# AK4493-Combi.net
KiCad netlist of a schematic drawn in EAGLE
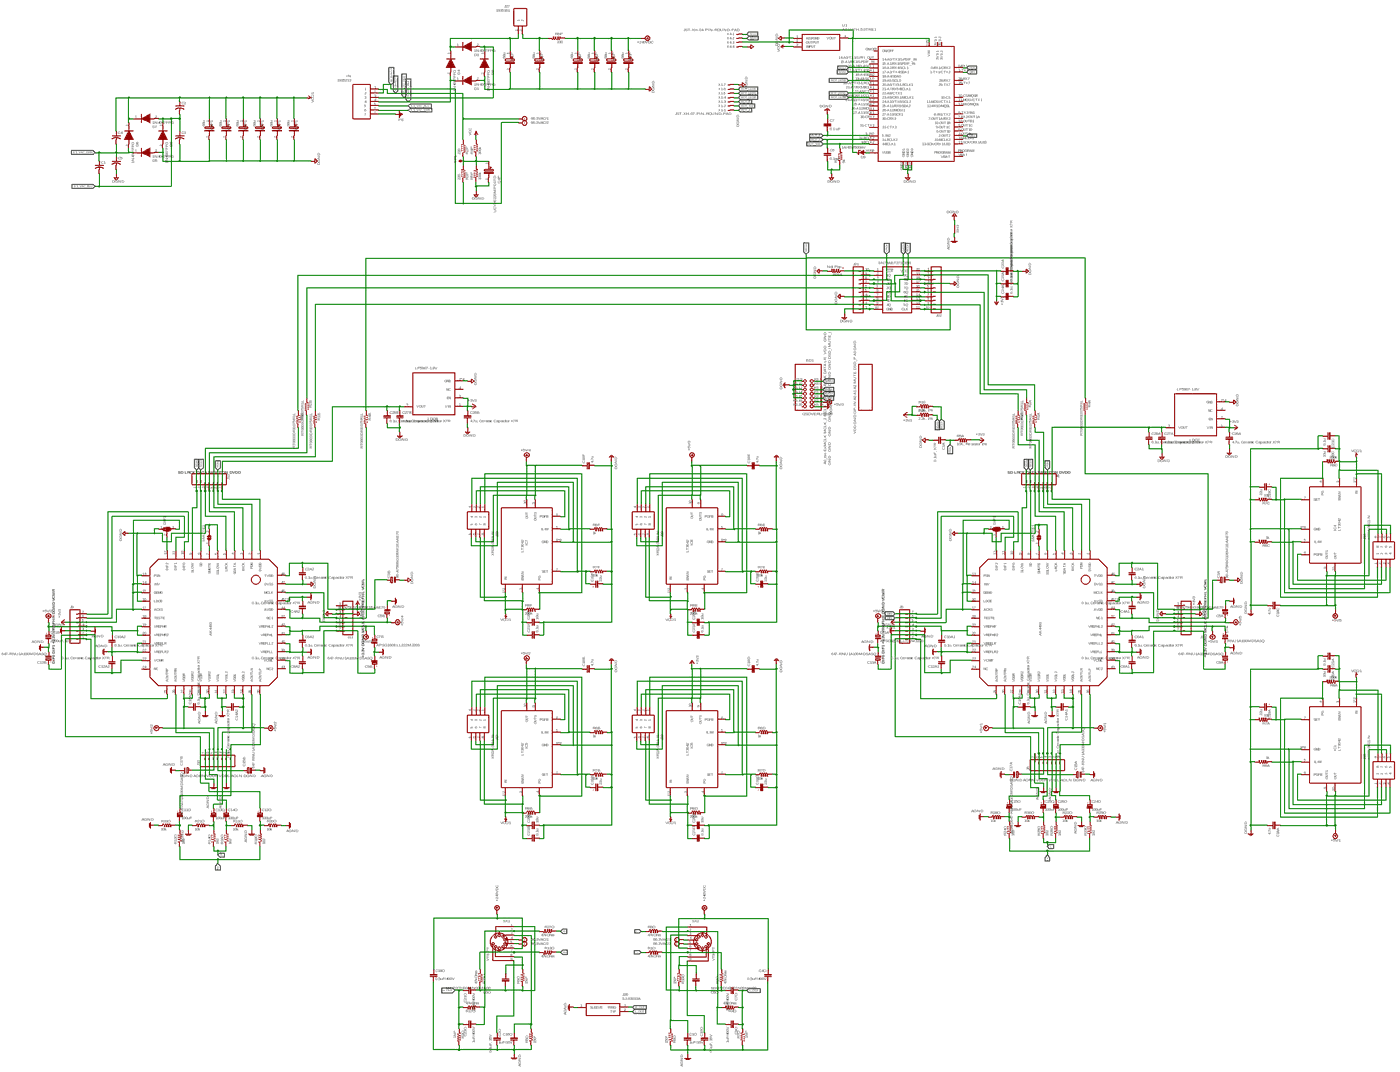
[diagram p0: schematic, sheet 1, overview]
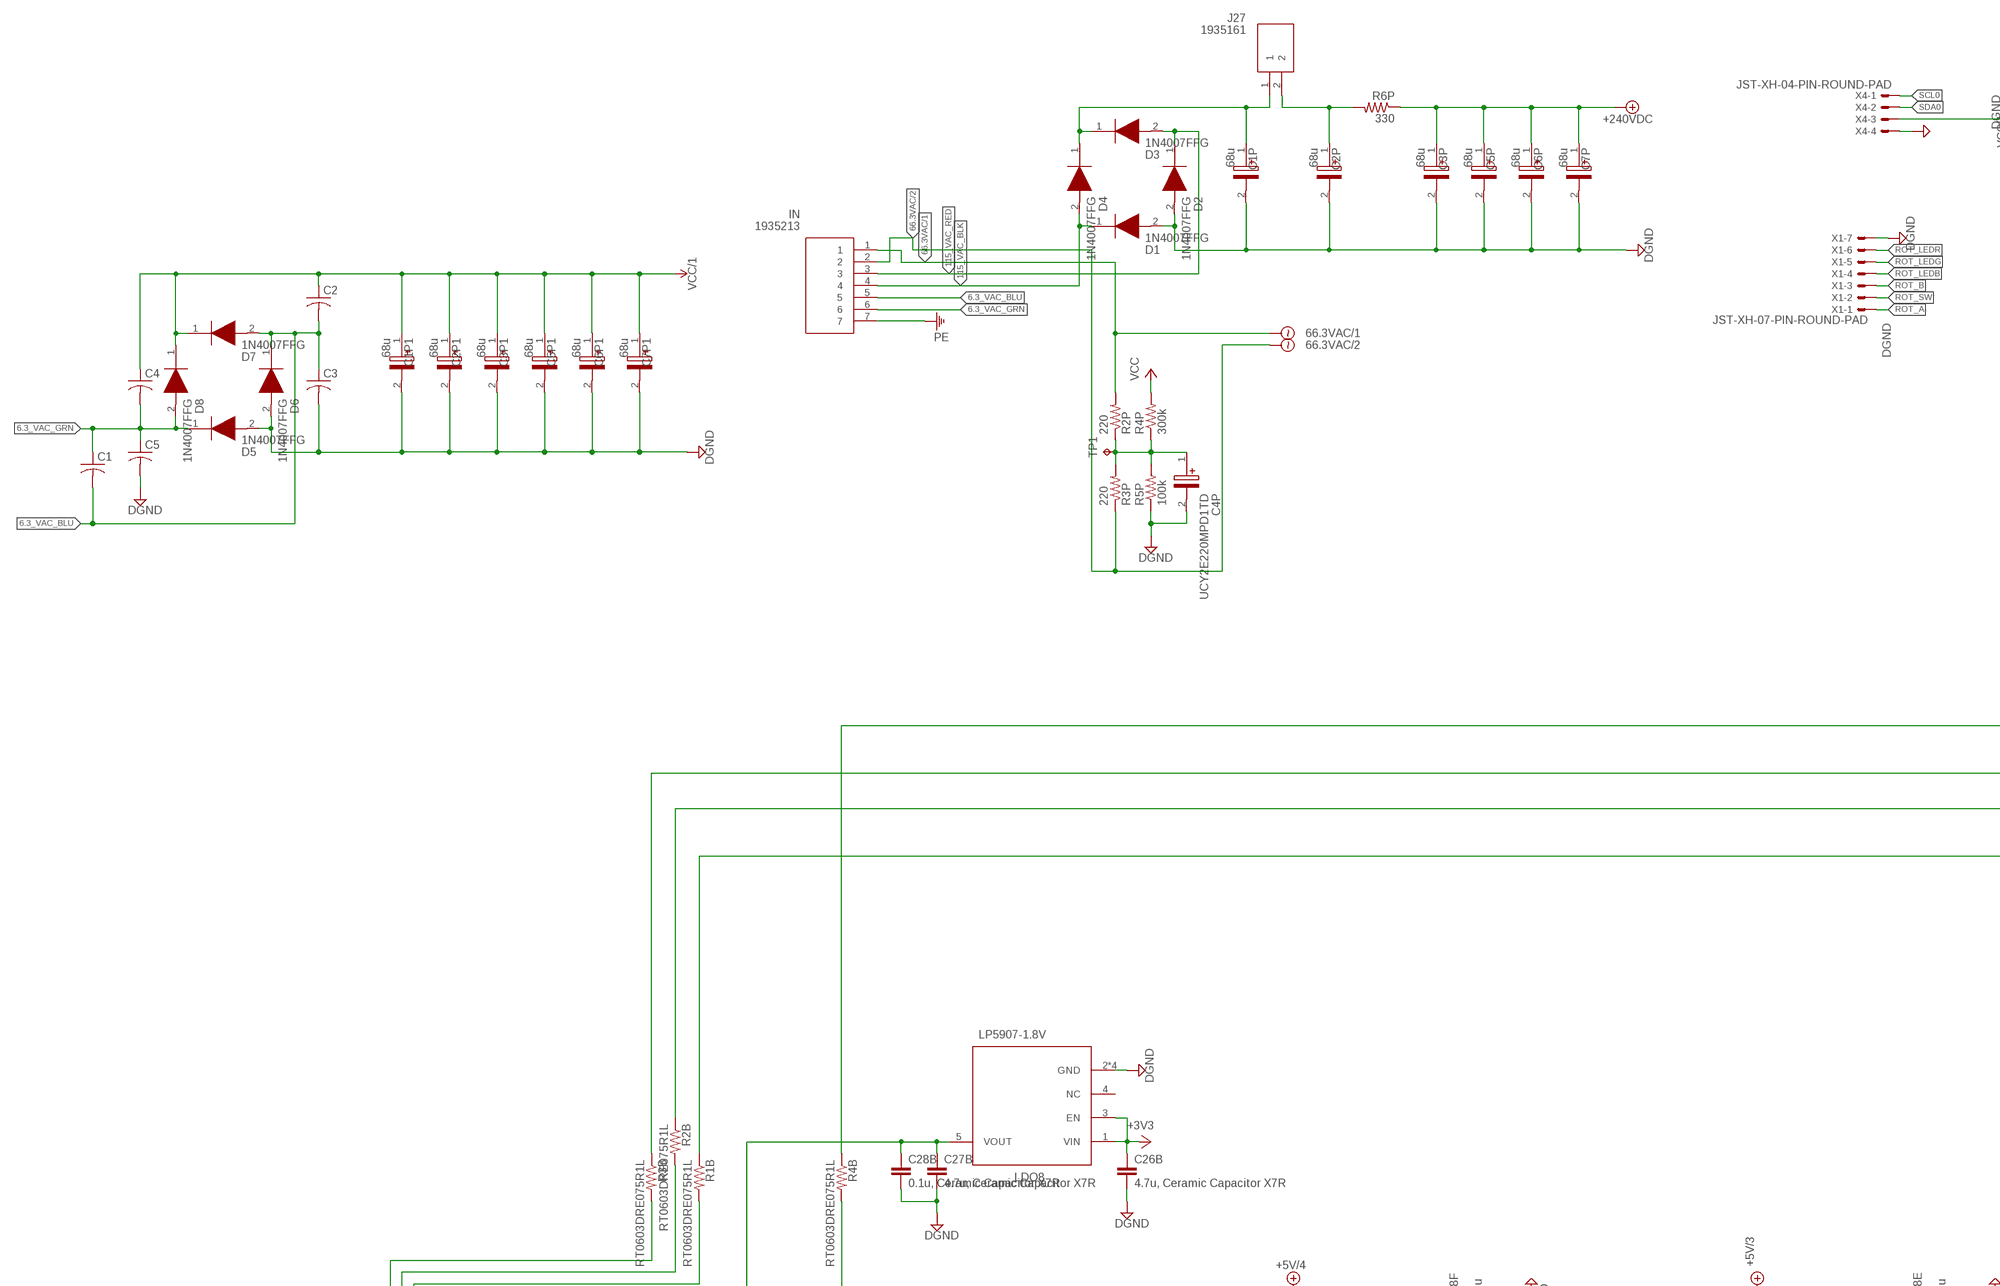
[diagram p1: schematic, sheet 1, part 1 of 4]
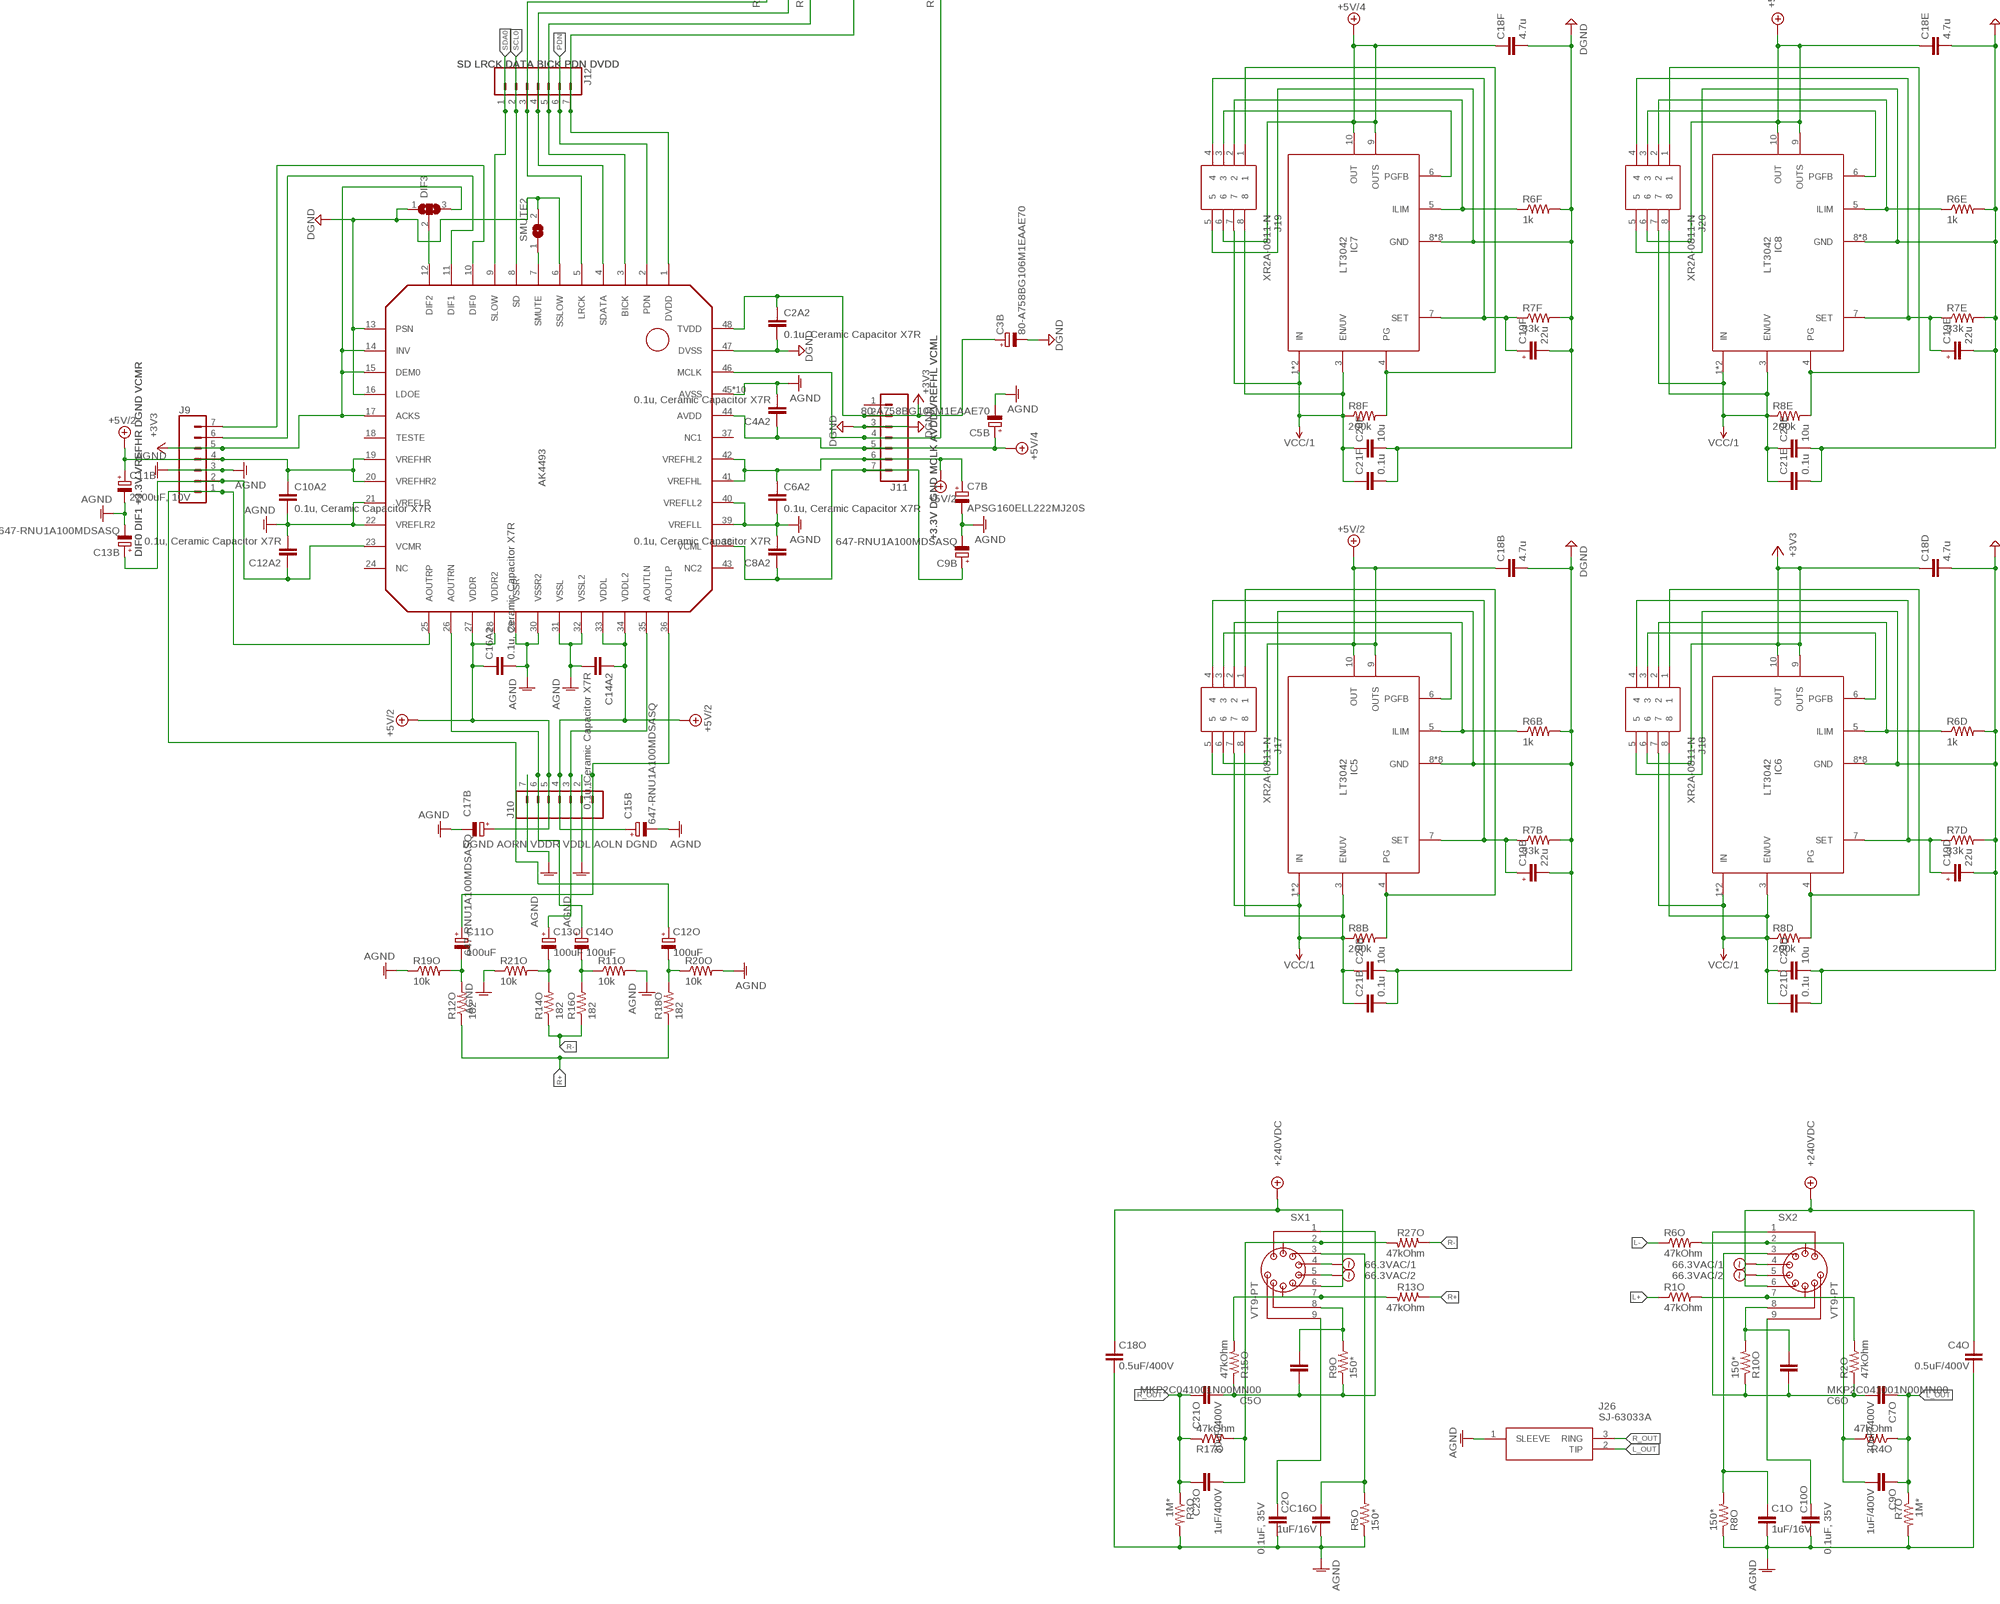
[diagram p2: schematic, sheet 1, part 2 of 4]
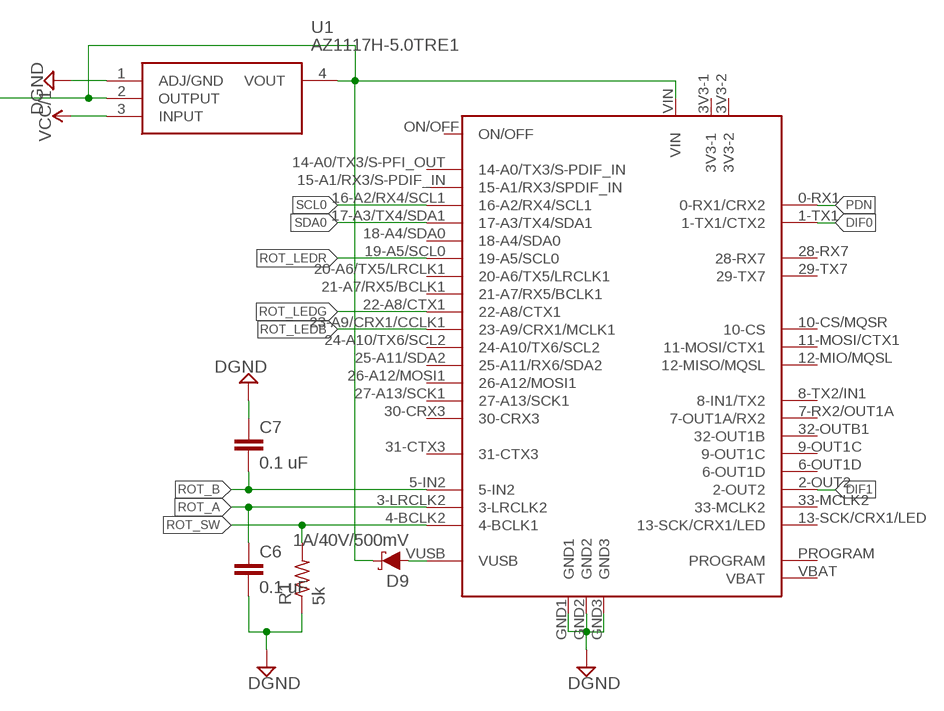
[diagram p3: schematic, sheet 1, part 3 of 4]
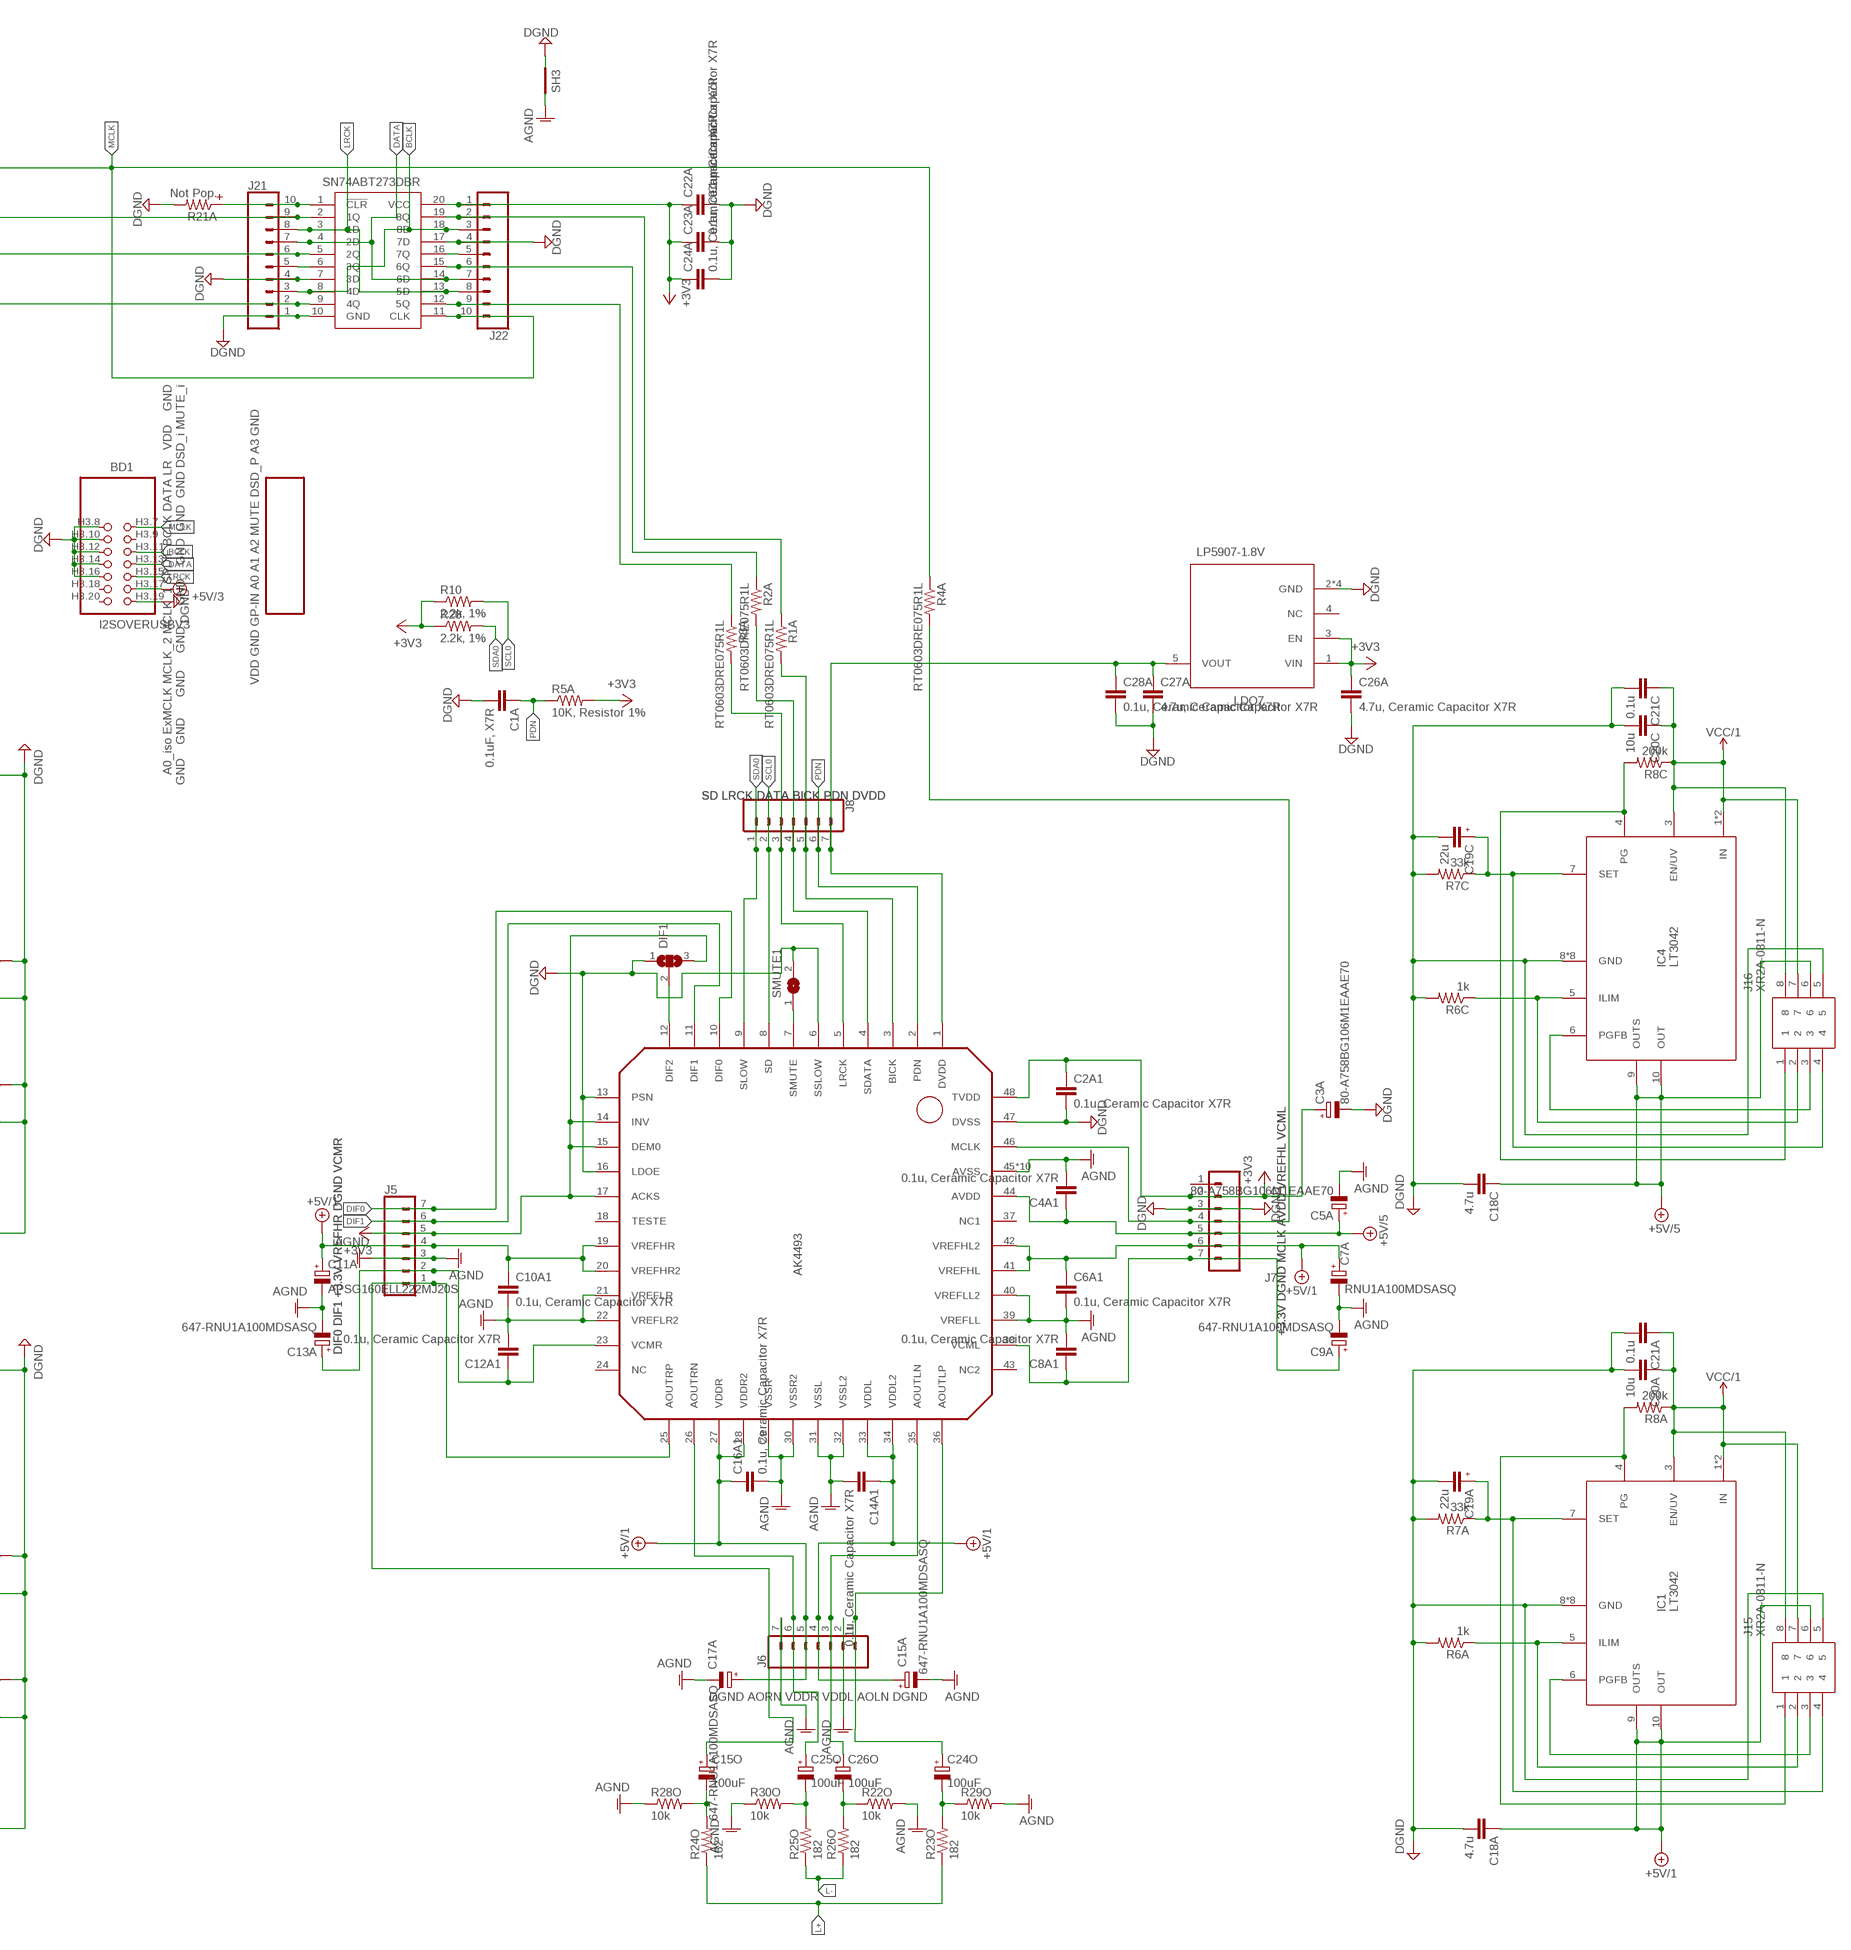
[diagram p4: schematic, sheet 1, part 4 of 4]

(export (version "E")
  (design (tool "Eeschema 10.0.6"))
  (components
    (comp (ref "BD1")
      (value "I2SOVERUSBV3")
      (footprint "eagle-import:I2SOVERUSBV3")
      (libsource (lib "eagle-import") (part "I2SOVERUSBV3"))
    )
    (comp (ref "C1")
      (value "C-US075-032X103")
      (footprint "eagle-import:C075-032X103")
      (libsource (lib "eagle-import") (part "C-US075-032X103"))
    )
    (comp (ref "C1A")
      (value "0.1uF, X7R")
      (footprint "eagle-import:CAPC2012X135N")
      (fields
        (field (name "MANUFACTURER_PART_NUMBER") "EMF212B7104KGHT")
        (field (name "MOUSER_PART_NUMBER") "963-EMF212B7104KGHT")
      )
      (libsource (lib "eagle-import") (part "EMF212B7104KGHT"))
    )
    (comp (ref "C1O")
      (value "1uF/16V")
      (footprint "eagle-import:MKP2C041001N00MN00")
      (fields
        (field (name "MANUFACTURER_PART_NUMBER") "MKP2C041001N00MN00")
        (field (name "MOUSER_PART_NUMBER") "505-MKP2C0411NMN")
      )
      (libsource (lib "eagle-import") (part "MKP2C041001N00MN00"))
    )
    (comp (ref "C1P")
      (value "68u")
      (footprint "eagle-import:CAPPRD750W80D1475H4700")
      (fields (field (name "MANUFACTURER_PART_NUMBER") "500HXW68MEFR14.5X45"))
      (libsource (lib "eagle-import") (part "500HXW68MEFR14.5X45"))
    )
    (comp (ref "C1P1")
      (value "68u")
      (footprint "eagle-import:CAPPRD750W80D1475H4700")
      (fields (field (name "MANUFACTURER_PART_NUMBER") "500HXW68MEFR14.5X45"))
      (libsource (lib "eagle-import") (part "500HXW68MEFR14.5X45"))
    )
    (comp (ref "C2")
      (value "C-US075-032X103")
      (footprint "eagle-import:C075-032X103")
      (libsource (lib "eagle-import") (part "C-US075-032X103"))
    )
    (comp (ref "C2A1")
      (value "0.1u, Ceramic Capacitor X7R")
      (footprint "eagle-import:CAPC1608X95N")
      (fields
        (field (name "MANUFACTURER_PART_NUMBER") "EMK107B7104KA-T")
        (field (name "MOUSER_PART_NUMBER") "963-EMK107B7104KA-T")
      )
      (libsource (lib "eagle-import") (part "EMK107B7104KA-T"))
    )
    (comp (ref "C2A2")
      (value "0.1u, Ceramic Capacitor X7R")
      (footprint "eagle-import:CAPC1608X95N")
      (fields
        (field (name "MANUFACTURER_PART_NUMBER") "EMK107B7104KA-T")
        (field (name "MOUSER_PART_NUMBER") "963-EMK107B7104KA-T")
      )
      (libsource (lib "eagle-import") (part "EMK107B7104KA-T"))
    )
    (comp (ref "C2O")
      (value "0.1uF, 35V")
      (footprint "eagle-import:MKS4B031002A00JC00")
      (fields
        (field (name "MANUFACTURER_PART_NUMBER") "MKS4B031002A00JC00")
        (field (name "MOUSER_PART_NUMBER") "505-MKS4B0312AJC")
      )
      (libsource (lib "eagle-import") (part "MKS4B031002A00JC00"))
    )
    (comp (ref "C2P")
      (value "68u")
      (footprint "eagle-import:CAPPRD750W80D1475H4700")
      (fields (field (name "MANUFACTURER_PART_NUMBER") "500HXW68MEFR14.5X45"))
      (libsource (lib "eagle-import") (part "500HXW68MEFR14.5X45"))
    )
    (comp (ref "C2P1")
      (value "68u")
      (footprint "eagle-import:CAPPRD750W80D1475H4700")
      (fields (field (name "MANUFACTURER_PART_NUMBER") "500HXW68MEFR14.5X45"))
      (libsource (lib "eagle-import") (part "500HXW68MEFR14.5X45"))
    )
    (comp (ref "C3")
      (value "C-US075-032X103")
      (footprint "eagle-import:C075-032X103")
      (libsource (lib "eagle-import") (part "C-US075-032X103"))
    )
    (comp (ref "C3A")
      (value "80-A758BG106M1EAAE70")
      (footprint "eagle-import:CAPPRD150W45D450H600")
      (fields
        (field (name "MANUFACTURER_PART_NUMBER") "RNU1A100MDSASQ")
        (field (name "MOUSER_PART_NUMBER") "647-RNU1A100MDSASQ")
      )
      (libsource (lib "eagle-import") (part "RNU1A100MDSASQ"))
    )
    (comp (ref "C3B")
      (value "80-A758BG106M1EAAE70")
      (footprint "eagle-import:CAPPRD200W55D500H800")
      (fields (field (name "MANUFACTURER_PART_NUMBER") "A758BG106M1EAAE070"))
      (libsource (lib "eagle-import") (part "A758BG106M1EAAE070"))
    )
    (comp (ref "C3P")
      (value "68u")
      (footprint "eagle-import:CAPPRD750W80D1475H4700")
      (fields (field (name "MANUFACTURER_PART_NUMBER") "500HXW68MEFR14.5X45"))
      (libsource (lib "eagle-import") (part "500HXW68MEFR14.5X45"))
    )
    (comp (ref "C3P1")
      (value "68u")
      (footprint "eagle-import:CAPPRD750W80D1475H4700")
      (fields (field (name "MANUFACTURER_PART_NUMBER") "500HXW68MEFR14.5X45"))
      (libsource (lib "eagle-import") (part "500HXW68MEFR14.5X45"))
    )
    (comp (ref "C4")
      (value "C-US075-032X103")
      (footprint "eagle-import:C075-032X103")
      (libsource (lib "eagle-import") (part "C-US075-032X103"))
    )
    (comp (ref "C4A1")
      (value "0.1u, Ceramic Capacitor X7R")
      (footprint "eagle-import:CAPC1608X95N")
      (fields
        (field (name "MANUFACTURER_PART_NUMBER") "EMK107B7104KA-T")
        (field (name "MOUSER_PART_NUMBER") "963-EMK107B7104KA-T")
      )
      (libsource (lib "eagle-import") (part "EMK107B7104KA-T"))
    )
    (comp (ref "C4A2")
      (value "0.1u, Ceramic Capacitor X7R")
      (footprint "eagle-import:CAPC1608X95N")
      (fields
        (field (name "MANUFACTURER_PART_NUMBER") "EMK107B7104KA-T")
        (field (name "MOUSER_PART_NUMBER") "963-EMK107B7104KA-T")
      )
      (libsource (lib "eagle-import") (part "EMK107B7104KA-T"))
    )
    (comp (ref "C4O")
      (value "0.5uF/400V")
      (footprint "eagle-import:MKP4G034705D00KSSD")
      (fields
        (field (name "MANUFACTURER_PART_NUMBER") "MKP4G034705D00KSSD")
        (field (name "MOUSER_PART_NUMBER") "505-MKP4G034705DKSSD")
      )
      (libsource (lib "eagle-import") (part "MKP4G034705D00KSSD"))
    )
    (comp (ref "C4P")
      (value "UCY2E220MPD1TD")
      (footprint "eagle-import:CAPPRD500W60D1025H1750")
      (fields (field (name "MOUSER_PART_NUMBER") "647-UCY2E220MPD1TD"))
      (libsource (lib "eagle-import") (part "UCY2E220MPD1TD"))
    )
    (comp (ref "C5")
      (value "C-US075-032X103")
      (footprint "eagle-import:C075-032X103")
      (libsource (lib "eagle-import") (part "C-US075-032X103"))
    )
    (comp (ref "C5A")
      (value "80-A758BG106M1EAAE70")
      (footprint "eagle-import:CAPPRD200W55D500H800")
      (fields (field (name "MANUFACTURER_PART_NUMBER") "A758BG106M1EAAE070"))
      (libsource (lib "eagle-import") (part "A758BG106M1EAAE070"))
    )
    (comp (ref "C5B")
      (value "80-A758BG106M1EAAE70")
      (footprint "eagle-import:CAPPRD200W55D500H800")
      (fields (field (name "MANUFACTURER_PART_NUMBER") "A758BG106M1EAAE070"))
      (libsource (lib "eagle-import") (part "A758BG106M1EAAE070"))
    )
    (comp (ref "C5O")
      (value "MKP2C041001N00MN00")
      (footprint "eagle-import:MKP2C041001N00MN00")
      (fields (field (name "MOUSER_PART_NUMBER") "505-MKP2C0411NMN"))
      (libsource (lib "eagle-import") (part "MKP2C041001N00MN00"))
    )
    (comp (ref "C5P")
      (value "68u")
      (footprint "eagle-import:CAPPRD750W80D1475H4700")
      (fields (field (name "MANUFACTURER_PART_NUMBER") "500HXW68MEFR14.5X45"))
      (libsource (lib "eagle-import") (part "500HXW68MEFR14.5X45"))
    )
    (comp (ref "C5P1")
      (value "68u")
      (footprint "eagle-import:CAPPRD750W80D1475H4700")
      (fields (field (name "MANUFACTURER_PART_NUMBER") "500HXW68MEFR14.5X45"))
      (libsource (lib "eagle-import") (part "500HXW68MEFR14.5X45"))
    )
    (comp (ref "C6")
      (value "0.1 uF")
      (footprint "eagle-import:C0603")
      (libsource (lib "eagle-import") (part "C0603"))
    )
    (comp (ref "C6A1")
      (value "0.1u, Ceramic Capacitor X7R")
      (footprint "eagle-import:CAPC1608X95N")
      (fields
        (field (name "MANUFACTURER_PART_NUMBER") "EMK107B7104KA-T")
        (field (name "MOUSER_PART_NUMBER") "963-EMK107B7104KA-T")
      )
      (libsource (lib "eagle-import") (part "EMK107B7104KA-T"))
    )
    (comp (ref "C6A2")
      (value "0.1u, Ceramic Capacitor X7R")
      (footprint "eagle-import:CAPC1608X95N")
      (fields
        (field (name "MANUFACTURER_PART_NUMBER") "EMK107B7104KA-T")
        (field (name "MOUSER_PART_NUMBER") "963-EMK107B7104KA-T")
      )
      (libsource (lib "eagle-import") (part "EMK107B7104KA-T"))
    )
    (comp (ref "C6O")
      (value "MKP2C041001N00MN00")
      (footprint "eagle-import:MKP2C041001N00MN00")
      (fields (field (name "MOUSER_PART_NUMBER") "505-MKP2C0411NMN"))
      (libsource (lib "eagle-import") (part "MKP2C041001N00MN00"))
    )
    (comp (ref "C6P")
      (value "68u")
      (footprint "eagle-import:CAPPRD750W80D1475H4700")
      (fields (field (name "MANUFACTURER_PART_NUMBER") "500HXW68MEFR14.5X45"))
      (libsource (lib "eagle-import") (part "500HXW68MEFR14.5X45"))
    )
    (comp (ref "C6P1")
      (value "68u")
      (footprint "eagle-import:CAPPRD750W80D1475H4700")
      (fields (field (name "MANUFACTURER_PART_NUMBER") "500HXW68MEFR14.5X45"))
      (libsource (lib "eagle-import") (part "500HXW68MEFR14.5X45"))
    )
    (comp (ref "C7")
      (value "0.1 uF")
      (footprint "eagle-import:C0603")
      (libsource (lib "eagle-import") (part "C0603"))
    )
    (comp (ref "C7A")
      (value "RNU1A100MDSASQ")
      (footprint "eagle-import:CAPPRD150W45D450H600")
      (fields (field (name "MOUSER_PART_NUMBER") "647-RNU1A100MDSASQ"))
      (libsource (lib "eagle-import") (part "RNU1A100MDSASQ"))
    )
    (comp (ref "C7B")
      (value "APSG160ELL222MJ20S")
      (footprint "eagle-import:CAPPRD500W60D1025H2150")
      (fields (field (name "MOUSER_PART_NUMBER") "661-APSG160E222MJ20S"))
      (libsource (lib "eagle-import") (part "APSG160ELL222MJ20S"))
    )
    (comp (ref "C7O")
      (value "30uF/400V")
      (footprint "eagle-import:DCP4G053006ID2KSSD")
      (fields
        (field (name "MANUFACTURER_PART_NUMBER") "DCP4G053006ID2KSSD")
        (field (name "MOUSER_PART_NUMBER") "505-DCP4G0536ID2KSSD")
      )
      (libsource (lib "eagle-import") (part "DCP4G053006ID2KSSD"))
    )
    (comp (ref "C7P")
      (value "68u")
      (footprint "eagle-import:CAPPRD750W80D1475H4700")
      (fields (field (name "MANUFACTURER_PART_NUMBER") "500HXW68MEFR14.5X45"))
      (libsource (lib "eagle-import") (part "500HXW68MEFR14.5X45"))
    )
    (comp (ref "C7P1")
      (value "68u")
      (footprint "eagle-import:CAPPRD750W80D1475H4700")
      (fields (field (name "MANUFACTURER_PART_NUMBER") "500HXW68MEFR14.5X45"))
      (libsource (lib "eagle-import") (part "500HXW68MEFR14.5X45"))
    )
    (comp (ref "C8A1")
      (value "0.1u, Ceramic Capacitor X7R")
      (footprint "eagle-import:CAPC1608X95N")
      (fields
        (field (name "MANUFACTURER_PART_NUMBER") "EMK107B7104KA-T")
        (field (name "MOUSER_PART_NUMBER") "963-EMK107B7104KA-T")
      )
      (libsource (lib "eagle-import") (part "EMK107B7104KA-T"))
    )
    (comp (ref "C8A2")
      (value "0.1u, Ceramic Capacitor X7R")
      (footprint "eagle-import:CAPC1608X95N")
      (fields
        (field (name "MANUFACTURER_PART_NUMBER") "EMK107B7104KA-T")
        (field (name "MOUSER_PART_NUMBER") "963-EMK107B7104KA-T")
      )
      (libsource (lib "eagle-import") (part "EMK107B7104KA-T"))
    )
    (comp (ref "C9A")
      (value "647-RNU1A100MDSASQ")
      (footprint "eagle-import:CAPPRD150W45D450H600")
      (fields (field (name "MANUFACTURER_PART_NUMBER") "RNU1A100MDSASQ"))
      (libsource (lib "eagle-import") (part "RNU1A100MDSASQ"))
    )
    (comp (ref "C9B")
      (value "647-RNU1A100MDSASQ")
      (footprint "eagle-import:CAPPRD150W45D450H600")
      (fields (field (name "MANUFACTURER_PART_NUMBER") "RNU1A100MDSASQ"))
      (libsource (lib "eagle-import") (part "RNU1A100MDSASQ"))
    )
    (comp (ref "C9O")
      (value "1uF/400V")
      (footprint "eagle-import:MKP4G041005I00JSSD")
      (fields
        (field (name "MANUFACTURER_PART_NUMBER") "MKP4G041005I00JSSD")
        (field (name "MOUSER_PART_NUMBER") "505-MKP4G041005I00JS")
      )
      (libsource (lib "eagle-import") (part "MKP4G041005I00JSSD"))
    )
    (comp (ref "C10A1")
      (value "0.1u, Ceramic Capacitor X7R")
      (footprint "eagle-import:CAPC1608X95N")
      (fields
        (field (name "MANUFACTURER_PART_NUMBER") "EMK107B7104KA-T")
        (field (name "MOUSER_PART_NUMBER") "963-EMK107B7104KA-T")
      )
      (libsource (lib "eagle-import") (part "EMK107B7104KA-T"))
    )
    (comp (ref "C10A2")
      (value "0.1u, Ceramic Capacitor X7R")
      (footprint "eagle-import:CAPC1608X95N")
      (fields
        (field (name "MANUFACTURER_PART_NUMBER") "EMK107B7104KA-T")
        (field (name "MOUSER_PART_NUMBER") "963-EMK107B7104KA-T")
      )
      (libsource (lib "eagle-import") (part "EMK107B7104KA-T"))
    )
    (comp (ref "C10O")
      (value "0.1uF, 35V")
      (footprint "eagle-import:MKS4B031002A00JC00")
      (fields
        (field (name "MANUFACTURER_PART_NUMBER") "MKS4B031002A00JC00")
        (field (name "MOUSER_PART_NUMBER") "505-MKS4B0312AJC")
      )
      (libsource (lib "eagle-import") (part "MKS4B031002A00JC00"))
    )
    (comp (ref "C11A")
      (value "APSG160ELL222MJ20S")
      (footprint "eagle-import:CAPPRD500W60D1025H2150")
      (fields (field (name "MOUSER_PART_NUMBER") "661-APSG160E222MJ20S"))
      (libsource (lib "eagle-import") (part "APSG160ELL222MJ20S"))
    )
    (comp (ref "C11B")
      (value "2200uF, 10V")
      (footprint "eagle-import:CAPPRD500W60D1025H2150")
      (fields
        (field (name "MANUFACTURER_PART_NUMBER") "APSG160ELL222MJ20S")
        (field (name "MOUSER_PART_NUMBER") "661-APSG160E222MJ20S")
      )
      (libsource (lib "eagle-import") (part "APSG160ELL222MJ20S"))
    )
    (comp (ref "C11O")
      (value "100uF")
      (footprint "eagle-import:CAPPRD350W60D825H1300")
      (fields
        (field (name "ARROW_PART_NUMBER") "UFW1H101MPD1TD")
        (field (name "MOUSER_PART_NUMBER") "647-UFW1H101MPD1TD")
      )
      (libsource (lib "eagle-import") (part "UFW1H101MPD1TD"))
    )
    (comp (ref "C12A1")
      (value "0.1u, Ceramic Capacitor X7R")
      (footprint "eagle-import:CAPC1608X95N")
      (fields
        (field (name "MANUFACTURER_PART_NUMBER") "EMK107B7104KA-T")
        (field (name "MOUSER_PART_NUMBER") "963-EMK107B7104KA-T")
      )
      (libsource (lib "eagle-import") (part "EMK107B7104KA-T"))
    )
    (comp (ref "C12A2")
      (value "0.1u, Ceramic Capacitor X7R")
      (footprint "eagle-import:CAPC1608X95N")
      (fields
        (field (name "MANUFACTURER_PART_NUMBER") "EMK107B7104KA-T")
        (field (name "MOUSER_PART_NUMBER") "963-EMK107B7104KA-T")
      )
      (libsource (lib "eagle-import") (part "EMK107B7104KA-T"))
    )
    (comp (ref "C12O")
      (value "100uF")
      (footprint "eagle-import:CAPPRD350W60D825H1300")
      (fields
        (field (name "ARROW_PART_NUMBER") "UFW1H101MPD1TD")
        (field (name "MOUSER_PART_NUMBER") "647-UFW1H101MPD1TD")
      )
      (libsource (lib "eagle-import") (part "UFW1H101MPD1TD"))
    )
    (comp (ref "C13A")
      (value "647-RNU1A100MDSASQ")
      (footprint "eagle-import:CAPPRD150W45D450H600")
      (fields (field (name "MANUFACTURER_PART_NUMBER") "RNU1A100MDSASQ"))
      (libsource (lib "eagle-import") (part "RNU1A100MDSASQ"))
    )
    (comp (ref "C13B")
      (value "647-RNU1A100MDSASQ")
      (footprint "eagle-import:CAPPRD150W45D450H600")
      (fields (field (name "MANUFACTURER_PART_NUMBER") "RNU1A100MDSASQ"))
      (libsource (lib "eagle-import") (part "RNU1A100MDSASQ"))
    )
    (comp (ref "C13O")
      (value "100uF")
      (footprint "eagle-import:CAPPRD350W60D825H1300")
      (fields
        (field (name "ARROW_PART_NUMBER") "UFW1H101MPD1TD")
        (field (name "MOUSER_PART_NUMBER") "647-UFW1H101MPD1TD")
      )
      (libsource (lib "eagle-import") (part "UFW1H101MPD1TD"))
    )
    (comp (ref "C14A1")
      (value "0.1u, Ceramic Capacitor X7R")
      (footprint "eagle-import:CAPC1608X95N")
      (fields
        (field (name "MANUFACTURER_PART_NUMBER") "EMK107B7104KA-T")
        (field (name "MOUSER_PART_NUMBER") "963-EMK107B7104KA-T")
      )
      (libsource (lib "eagle-import") (part "EMK107B7104KA-T"))
    )
    (comp (ref "C14A2")
      (value "0.1u, Ceramic Capacitor X7R")
      (footprint "eagle-import:CAPC1608X95N")
      (fields
        (field (name "MANUFACTURER_PART_NUMBER") "EMK107B7104KA-T")
        (field (name "MOUSER_PART_NUMBER") "963-EMK107B7104KA-T")
      )
      (libsource (lib "eagle-import") (part "EMK107B7104KA-T"))
    )
    (comp (ref "C14O")
      (value "100uF")
      (footprint "eagle-import:CAPPRD350W60D825H1300")
      (fields
        (field (name "ARROW_PART_NUMBER") "UFW1H101MPD1TD")
        (field (name "MOUSER_PART_NUMBER") "647-UFW1H101MPD1TD")
      )
      (libsource (lib "eagle-import") (part "UFW1H101MPD1TD"))
    )
    (comp (ref "C15A")
      (value "647-RNU1A100MDSASQ")
      (footprint "eagle-import:CAPPRD150W45D450H600")
      (fields (field (name "MANUFACTURER_PART_NUMBER") "RNU1A100MDSASQ"))
      (libsource (lib "eagle-import") (part "RNU1A100MDSASQ"))
    )
    (comp (ref "C15B")
      (value "647-RNU1A100MDSASQ")
      (footprint "eagle-import:CAPPRD150W45D450H600")
      (fields (field (name "MANUFACTURER_PART_NUMBER") "RNU1A100MDSASQ"))
      (libsource (lib "eagle-import") (part "RNU1A100MDSASQ"))
    )
    (comp (ref "C15O")
      (value "100uF")
      (footprint "eagle-import:CAPPRD350W60D825H1300")
      (fields
        (field (name "ARROW_PART_NUMBER") "UFW1H101MPD1TD")
        (field (name "MOUSER_PART_NUMBER") "647-UFW1H101MPD1TD")
      )
      (libsource (lib "eagle-import") (part "UFW1H101MPD1TD"))
    )
    (comp (ref "C16A1")
      (value "0.1u, Ceramic Capacitor X7R")
      (footprint "eagle-import:CAPC1608X95N")
      (fields
        (field (name "MANUFACTURER_PART_NUMBER") "EMK107B7104KA-T")
        (field (name "MOUSER_PART_NUMBER") "963-EMK107B7104KA-T")
      )
      (libsource (lib "eagle-import") (part "EMK107B7104KA-T"))
    )
    (comp (ref "C16A2")
      (value "0.1u, Ceramic Capacitor X7R")
      (footprint "eagle-import:CAPC1608X95N")
      (fields
        (field (name "MANUFACTURER_PART_NUMBER") "EMK107B7104KA-T")
        (field (name "MOUSER_PART_NUMBER") "963-EMK107B7104KA-T")
      )
      (libsource (lib "eagle-import") (part "EMK107B7104KA-T"))
    )
    (comp (ref "C16O")
      (value "1uF/16V")
      (footprint "eagle-import:MKP2C041001N00MN00")
      (fields
        (field (name "MANUFACTURER_PART_NUMBER") "MKP2C041001N00MN00")
        (field (name "MOUSER_PART_NUMBER") "505-MKP2C0411NMN")
      )
      (libsource (lib "eagle-import") (part "MKP2C041001N00MN00"))
    )
    (comp (ref "C17A")
      (value "647-RNU1A100MDSASQ")
      (footprint "eagle-import:CAPPRD150W45D450H600")
      (fields (field (name "MANUFACTURER_PART_NUMBER") "RNU1A100MDSASQ"))
      (libsource (lib "eagle-import") (part "RNU1A100MDSASQ"))
    )
    (comp (ref "C17B")
      (value "647-RNU1A100MDSASQ")
      (footprint "eagle-import:CAPPRD150W45D450H600")
      (fields (field (name "MANUFACTURER_PART_NUMBER") "RNU1A100MDSASQ"))
      (libsource (lib "eagle-import") (part "RNU1A100MDSASQ"))
    )
    (comp (ref "C18A")
      (value "4.7u")
      (footprint "eagle-import:CAPC2013X140N")
      (fields
        (field (name "MANUFACTURER_PART_NUMBER") "EMK212ABJ475KG-T")
        (field (name "MOUSER_PART_NUMBER") "963-EMK212ABJ475KG-T")
      )
      (libsource (lib "eagle-import") (part "EMK212ABJ475KG-T"))
    )
    (comp (ref "C18B")
      (value "4.7u")
      (footprint "eagle-import:CAPC2013X140N")
      (fields
        (field (name "MANUFACTURER_PART_NUMBER") "EMK212ABJ475KG-T")
        (field (name "MOUSER_PART_NUMBER") "963-EMK212ABJ475KG-T")
      )
      (libsource (lib "eagle-import") (part "EMK212ABJ475KG-T"))
    )
    (comp (ref "C18C")
      (value "4.7u")
      (footprint "eagle-import:CAPC2013X140N")
      (fields
        (field (name "MANUFACTURER_PART_NUMBER") "EMK212ABJ475KG-T")
        (field (name "MOUSER_PART_NUMBER") "963-EMK212ABJ475KG-T")
      )
      (libsource (lib "eagle-import") (part "EMK212ABJ475KG-T"))
    )
    (comp (ref "C18D")
      (value "4.7u")
      (footprint "eagle-import:CAPC2013X140N")
      (fields
        (field (name "MANUFACTURER_PART_NUMBER") "EMK212ABJ475KG-T")
        (field (name "MOUSER_PART_NUMBER") "963-EMK212ABJ475KG-T")
      )
      (libsource (lib "eagle-import") (part "EMK212ABJ475KG-T"))
    )
    (comp (ref "C18E")
      (value "4.7u")
      (footprint "eagle-import:CAPC2013X140N")
      (fields
        (field (name "MANUFACTURER_PART_NUMBER") "EMK212ABJ475KG-T")
        (field (name "MOUSER_PART_NUMBER") "963-EMK212ABJ475KG-T")
      )
      (libsource (lib "eagle-import") (part "EMK212ABJ475KG-T"))
    )
    (comp (ref "C18F")
      (value "4.7u")
      (footprint "eagle-import:CAPC2013X140N")
      (fields
        (field (name "MANUFACTURER_PART_NUMBER") "EMK212ABJ475KG-T")
        (field (name "MOUSER_PART_NUMBER") "963-EMK212ABJ475KG-T")
      )
      (libsource (lib "eagle-import") (part "EMK212ABJ475KG-T"))
    )
    (comp (ref "C18O")
      (value "0.5uF/400V")
      (footprint "eagle-import:MKP4G034705D00KSSD")
      (fields
        (field (name "MANUFACTURER_PART_NUMBER") "MKP4G034705D00KSSD")
        (field (name "MOUSER_PART_NUMBER") "505-MKP4G034705DKSSD")
      )
      (libsource (lib "eagle-import") (part "MKP4G034705D00KSSD"))
    )
    (comp (ref "C19A")
      (value "22u")
      (footprint "eagle-import:C1206")
      (fields
        (field (name "MANUFACTURER_PART_NUMBER") "EMK316BB7226ML-T")
        (field (name "MOUSER_PART_NUMBER") "963-EMK316BB7226ML-T")
      )
      (libsource (lib "eagle-import") (part "EMK316BB7226ML-T"))
    )
    (comp (ref "C19B")
      (value "22u")
      (footprint "eagle-import:C1206")
      (fields
        (field (name "MANUFACTURER_PART_NUMBER") "EMK316BB7226ML-T")
        (field (name "MOUSER_PART_NUMBER") "963-EMK316BB7226ML-T")
      )
      (libsource (lib "eagle-import") (part "EMK316BB7226ML-T"))
    )
    (comp (ref "C19C")
      (value "22u")
      (footprint "eagle-import:C1206")
      (fields
        (field (name "MANUFACTURER_PART_NUMBER") "EMK316BB7226ML-T")
        (field (name "MOUSER_PART_NUMBER") "963-EMK316BB7226ML-T")
      )
      (libsource (lib "eagle-import") (part "EMK316BB7226ML-T"))
    )
    (comp (ref "C19D")
      (value "22u")
      (footprint "eagle-import:C1206")
      (fields
        (field (name "MANUFACTURER_PART_NUMBER") "EMK316BB7226ML-T")
        (field (name "MOUSER_PART_NUMBER") "963-EMK316BB7226ML-T")
      )
      (libsource (lib "eagle-import") (part "EMK316BB7226ML-T"))
    )
    (comp (ref "C19E")
      (value "22u")
      (footprint "eagle-import:C1206")
      (fields
        (field (name "MANUFACTURER_PART_NUMBER") "EMK316BB7226ML-T")
        (field (name "MOUSER_PART_NUMBER") "963-EMK316BB7226ML-T")
      )
      (libsource (lib "eagle-import") (part "EMK316BB7226ML-T"))
    )
    (comp (ref "C19F")
      (value "22u")
      (footprint "eagle-import:C1206")
      (fields
        (field (name "MANUFACTURER_PART_NUMBER") "EMK316BB7226ML-T")
        (field (name "MOUSER_PART_NUMBER") "963-EMK316BB7226ML-T")
      )
      (libsource (lib "eagle-import") (part "EMK316BB7226ML-T"))
    )
    (comp (ref "C20A")
      (value "10u")
      (footprint "eagle-import:CAPC2012X135N")
      (fields
        (field (name "MANUFACTURER_PART_NUMBER") "EMK212BB7106KG-T")
        (field (name "MOUSER_PART_NUMBER") "963-EMK212BB7106KG-T")
      )
      (libsource (lib "eagle-import") (part "EMK212BB7106KG-T"))
    )
    (comp (ref "C20B")
      (value "10u")
      (footprint "eagle-import:CAPC2012X135N")
      (fields
        (field (name "MANUFACTURER_PART_NUMBER") "EMK212BB7106KG-T")
        (field (name "MOUSER_PART_NUMBER") "963-EMK212BB7106KG-T")
      )
      (libsource (lib "eagle-import") (part "EMK212BB7106KG-T"))
    )
    (comp (ref "C20C")
      (value "10u")
      (footprint "eagle-import:CAPC2012X135N")
      (fields
        (field (name "MANUFACTURER_PART_NUMBER") "EMK212BB7106KG-T")
        (field (name "MOUSER_PART_NUMBER") "963-EMK212BB7106KG-T")
      )
      (libsource (lib "eagle-import") (part "EMK212BB7106KG-T"))
    )
    (comp (ref "C20D")
      (value "10u")
      (footprint "eagle-import:CAPC2012X135N")
      (fields
        (field (name "MANUFACTURER_PART_NUMBER") "EMK212BB7106KG-T")
        (field (name "MOUSER_PART_NUMBER") "963-EMK212BB7106KG-T")
      )
      (libsource (lib "eagle-import") (part "EMK212BB7106KG-T"))
    )
    (comp (ref "C20E")
      (value "10u")
      (footprint "eagle-import:CAPC2012X135N")
      (fields
        (field (name "MANUFACTURER_PART_NUMBER") "EMK212BB7106KG-T")
        (field (name "MOUSER_PART_NUMBER") "963-EMK212BB7106KG-T")
      )
      (libsource (lib "eagle-import") (part "EMK212BB7106KG-T"))
    )
    (comp (ref "C20F")
      (value "10u")
      (footprint "eagle-import:CAPC2012X135N")
      (fields
        (field (name "MANUFACTURER_PART_NUMBER") "EMK212BB7106KG-T")
        (field (name "MOUSER_PART_NUMBER") "963-EMK212BB7106KG-T")
      )
      (libsource (lib "eagle-import") (part "EMK212BB7106KG-T"))
    )
    (comp (ref "C21A")
      (value "0.1u")
      (footprint "eagle-import:CAPC2012X135N")
      (fields
        (field (name "MANUFACTURER_PART_NUMBER") "EMF212B7104KGHT")
        (field (name "MOUSER_PART_NUMBER") "963-EMF212B7104KGHT")
      )
      (libsource (lib "eagle-import") (part "EMF212B7104KGHT"))
    )
    (comp (ref "C21B")
      (value "0.1u")
      (footprint "eagle-import:CAPC2012X135N")
      (fields
        (field (name "MANUFACTURER_PART_NUMBER") "EMF212B7104KGHT")
        (field (name "MOUSER_PART_NUMBER") "963-EMF212B7104KGHT")
      )
      (libsource (lib "eagle-import") (part "EMF212B7104KGHT"))
    )
    (comp (ref "C21C")
      (value "0.1u")
      (footprint "eagle-import:CAPC2012X135N")
      (fields
        (field (name "MANUFACTURER_PART_NUMBER") "EMF212B7104KGHT")
        (field (name "MOUSER_PART_NUMBER") "963-EMF212B7104KGHT")
      )
      (libsource (lib "eagle-import") (part "EMF212B7104KGHT"))
    )
    (comp (ref "C21D")
      (value "0.1u")
      (footprint "eagle-import:CAPC2012X135N")
      (fields
        (field (name "MANUFACTURER_PART_NUMBER") "EMF212B7104KGHT")
        (field (name "MOUSER_PART_NUMBER") "963-EMF212B7104KGHT")
      )
      (libsource (lib "eagle-import") (part "EMF212B7104KGHT"))
    )
    (comp (ref "C21E")
      (value "0.1u")
      (footprint "eagle-import:CAPC2012X135N")
      (fields
        (field (name "MANUFACTURER_PART_NUMBER") "EMF212B7104KGHT")
        (field (name "MOUSER_PART_NUMBER") "963-EMF212B7104KGHT")
      )
      (libsource (lib "eagle-import") (part "EMF212B7104KGHT"))
    )
    (comp (ref "C21F")
      (value "0.1u")
      (footprint "eagle-import:CAPC2012X135N")
      (fields
        (field (name "MANUFACTURER_PART_NUMBER") "EMF212B7104KGHT")
        (field (name "MOUSER_PART_NUMBER") "963-EMF212B7104KGHT")
      )
      (libsource (lib "eagle-import") (part "EMF212B7104KGHT"))
    )
    (comp (ref "C21O")
      (value "30uF/400V")
      (footprint "eagle-import:DCP4G053006ID2KSSD")
      (fields
        (field (name "MANUFACTURER_PART_NUMBER") "DCP4G053006ID2KSSD")
        (field (name "MOUSER_PART_NUMBER") "505-DCP4G0536ID2KSSD")
      )
      (libsource (lib "eagle-import") (part "DCP4G053006ID2KSSD"))
    )
    (comp (ref "C22A")
      (value "0.1u, Ceramic Capacitor X7R")
      (footprint "eagle-import:CAPC2012X135N")
      (fields
        (field (name "MANUFACTURER_PART_NUMBER") "EMF212B7104KGHT")
        (field (name "MOUSER_PART_NUMBER") "963-EMF212B7104KGHT")
      )
      (libsource (lib "eagle-import") (part "EMF212B7104KGHT"))
    )
    (comp (ref "C23A")
      (value "0.1u, Ceramic Capacitor X7R")
      (footprint "eagle-import:CAPC2012X135N")
      (fields
        (field (name "MANUFACTURER_PART_NUMBER") "EMF212B7104KGHT")
        (field (name "MOUSER_PART_NUMBER") "963-EMF212B7104KGHT")
      )
      (libsource (lib "eagle-import") (part "EMF212B7104KGHT"))
    )
    (comp (ref "C23O")
      (value "1uF/400V")
      (footprint "eagle-import:MKP4G041005I00JSSD")
      (fields
        (field (name "MANUFACTURER_PART_NUMBER") "MKP4G041005I00JSSD")
        (field (name "MOUSER_PART_NUMBER") "505-MKP4G041005I00JS")
      )
      (libsource (lib "eagle-import") (part "MKP4G041005I00JSSD"))
    )
    (comp (ref "C24A")
      (value "0.1u, Ceramic Capacitor X7R")
      (footprint "eagle-import:CAPC2012X135N")
      (fields
        (field (name "MANUFACTURER_PART_NUMBER") "EMF212B7104KGHT")
        (field (name "MOUSER_PART_NUMBER") "963-EMF212B7104KGHT")
      )
      (libsource (lib "eagle-import") (part "EMF212B7104KGHT"))
    )
    (comp (ref "C24O")
      (value "100uF")
      (footprint "eagle-import:CAPPRD350W60D825H1300")
      (fields
        (field (name "ARROW_PART_NUMBER") "UFW1H101MPD1TD")
        (field (name "MOUSER_PART_NUMBER") "647-UFW1H101MPD1TD")
      )
      (libsource (lib "eagle-import") (part "UFW1H101MPD1TD"))
    )
    (comp (ref "C25O")
      (value "100uF")
      (footprint "eagle-import:CAPPRD350W60D825H1300")
      (fields
        (field (name "ARROW_PART_NUMBER") "UFW1H101MPD1TD")
        (field (name "MOUSER_PART_NUMBER") "647-UFW1H101MPD1TD")
      )
      (libsource (lib "eagle-import") (part "UFW1H101MPD1TD"))
    )
    (comp (ref "C26A")
      (value "4.7u, Ceramic Capacitor X7R")
      (footprint "eagle-import:CAPC2013X140N")
      (fields
        (field (name "MANUFACTURER_PART_NUMBER") "EMK212ABJ475KG-T")
        (field (name "MOUSER_PART_NUMBER") "963-EMK212ABJ475KG-T")
      )
      (libsource (lib "eagle-import") (part "EMK212ABJ475KG-T"))
    )
    (comp (ref "C26B")
      (value "4.7u, Ceramic Capacitor X7R")
      (footprint "eagle-import:CAPC2013X140N")
      (fields
        (field (name "MANUFACTURER_PART_NUMBER") "EMK212ABJ475KG-T")
        (field (name "MOUSER_PART_NUMBER") "963-EMK212ABJ475KG-T")
      )
      (libsource (lib "eagle-import") (part "EMK212ABJ475KG-T"))
    )
    (comp (ref "C26O")
      (value "100uF")
      (footprint "eagle-import:CAPPRD350W60D825H1300")
      (fields
        (field (name "ARROW_PART_NUMBER") "UFW1H101MPD1TD")
        (field (name "MOUSER_PART_NUMBER") "647-UFW1H101MPD1TD")
      )
      (libsource (lib "eagle-import") (part "UFW1H101MPD1TD"))
    )
    (comp (ref "C27A")
      (value "4.7u, Ceramic Capacitor X7R")
      (footprint "eagle-import:CAPC2013X140N")
      (fields
        (field (name "MANUFACTURER_PART_NUMBER") "EMK212ABJ475KG-T")
        (field (name "MOUSER_PART_NUMBER") "963-EMK212ABJ475KG-T")
      )
      (libsource (lib "eagle-import") (part "EMK212ABJ475KG-T"))
    )
    (comp (ref "C27B")
      (value "4.7u, Ceramic Capacitor X7R")
      (footprint "eagle-import:CAPC2013X140N")
      (fields
        (field (name "MANUFACTURER_PART_NUMBER") "EMK212ABJ475KG-T")
        (field (name "MOUSER_PART_NUMBER") "963-EMK212ABJ475KG-T")
      )
      (libsource (lib "eagle-import") (part "EMK212ABJ475KG-T"))
    )
    (comp (ref "C28A")
      (value "0.1u, Ceramic Capacitor X7R")
      (footprint "eagle-import:CAPC2012X135N")
      (fields
        (field (name "MANUFACTURER_PART_NUMBER") "EMF212B7104KGHT")
        (field (name "MOUSER_PART_NUMBER") "963-EMF212B7104KGHT")
      )
      (libsource (lib "eagle-import") (part "EMF212B7104KGHT"))
    )
    (comp (ref "C28B")
      (value "0.1u, Ceramic Capacitor X7R")
      (footprint "eagle-import:CAPC2012X135N")
      (fields
        (field (name "MANUFACTURER_PART_NUMBER") "EMF212B7104KGHT")
        (field (name "MOUSER_PART_NUMBER") "963-EMF212B7104KGHT")
      )
      (libsource (lib "eagle-import") (part "EMF212B7104KGHT"))
    )
    (comp (ref "D1")
      (value "1N4007FFG")
      (footprint "eagle-import:DIOAD1405W86L465D235")
      (fields (field (name "MOUSER_PART_NUMBER") "863-1N4007FFG"))
      (libsource (lib "eagle-import") (part "1N4007FFG"))
    )
    (comp (ref "D2")
      (value "1N4007FFG")
      (footprint "eagle-import:DIOAD1405W86L465D235")
      (fields (field (name "MOUSER_PART_NUMBER") "863-1N4007FFG"))
      (libsource (lib "eagle-import") (part "1N4007FFG"))
    )
    (comp (ref "D3")
      (value "1N4007FFG")
      (footprint "eagle-import:DIOAD1405W86L465D235")
      (fields (field (name "MOUSER_PART_NUMBER") "863-1N4007FFG"))
      (libsource (lib "eagle-import") (part "1N4007FFG"))
    )
    (comp (ref "D4")
      (value "1N4007FFG")
      (footprint "eagle-import:DIOAD1405W86L465D235")
      (fields (field (name "MOUSER_PART_NUMBER") "863-1N4007FFG"))
      (libsource (lib "eagle-import") (part "1N4007FFG"))
    )
    (comp (ref "D5")
      (value "1N4007FFG")
      (footprint "eagle-import:DIOAD1405W86L465D235")
      (fields (field (name "MOUSER_PART_NUMBER") "863-1N4007FFG"))
      (libsource (lib "eagle-import") (part "1N4007FFG"))
    )
    (comp (ref "D6")
      (value "1N4007FFG")
      (footprint "eagle-import:DIOAD1405W86L465D235")
      (fields (field (name "MOUSER_PART_NUMBER") "863-1N4007FFG"))
      (libsource (lib "eagle-import") (part "1N4007FFG"))
    )
    (comp (ref "D7")
      (value "1N4007FFG")
      (footprint "eagle-import:DIOAD1405W86L465D235")
      (fields (field (name "MOUSER_PART_NUMBER") "863-1N4007FFG"))
      (libsource (lib "eagle-import") (part "1N4007FFG"))
    )
    (comp (ref "D8")
      (value "1N4007FFG")
      (footprint "eagle-import:DIOAD1405W86L465D235")
      (fields (field (name "MOUSER_PART_NUMBER") "863-1N4007FFG"))
      (libsource (lib "eagle-import") (part "1N4007FFG"))
    )
    (comp (ref "D9")
      (value "1A/40V/500mV")
      (footprint "eagle-import:SMA-DIODE")
      (libsource (lib "eagle-import") (part "DIODE-SCHOTTKY-SS14"))
    )
    (comp (ref "DIF1")
      (value "SJ2W")
      (footprint "eagle-import:SJ_2")
      (libsource (lib "eagle-import") (part "SJ2W"))
    )
    (comp (ref "DIF3")
      (value "SJ2W")
      (footprint "eagle-import:SJ_2")
      (libsource (lib "eagle-import") (part "SJ2W"))
    )
    (comp (ref "IC1")
      (value "LT3042")
      (footprint "eagle-import:SOP50P490X110-11N")
      (fields
        (field (name "MANUFACTURER_PART_NUMBER") "LT3042EMSE#PBF")
        (field (name "MOUSER_PART_NUMBER") "584-LT3042EMSE#PBF")
      )
      (libsource (lib "eagle-import") (part "LT3042"))
    )
    (comp (ref "IC2")
      (value "AK4493")
      (footprint "eagle-import:LQFP48_")
      (libsource (lib "eagle-import") (part "AK4493"))
    )
    (comp (ref "IC3")
      (value "AK4493")
      (footprint "eagle-import:LQFP48_")
      (libsource (lib "eagle-import") (part "AK4493"))
    )
    (comp (ref "IC4")
      (value "LT3042")
      (footprint "eagle-import:SOP50P490X110-11N")
      (fields
        (field (name "MANUFACTURER_PART_NUMBER") "LT3042EMSE#PBF")
        (field (name "MOUSER_PART_NUMBER") "584-LT3042EMSE#PBF")
      )
      (libsource (lib "eagle-import") (part "LT3042"))
    )
    (comp (ref "IC4A")
      (value "SN74ABT273DBR")
      (footprint "eagle-import:SOP65P780X200-20N")
      (fields (field (name "MOUSER_PART_NUMBER") "595-SN74ABT273DBR"))
      (libsource (lib "eagle-import") (part "SN74ABT273DBR"))
    )
    (comp (ref "IC5")
      (value "LT3042")
      (footprint "eagle-import:SOP50P490X110-11N")
      (fields
        (field (name "MANUFACTURER_PART_NUMBER") "LT3042EMSE#PBF")
        (field (name "MOUSER_PART_NUMBER") "584-LT3042EMSE#PBF")
      )
      (libsource (lib "eagle-import") (part "LT3042"))
    )
    (comp (ref "IC6")
      (value "LT3042")
      (footprint "eagle-import:SOP50P490X110-11N")
      (fields
        (field (name "MANUFACTURER_PART_NUMBER") "LT3042EMSE#PBF")
        (field (name "MOUSER_PART_NUMBER") "584-LT3042EMSE#PBF")
      )
      (libsource (lib "eagle-import") (part "LT3042"))
    )
    (comp (ref "IC7")
      (value "LT3042")
      (footprint "eagle-import:SOP50P490X110-11N")
      (fields
        (field (name "MANUFACTURER_PART_NUMBER") "LT3042EMSE#PBF")
        (field (name "MOUSER_PART_NUMBER") "584-LT3042EMSE#PBF")
      )
      (libsource (lib "eagle-import") (part "LT3042"))
    )
    (comp (ref "IC8")
      (value "LT3042")
      (footprint "eagle-import:SOP50P490X110-11N")
      (fields
        (field (name "MANUFACTURER_PART_NUMBER") "LT3042EMSE#PBF")
        (field (name "MOUSER_PART_NUMBER") "584-LT3042EMSE#PBF")
      )
      (libsource (lib "eagle-import") (part "LT3042"))
    )
    (comp (ref "IN")
      (value "1935213")
      (footprint "eagle-import:1935213")
      (fields (field (name "MOUSER_PART_NUMBER") "651-1935213"))
      (libsource (lib "eagle-import") (part "1935213"))
    )
    (comp (ref "J5")
      (value "CONN_07")
      (footprint "eagle-import:1X07")
      (libsource (lib "eagle-import") (part "CONN_07"))
    )
    (comp (ref "J6")
      (value "CONN_07")
      (footprint "eagle-import:1X07")
      (libsource (lib "eagle-import") (part "CONN_07"))
    )
    (comp (ref "J7")
      (value "CONN_07")
      (footprint "eagle-import:1X07")
      (libsource (lib "eagle-import") (part "CONN_07"))
    )
    (comp (ref "J8")
      (value "CONN_07")
      (footprint "eagle-import:1X07")
      (libsource (lib "eagle-import") (part "CONN_07"))
    )
    (comp (ref "J9")
      (value "CONN_07")
      (footprint "eagle-import:1X07")
      (libsource (lib "eagle-import") (part "CONN_07"))
    )
    (comp (ref "J10")
      (value "CONN_07")
      (footprint "eagle-import:1X07")
      (libsource (lib "eagle-import") (part "CONN_07"))
    )
    (comp (ref "J11")
      (value "CONN_07")
      (footprint "eagle-import:1X07")
      (libsource (lib "eagle-import") (part "CONN_07"))
    )
    (comp (ref "J12")
      (value "CONN_07")
      (footprint "eagle-import:1X07")
      (libsource (lib "eagle-import") (part "CONN_07"))
    )
    (comp (ref "J15")
      (value "XR2A-0811-N")
      (footprint "eagle-import:DIPS762W51P254L1016H390Q8N")
      (fields (field (name "MOUSER_PART_NUMBER") "653-XR2A-0811-N"))
      (libsource (lib "eagle-import") (part "XR2A-0811-N"))
    )
    (comp (ref "J16")
      (value "XR2A-0811-N")
      (footprint "eagle-import:DIPS762W51P254L1016H390Q8N")
      (fields (field (name "MOUSER_PART_NUMBER") "653-XR2A-0811-N"))
      (libsource (lib "eagle-import") (part "XR2A-0811-N"))
    )
    (comp (ref "J17")
      (value "XR2A-0811-N")
      (footprint "eagle-import:DIPS762W51P254L1016H390Q8N")
      (fields (field (name "MOUSER_PART_NUMBER") "653-XR2A-0811-N"))
      (libsource (lib "eagle-import") (part "XR2A-0811-N"))
    )
    (comp (ref "J18")
      (value "XR2A-0811-N")
      (footprint "eagle-import:DIPS762W51P254L1016H390Q8N")
      (fields (field (name "MOUSER_PART_NUMBER") "653-XR2A-0811-N"))
      (libsource (lib "eagle-import") (part "XR2A-0811-N"))
    )
    (comp (ref "J19")
      (value "XR2A-0811-N")
      (footprint "eagle-import:DIPS762W51P254L1016H390Q8N")
      (fields (field (name "MOUSER_PART_NUMBER") "653-XR2A-0811-N"))
      (libsource (lib "eagle-import") (part "XR2A-0811-N"))
    )
    (comp (ref "J20")
      (value "XR2A-0811-N")
      (footprint "eagle-import:DIPS762W51P254L1016H390Q8N")
      (fields (field (name "MOUSER_PART_NUMBER") "653-XR2A-0811-N"))
      (libsource (lib "eagle-import") (part "XR2A-0811-N"))
    )
    (comp (ref "J21")
      (value "CONN_10\"")
      (footprint "eagle-import:1X10")
      (libsource (lib "eagle-import") (part "CONN_10{dblquote}"))
    )
    (comp (ref "J22")
      (value "CONN_10\"")
      (footprint "eagle-import:1X10")
      (libsource (lib "eagle-import") (part "CONN_10{dblquote}"))
    )
    (comp (ref "J26")
      (value "SJ-63033A")
      (footprint "eagle-import:SJ63033A")
      (libsource (lib "eagle-import") (part "SJ-63033A"))
    )
    (comp (ref "J27")
      (value "1935161")
      (footprint "eagle-import:1935161")
      (fields (field (name "MOUSER_PART_NUMBER") "651-1935161"))
      (libsource (lib "eagle-import") (part "1935161"))
    )
    (comp (ref "LDO7")
      (value "LP5907-1.8V")
      (footprint "eagle-import:SOT95P280X145-5N")
      (fields
        (field (name "ARROW_PART_NUMBER") "LP5907MFX-1.8/NOPB")
        (field (name "MOUSER_PART_NUMBER") "595-LP5907MFX-1.8NPB")
      )
      (libsource (lib "eagle-import") (part "LP5907-1.8V"))
    )
    (comp (ref "LDO8")
      (value "LP5907-1.8V")
      (footprint "eagle-import:SOT95P280X145-5N")
      (fields
        (field (name "ARROW_PART_NUMBER") "LP5907MFX-1.8/NOPB")
        (field (name "MOUSER_PART_NUMBER") "595-LP5907MFX-1.8NPB")
      )
      (libsource (lib "eagle-import") (part "LP5907-1.8V"))
    )
    (comp (ref "R1")
      (value "5k")
      (footprint "eagle-import:R0603")
      (libsource (lib "eagle-import") (part "R-US_R0603"))
    )
    (comp (ref "R1A")
      (value "RT0603DRE075R1L")
      (footprint "eagle-import:RESC1608X55N")
      (libsource (lib "eagle-import") (part "RT0603DRE075R1L"))
    )
    (comp (ref "R1B")
      (value "RT0603DRE075R1L")
      (footprint "eagle-import:RESC1608X55N")
      (libsource (lib "eagle-import") (part "RT0603DRE075R1L"))
    )
    (comp (ref "R1O")
      (value "47kOhm")
      (footprint "eagle-import:RESAD1540W55L620D230")
      (fields
        (field (name "MANUFACTURER_PART_NUMBER") "LR1F47K")
        (field (name "MOUSER_PART_NUMBER") "279-LR1F47K")
      )
      (libsource (lib "eagle-import") (part "LR1F47K"))
    )
    (comp (ref "R2A")
      (value "RT0603DRE075R1L")
      (footprint "eagle-import:RESC1608X55N")
      (libsource (lib "eagle-import") (part "RT0603DRE075R1L"))
    )
    (comp (ref "R2B")
      (value "RT0603DRE075R1L")
      (footprint "eagle-import:RESC1608X55N")
      (libsource (lib "eagle-import") (part "RT0603DRE075R1L"))
    )
    (comp (ref "R2O")
      (value "47kOhm")
      (footprint "eagle-import:RESAD1540W55L620D230")
      (fields
        (field (name "MANUFACTURER_PART_NUMBER") "LR1F47K")
        (field (name "MOUSER_PART_NUMBER") "279-LR1F47K")
      )
      (libsource (lib "eagle-import") (part "LR1F47K"))
    )
    (comp (ref "R2P")
      (value "220")
      (footprint "eagle-import:0411_15")
      (libsource (lib "eagle-import") (part "R-US_0411/15"))
    )
    (comp (ref "R3A")
      (value "RT0603DRE075R1L")
      (footprint "eagle-import:RESC1608X55N")
      (libsource (lib "eagle-import") (part "RT0603DRE075R1L"))
    )
    (comp (ref "R3B")
      (value "RT0603DRE075R1L")
      (footprint "eagle-import:RESC1608X55N")
      (libsource (lib "eagle-import") (part "RT0603DRE075R1L"))
    )
    (comp (ref "R3O")
      (value "1M*")
      (footprint "eagle-import:RESAD1540W60L620D230")
      (fields
        (field (name "MANUFACTURER_PART_NUMBER") "LR1F1M0")
        (field (name "MOUSER_PART_NUMBER") "279-LR1F1M0")
      )
      (libsource (lib "eagle-import") (part "LR1F1M0"))
    )
    (comp (ref "R3P")
      (value "220")
      (footprint "eagle-import:0411_15")
      (libsource (lib "eagle-import") (part "R-US_0411/15"))
    )
    (comp (ref "R4A")
      (value "RT0603DRE075R1L")
      (footprint "eagle-import:RESC1608X55N")
      (libsource (lib "eagle-import") (part "RT0603DRE075R1L"))
    )
    (comp (ref "R4B")
      (value "RT0603DRE075R1L")
      (footprint "eagle-import:RESC1608X55N")
      (libsource (lib "eagle-import") (part "RT0603DRE075R1L"))
    )
    (comp (ref "R4O")
      (value "47kOhm")
      (footprint "eagle-import:RESAD1540W55L620D230")
      (fields
        (field (name "MANUFACTURER_PART_NUMBER") "LR1F47K")
        (field (name "MOUSER_PART_NUMBER") "279-LR1F47K")
      )
      (libsource (lib "eagle-import") (part "LR1F47K"))
    )
    (comp (ref "R4P")
      (value "300k")
      (footprint "eagle-import:0411_15")
      (libsource (lib "eagle-import") (part "R-US_0411/15"))
    )
    (comp (ref "R5A")
      (value "10K, Resistor 1%")
      (footprint "eagle-import:RESC2012X50N")
      (fields
        (field (name "MANUFACTURER_PART_NUMBER") "RCS080510K0FKEA")
        (field (name "MOUSER_PART_NUMBER") "71-RCS080510K0FKEA")
      )
      (libsource (lib "eagle-import") (part "RCS080510K0FKEA"))
    )
    (comp (ref "R5O")
      (value "150*")
      (footprint "eagle-import:RESAD1540W55L620D230")
      (fields (field (name "MANUFACTURER_PART_NUMBER") "LR1F150R"))
      (libsource (lib "eagle-import") (part "LR1F150R"))
    )
    (comp (ref "R5P")
      (value "100k")
      (footprint "eagle-import:0411_15")
      (libsource (lib "eagle-import") (part "R-US_0411/15"))
    )
    (comp (ref "R6A")
      (value "1k")
      (footprint "eagle-import:RESC2012X60N")
      (fields
        (field (name "MANUFACTURER_PART_NUMBER") "CHP0805-FX-1001ELF")
        (field (name "MOUSER_PART_NUMBER") "652-CHP0805FX1001ELF")
      )
      (libsource (lib "eagle-import") (part "CHP0805-FX-1001ELF"))
    )
    (comp (ref "R6B")
      (value "1k")
      (footprint "eagle-import:RESC2012X60N")
      (fields
        (field (name "MANUFACTURER_PART_NUMBER") "CHP0805-FX-1001ELF")
        (field (name "MOUSER_PART_NUMBER") "652-CHP0805FX1001ELF")
      )
      (libsource (lib "eagle-import") (part "CHP0805-FX-1001ELF"))
    )
    (comp (ref "R6C")
      (value "1k")
      (footprint "eagle-import:RESC2012X60N")
      (fields
        (field (name "MANUFACTURER_PART_NUMBER") "CHP0805-FX-1001ELF")
        (field (name "MOUSER_PART_NUMBER") "652-CHP0805FX1001ELF")
      )
      (libsource (lib "eagle-import") (part "CHP0805-FX-1001ELF"))
    )
    (comp (ref "R6D")
      (value "1k")
      (footprint "eagle-import:RESC2012X60N")
      (fields
        (field (name "MANUFACTURER_PART_NUMBER") "CHP0805-FX-1001ELF")
        (field (name "MOUSER_PART_NUMBER") "652-CHP0805FX1001ELF")
      )
      (libsource (lib "eagle-import") (part "CHP0805-FX-1001ELF"))
    )
    (comp (ref "R6E")
      (value "1k")
      (footprint "eagle-import:RESC2012X60N")
      (fields
        (field (name "MANUFACTURER_PART_NUMBER") "CHP0805-FX-1001ELF")
        (field (name "MOUSER_PART_NUMBER") "652-CHP0805FX1001ELF")
      )
      (libsource (lib "eagle-import") (part "CHP0805-FX-1001ELF"))
    )
    (comp (ref "R6F")
      (value "1k")
      (footprint "eagle-import:RESC2012X60N")
      (fields
        (field (name "MANUFACTURER_PART_NUMBER") "CHP0805-FX-1001ELF")
        (field (name "MOUSER_PART_NUMBER") "652-CHP0805FX1001ELF")
      )
      (libsource (lib "eagle-import") (part "CHP0805-FX-1001ELF"))
    )
    (comp (ref "R6O")
      (value "47kOhm")
      (footprint "eagle-import:RESAD1540W55L620D230")
      (fields
        (field (name "MANUFACTURER_PART_NUMBER") "LR1F47K")
        (field (name "MOUSER_PART_NUMBER") "279-LR1F47K")
      )
      (libsource (lib "eagle-import") (part "LR1F47K"))
    )
    (comp (ref "R6P")
      (value "330")
      (footprint "eagle-import:0411_15")
      (libsource (lib "eagle-import") (part "R-US_0411/15"))
    )
    (comp (ref "R7A")
      (value "33k")
      (footprint "eagle-import:R0805")
      (fields
        (field (name "MANUFACTURER_PART_NUMBER") "CPF0805B51KE1")
        (field (name "MOUSER_PART_NUMBER") "279-CPF0805B51KE1")
      )
      (libsource (lib "eagle-import") (part "CPF0805B51KE1"))
    )
    (comp (ref "R7B")
      (value "33k")
      (footprint "eagle-import:R0805")
      (fields
        (field (name "MANUFACTURER_PART_NUMBER") "CPF0805B51KE1")
        (field (name "MOUSER_PART_NUMBER") "279-CPF0805B51KE1")
      )
      (libsource (lib "eagle-import") (part "CPF0805B51KE1"))
    )
    (comp (ref "R7C")
      (value "33k")
      (footprint "eagle-import:R0805")
      (fields
        (field (name "MANUFACTURER_PART_NUMBER") "CPF0805B51KE1")
        (field (name "MOUSER_PART_NUMBER") "279-CPF0805B51KE1")
      )
      (libsource (lib "eagle-import") (part "CPF0805B51KE1"))
    )
    (comp (ref "R7D")
      (value "33k")
      (footprint "eagle-import:R0805")
      (fields
        (field (name "MANUFACTURER_PART_NUMBER") "CPF0805B51KE1")
        (field (name "MOUSER_PART_NUMBER") "279-CPF0805B51KE1")
      )
      (libsource (lib "eagle-import") (part "CPF0805B51KE1"))
    )
    (comp (ref "R7E")
      (value "33k")
      (footprint "eagle-import:R0805")
      (fields
        (field (name "MANUFACTURER_PART_NUMBER") "CPF0805B51KE1")
        (field (name "MOUSER_PART_NUMBER") "279-CPF0805B51KE1")
      )
      (libsource (lib "eagle-import") (part "CPF0805B51KE1"))
    )
    (comp (ref "R7F")
      (value "33k")
      (footprint "eagle-import:R0805")
      (fields
        (field (name "MANUFACTURER_PART_NUMBER") "CPF0805B51KE1")
        (field (name "MOUSER_PART_NUMBER") "279-CPF0805B51KE1")
      )
      (libsource (lib "eagle-import") (part "CPF0805B51KE1"))
    )
    (comp (ref "R7O")
      (value "1M*")
      (footprint "eagle-import:RESAD1540W60L620D230")
      (fields
        (field (name "MANUFACTURER_PART_NUMBER") "LR1F1M0")
        (field (name "MOUSER_PART_NUMBER") "279-LR1F1M0")
      )
      (libsource (lib "eagle-import") (part "LR1F1M0"))
    )
    (comp (ref "R8A")
      (value "200k")
      (footprint "eagle-import:R0805")
      (fields
        (field (name "MANUFACTURER_PART_NUMBER") "RR1220P-204-D")
        (field (name "MOUSER_PART_NUMBER") "754-RR1220P-204D")
      )
      (libsource (lib "eagle-import") (part "RR1220P-204-D"))
    )
    (comp (ref "R8B")
      (value "200k")
      (footprint "eagle-import:R0805")
      (fields
        (field (name "MANUFACTURER_PART_NUMBER") "RR1220P-204-D")
        (field (name "MOUSER_PART_NUMBER") "754-RR1220P-204D")
      )
      (libsource (lib "eagle-import") (part "RR1220P-204-D"))
    )
    (comp (ref "R8C")
      (value "200k")
      (footprint "eagle-import:R0805")
      (fields
        (field (name "MANUFACTURER_PART_NUMBER") "RR1220P-204-D")
        (field (name "MOUSER_PART_NUMBER") "754-RR1220P-204D")
      )
      (libsource (lib "eagle-import") (part "RR1220P-204-D"))
    )
    (comp (ref "R8D")
      (value "200k")
      (footprint "eagle-import:R0805")
      (fields
        (field (name "MANUFACTURER_PART_NUMBER") "RR1220P-204-D")
        (field (name "MOUSER_PART_NUMBER") "754-RR1220P-204D")
      )
      (libsource (lib "eagle-import") (part "RR1220P-204-D"))
    )
    (comp (ref "R8E")
      (value "200k")
      (footprint "eagle-import:R0805")
      (fields
        (field (name "MANUFACTURER_PART_NUMBER") "RR1220P-204-D")
        (field (name "MOUSER_PART_NUMBER") "754-RR1220P-204D")
      )
      (libsource (lib "eagle-import") (part "RR1220P-204-D"))
    )
    (comp (ref "R8F")
      (value "200k")
      (footprint "eagle-import:R0805")
      (fields
        (field (name "MANUFACTURER_PART_NUMBER") "RR1220P-204-D")
        (field (name "MOUSER_PART_NUMBER") "754-RR1220P-204D")
      )
      (libsource (lib "eagle-import") (part "RR1220P-204-D"))
    )
    (comp (ref "R8O")
      (value "150*")
      (footprint "eagle-import:RESAD1540W55L620D230")
      (fields (field (name "MANUFACTURER_PART_NUMBER") "LR1F150R"))
      (libsource (lib "eagle-import") (part "LR1F150R"))
    )
    (comp (ref "R9O")
      (value "150*")
      (footprint "eagle-import:RESAD1540W55L620D230")
      (fields (field (name "MANUFACTURER_PART_NUMBER") "LR1F150R"))
      (libsource (lib "eagle-import") (part "LR1F150R"))
    )
    (comp (ref "R10")
      (value "2.2k, 1%")
      (footprint "eagle-import:RCS0805_E3")
      (fields
        (field (name "MANUFACTURER_PART_NUMBER") "RCS08052K20FKEA")
        (field (name "MOUSER_PART_NUMBER") "71-RCS08052K20FKEA")
      )
      (libsource (lib "eagle-import") (part "RCS08052K20FKEA"))
    )
    (comp (ref "R10O")
      (value "150*")
      (footprint "eagle-import:RESAD1540W55L620D230")
      (fields (field (name "MANUFACTURER_PART_NUMBER") "LR1F150R"))
      (libsource (lib "eagle-import") (part "LR1F150R"))
    )
    (comp (ref "R11O")
      (value "10k")
      (footprint "eagle-import:RESAD1540W55L620D230")
      (fields
        (field (name "MANUFACTURER_PART_NUMBER") "LR1F10K")
        (field (name "MOUSER_PART_NUMBER") "279-LR1F10K")
      )
      (libsource (lib "eagle-import") (part "LR1F10K"))
    )
    (comp (ref "R12O")
      (value "182")
      (footprint "eagle-import:RESAD1590W60L630D240")
      (fields (field (name "MANUFACTURER_PART_NUMBER") "MF0207FTE52-182R"))
      (libsource (lib "eagle-import") (part "MF0207FTE52-182R"))
    )
    (comp (ref "R13O")
      (value "47kOhm")
      (footprint "eagle-import:RESAD1540W55L620D230")
      (fields
        (field (name "MANUFACTURER_PART_NUMBER") "LR1F47K")
        (field (name "MOUSER_PART_NUMBER") "279-LR1F47K")
      )
      (libsource (lib "eagle-import") (part "LR1F47K"))
    )
    (comp (ref "R14O")
      (value "182")
      (footprint "eagle-import:RESAD1590W60L630D240")
      (fields (field (name "MANUFACTURER_PART_NUMBER") "MF0207FTE52-182R"))
      (libsource (lib "eagle-import") (part "MF0207FTE52-182R"))
    )
    (comp (ref "R15O")
      (value "47kOhm")
      (footprint "eagle-import:RESAD1540W55L620D230")
      (fields
        (field (name "MANUFACTURER_PART_NUMBER") "LR1F47K")
        (field (name "MOUSER_PART_NUMBER") "279-LR1F47K")
      )
      (libsource (lib "eagle-import") (part "LR1F47K"))
    )
    (comp (ref "R16O")
      (value "182")
      (footprint "eagle-import:RESAD1590W60L630D240")
      (fields (field (name "MANUFACTURER_PART_NUMBER") "MF0207FTE52-182R"))
      (libsource (lib "eagle-import") (part "MF0207FTE52-182R"))
    )
    (comp (ref "R17O")
      (value "47kOhm")
      (footprint "eagle-import:RESAD1540W55L620D230")
      (fields
        (field (name "MANUFACTURER_PART_NUMBER") "LR1F47K")
        (field (name "MOUSER_PART_NUMBER") "279-LR1F47K")
      )
      (libsource (lib "eagle-import") (part "LR1F47K"))
    )
    (comp (ref "R18O")
      (value "182")
      (footprint "eagle-import:RESAD1590W60L630D240")
      (fields (field (name "MANUFACTURER_PART_NUMBER") "MF0207FTE52-182R"))
      (libsource (lib "eagle-import") (part "MF0207FTE52-182R"))
    )
    (comp (ref "R19O")
      (value "10k")
      (footprint "eagle-import:RESAD1540W55L620D230")
      (fields
        (field (name "MANUFACTURER_PART_NUMBER") "LR1F10K")
        (field (name "MOUSER_PART_NUMBER") "279-LR1F10K")
      )
      (libsource (lib "eagle-import") (part "LR1F10K"))
    )
    (comp (ref "R20")
      (value "2.2k, 1%")
      (footprint "eagle-import:RCS0805_E3")
      (fields
        (field (name "MANUFACTURER_PART_NUMBER") "RCS08052K20FKEA")
        (field (name "MOUSER_PART_NUMBER") "71-RCS08052K20FKEA")
      )
      (libsource (lib "eagle-import") (part "RCS08052K20FKEA"))
    )
    (comp (ref "R20O")
      (value "10k")
      (footprint "eagle-import:RESAD1540W55L620D230")
      (fields
        (field (name "MANUFACTURER_PART_NUMBER") "LR1F10K")
        (field (name "MOUSER_PART_NUMBER") "279-LR1F10K")
      )
      (libsource (lib "eagle-import") (part "LR1F10K"))
    )
    (comp (ref "R21A")
      (value "Not Pop.")
      (footprint "eagle-import:R0805-POL")
      (libsource (lib "eagle-import") (part "R-POLR0805"))
    )
    (comp (ref "R21O")
      (value "10k")
      (footprint "eagle-import:RESAD1540W55L620D230")
      (fields
        (field (name "MANUFACTURER_PART_NUMBER") "LR1F10K")
        (field (name "MOUSER_PART_NUMBER") "279-LR1F10K")
      )
      (libsource (lib "eagle-import") (part "LR1F10K"))
    )
    (comp (ref "R22O")
      (value "10k")
      (footprint "eagle-import:RESAD1540W55L620D230")
      (fields
        (field (name "MANUFACTURER_PART_NUMBER") "LR1F10K")
        (field (name "MOUSER_PART_NUMBER") "279-LR1F10K")
      )
      (libsource (lib "eagle-import") (part "LR1F10K"))
    )
    (comp (ref "R23O")
      (value "182")
      (footprint "eagle-import:RESAD1590W60L630D240")
      (fields (field (name "MANUFACTURER_PART_NUMBER") "MF0207FTE52-182R"))
      (libsource (lib "eagle-import") (part "MF0207FTE52-182R"))
    )
    (comp (ref "R24O")
      (value "182")
      (footprint "eagle-import:RESAD1590W60L630D240")
      (fields (field (name "MANUFACTURER_PART_NUMBER") "MF0207FTE52-182R"))
      (libsource (lib "eagle-import") (part "MF0207FTE52-182R"))
    )
    (comp (ref "R25O")
      (value "182")
      (footprint "eagle-import:RESAD1590W60L630D240")
      (fields (field (name "MANUFACTURER_PART_NUMBER") "MF0207FTE52-182R"))
      (libsource (lib "eagle-import") (part "MF0207FTE52-182R"))
    )
    (comp (ref "R26O")
      (value "182")
      (footprint "eagle-import:RESAD1590W60L630D240")
      (fields (field (name "MANUFACTURER_PART_NUMBER") "MF0207FTE52-182R"))
      (libsource (lib "eagle-import") (part "MF0207FTE52-182R"))
    )
    (comp (ref "R27O")
      (value "47kOhm")
      (footprint "eagle-import:RESAD1540W55L620D230")
      (fields
        (field (name "MANUFACTURER_PART_NUMBER") "LR1F47K")
        (field (name "MOUSER_PART_NUMBER") "279-LR1F47K")
      )
      (libsource (lib "eagle-import") (part "LR1F47K"))
    )
    (comp (ref "R28O")
      (value "10k")
      (footprint "eagle-import:RESAD1540W55L620D230")
      (fields
        (field (name "MANUFACTURER_PART_NUMBER") "LR1F10K")
        (field (name "MOUSER_PART_NUMBER") "279-LR1F10K")
      )
      (libsource (lib "eagle-import") (part "LR1F10K"))
    )
    (comp (ref "R29O")
      (value "10k")
      (footprint "eagle-import:RESAD1540W55L620D230")
      (fields
        (field (name "MANUFACTURER_PART_NUMBER") "LR1F10K")
        (field (name "MOUSER_PART_NUMBER") "279-LR1F10K")
      )
      (libsource (lib "eagle-import") (part "LR1F10K"))
    )
    (comp (ref "R30O")
      (value "10k")
      (footprint "eagle-import:RESAD1540W55L620D230")
      (fields
        (field (name "MANUFACTURER_PART_NUMBER") "LR1F10K")
        (field (name "MOUSER_PART_NUMBER") "279-LR1F10K")
      )
      (libsource (lib "eagle-import") (part "LR1F10K"))
    )
    (comp (ref "SH3")
      (value "SHORTA5")
      (footprint "eagle-import:SHORT_ALL-50")
      (libsource (lib "eagle-import") (part "SHORTA5"))
    )
    (comp (ref "SMUTE1")
      (value "SJ")
      (footprint "eagle-import:SJ")
      (libsource (lib "eagle-import") (part "SJ"))
    )
    (comp (ref "SMUTE2")
      (value "SJ")
      (footprint "eagle-import:SJ")
      (libsource (lib "eagle-import") (part "SJ"))
    )
    (comp (ref "SX1")
      (value "VT9-PT")
      (footprint "eagle-import:VT9-PT")
      (libsource (lib "eagle-import") (part "VT9-PT"))
    )
    (comp (ref "SX2")
      (value "VT9-PT")
      (footprint "eagle-import:VT9-PT")
      (libsource (lib "eagle-import") (part "VT9-PT"))
    )
    (comp (ref "TP1")
      (value "TPB2,54")
      (footprint "eagle-import:B2,54")
      (libsource (lib "eagle-import") (part "TPB2,54"))
    )
    (comp (ref "U$1")
      (value "TEENSY40")
      (footprint "eagle-import:TEENSY40")
      (libsource (lib "eagle-import") (part "TEENSY40"))
    )
    (comp (ref "U1")
      (value "AZ1117H-5.0TRE1")
      (footprint "eagle-import:SOT230P700X180-4N")
      (fields (field (name "MOUSER_PART_NUMBER") "621-AZ1117H-5.0TRE1"))
      (libsource (lib "eagle-import") (part "AZ1117H-5.0TRE1"))
    )
    (comp (ref "X1")
      (value "JST-XH-07-PIN-ROUND-PAD")
      (footprint "eagle-import:JST-XH-07-PACKAGE-ROUND-PAD")
      (libsource (lib "eagle-import") (part "JST-XH-07-PIN-ROUND-PAD"))
    )
    (comp (ref "X4")
      (value "JST-XH-04-PIN-ROUND-PAD")
      (footprint "eagle-import:JST-XH-04-PACKAGE-ROUND-PAD")
      (libsource (lib "eagle-import") (part "JST-XH-04-PIN-ROUND-PAD"))
    )
  )
  (nets
    (net (code "1") (name "+3V3") (class "Default")
      (node (ref "C18D") (pin "1") (pinfunction "1_1") (pintype "passive"))
      (node (ref "C22A") (pin "1") (pinfunction "1_1") (pintype "passive"))
      (node (ref "C23A") (pin "1") (pinfunction "1_1") (pintype "passive"))
      (node (ref "C24A") (pin "1") (pinfunction "1_1") (pintype "passive"))
      (node (ref "C26A") (pin "1") (pinfunction "1_1") (pintype "passive"))
      (node (ref "C26B") (pin "1") (pinfunction "1_1") (pintype "passive"))
      (node (ref "C2A1") (pin "1") (pinfunction "1_1") (pintype "passive"))
      (node (ref "C2A2") (pin "1") (pinfunction "1_1") (pintype "passive"))
      (node (ref "C3A") (pin "1") (pinfunction "+_1") (pintype "passive"))
      (node (ref "C3B") (pin "1") (pinfunction "+_1") (pintype "passive"))
      (node (ref "DIF1") (pin "3") (pinfunction "3_3") (pintype "passive"))
      (node (ref "DIF3") (pin "3") (pinfunction "3_3") (pintype "passive"))
      (node (ref "IC2") (pin "14") (pinfunction "INV_14") (pintype "input"))
      (node (ref "IC2") (pin "15") (pinfunction "DEM0_15") (pintype "input"))
      (node (ref "IC2") (pin "17") (pinfunction "ACKS_17") (pintype "input"))
      (node (ref "IC2") (pin "48") (pinfunction "TVDD_48") (pintype "power_in"))
      (node (ref "IC3") (pin "14") (pinfunction "INV_14") (pintype "input"))
      (node (ref "IC3") (pin "15") (pinfunction "DEM0_15") (pintype "input"))
      (node (ref "IC3") (pin "17") (pinfunction "ACKS_17") (pintype "input"))
      (node (ref "IC3") (pin "48") (pinfunction "TVDD_48") (pintype "power_in"))
      (node (ref "IC4A") (pin "20") (pinfunction "VCC_20") (pintype "bidirectional"))
      (node (ref "IC6") (pin "10") (pinfunction "OUT_10") (pintype "bidirectional"))
      (node (ref "IC6") (pin "9") (pinfunction "OUTS_9") (pintype "bidirectional"))
      (node (ref "J11") (pin "2") (pinfunction "2_2") (pintype "passive"))
      (node (ref "J18") (pin "6") (pinfunction "6_6") (pintype "bidirectional"))
      (node (ref "J22") (pin "1") (pinfunction "1_1") (pintype "passive"))
      (node (ref "J5") (pin "5") (pinfunction "5_5") (pintype "passive"))
      (node (ref "J7") (pin "2") (pinfunction "2_2") (pintype "passive"))
      (node (ref "J9") (pin "5") (pinfunction "5_5") (pintype "passive"))
      (node (ref "LDO7") (pin "1") (pinfunction "VIN_1") (pintype "bidirectional"))
      (node (ref "LDO7") (pin "3") (pinfunction "EN_3") (pintype "bidirectional"))
      (node (ref "LDO8") (pin "1") (pinfunction "VIN_1") (pintype "bidirectional"))
      (node (ref "LDO8") (pin "3") (pinfunction "EN_3") (pintype "bidirectional"))
      (node (ref "R10") (pin "1") (pinfunction "1_1") (pintype "passive"))
      (node (ref "R20") (pin "1") (pinfunction "1_1") (pintype "passive"))
      (node (ref "R5A") (pin "2") (pinfunction "2_2") (pintype "passive"))
    )
    (net (code "2") (name "+5V{slash}1") (class "Default")
      (node (ref "C10A1") (pin "1") (pinfunction "1_1") (pintype "passive"))
      (node (ref "C11A") (pin "1") (pinfunction "+_1") (pintype "passive"))
      (node (ref "C14A1") (pin "1") (pinfunction "1_1") (pintype "passive"))
      (node (ref "C15A") (pin "1") (pinfunction "+_1") (pintype "passive"))
      (node (ref "C16A1") (pin "1") (pinfunction "1_1") (pintype "passive"))
      (node (ref "C17A") (pin "1") (pinfunction "+_1") (pintype "passive"))
      (node (ref "C18A") (pin "1") (pinfunction "1_1") (pintype "passive"))
      (node (ref "C6A1") (pin "1") (pinfunction "1_1") (pintype "passive"))
      (node (ref "C7A") (pin "1") (pinfunction "+_1") (pintype "passive"))
      (node (ref "IC1") (pin "10") (pinfunction "OUT_10") (pintype "bidirectional"))
      (node (ref "IC1") (pin "9") (pinfunction "OUTS_9") (pintype "bidirectional"))
      (node (ref "IC2") (pin "19") (pinfunction "VREFHR_19") (pintype "input"))
      (node (ref "IC2") (pin "20") (pinfunction "VREFHR2_20") (pintype "input"))
      (node (ref "IC2") (pin "27") (pinfunction "VDDR_27") (pintype "power_in"))
      (node (ref "IC2") (pin "28") (pinfunction "VDDR2_28") (pintype "power_in"))
      (node (ref "IC2") (pin "33") (pinfunction "VDDL_33") (pintype "power_in"))
      (node (ref "IC2") (pin "34") (pinfunction "VDDL2_34") (pintype "power_in"))
      (node (ref "IC2") (pin "41") (pinfunction "VREFHL_41") (pintype "input"))
      (node (ref "IC2") (pin "42") (pinfunction "VREFHL2_42") (pintype "input"))
      (node (ref "J15") (pin "6") (pinfunction "6_6") (pintype "bidirectional"))
      (node (ref "J5") (pin "4") (pinfunction "4_4") (pintype "passive"))
      (node (ref "J6") (pin "4") (pinfunction "4_4") (pintype "passive"))
      (node (ref "J6") (pin "5") (pinfunction "5_5") (pintype "passive"))
      (node (ref "J7") (pin "6") (pinfunction "6_6") (pintype "passive"))
    )
    (net (code "3") (name "+5V{slash}2") (class "Default")
      (node (ref "C10A2") (pin "1") (pinfunction "1_1") (pintype "passive"))
      (node (ref "C11B") (pin "1") (pinfunction "+_1") (pintype "passive"))
      (node (ref "C14A2") (pin "1") (pinfunction "1_1") (pintype "passive"))
      (node (ref "C15B") (pin "1") (pinfunction "+_1") (pintype "passive"))
      (node (ref "C16A2") (pin "1") (pinfunction "1_1") (pintype "passive"))
      (node (ref "C17B") (pin "1") (pinfunction "+_1") (pintype "passive"))
      (node (ref "C18B") (pin "1") (pinfunction "1_1") (pintype "passive"))
      (node (ref "C6A2") (pin "1") (pinfunction "1_1") (pintype "passive"))
      (node (ref "C7B") (pin "1") (pinfunction "+_1") (pintype "passive"))
      (node (ref "IC3") (pin "19") (pinfunction "VREFHR_19") (pintype "input"))
      (node (ref "IC3") (pin "20") (pinfunction "VREFHR2_20") (pintype "input"))
      (node (ref "IC3") (pin "27") (pinfunction "VDDR_27") (pintype "power_in"))
      (node (ref "IC3") (pin "28") (pinfunction "VDDR2_28") (pintype "power_in"))
      (node (ref "IC3") (pin "33") (pinfunction "VDDL_33") (pintype "power_in"))
      (node (ref "IC3") (pin "34") (pinfunction "VDDL2_34") (pintype "power_in"))
      (node (ref "IC3") (pin "41") (pinfunction "VREFHL_41") (pintype "input"))
      (node (ref "IC3") (pin "42") (pinfunction "VREFHL2_42") (pintype "input"))
      (node (ref "IC5") (pin "10") (pinfunction "OUT_10") (pintype "bidirectional"))
      (node (ref "IC5") (pin "9") (pinfunction "OUTS_9") (pintype "bidirectional"))
      (node (ref "J10") (pin "4") (pinfunction "4_4") (pintype "passive"))
      (node (ref "J10") (pin "5") (pinfunction "5_5") (pintype "passive"))
      (node (ref "J11") (pin "6") (pinfunction "6_6") (pintype "passive"))
      (node (ref "J17") (pin "6") (pinfunction "6_6") (pintype "bidirectional"))
      (node (ref "J9") (pin "4") (pinfunction "4_4") (pintype "passive"))
    )
    (net (code "4") (name "+5V{slash}3") (class "Default")
      (node (ref "BD1") (pin "H3.17") (pinfunction "H3.17_H3.17") (pintype "passive"))
      (node (ref "C18E") (pin "1") (pinfunction "1_1") (pintype "passive"))
      (node (ref "IC8") (pin "10") (pinfunction "OUT_10") (pintype "bidirectional"))
      (node (ref "IC8") (pin "9") (pinfunction "OUTS_9") (pintype "bidirectional"))
      (node (ref "J20") (pin "6") (pinfunction "6_6") (pintype "bidirectional"))
    )
    (net (code "5") (name "+5V{slash}4") (class "Default")
      (node (ref "C18F") (pin "1") (pinfunction "1_1") (pintype "passive"))
      (node (ref "C4A2") (pin "1") (pinfunction "1_1") (pintype "passive"))
      (node (ref "C5B") (pin "1") (pinfunction "+_1") (pintype "passive"))
      (node (ref "IC3") (pin "44") (pinfunction "AVDD_44") (pintype "power_in"))
      (node (ref "IC7") (pin "10") (pinfunction "OUT_10") (pintype "bidirectional"))
      (node (ref "IC7") (pin "9") (pinfunction "OUTS_9") (pintype "bidirectional"))
      (node (ref "J11") (pin "5") (pinfunction "5_5") (pintype "passive"))
      (node (ref "J19") (pin "6") (pinfunction "6_6") (pintype "bidirectional"))
    )
    (net (code "6") (name "+5V{slash}5") (class "Default")
      (node (ref "C18C") (pin "1") (pinfunction "1_1") (pintype "passive"))
      (node (ref "C4A1") (pin "1") (pinfunction "1_1") (pintype "passive"))
      (node (ref "C5A") (pin "1") (pinfunction "+_1") (pintype "passive"))
      (node (ref "IC2") (pin "44") (pinfunction "AVDD_44") (pintype "power_in"))
      (node (ref "IC4") (pin "10") (pinfunction "OUT_10") (pintype "bidirectional"))
      (node (ref "IC4") (pin "9") (pinfunction "OUTS_9") (pintype "bidirectional"))
      (node (ref "J16") (pin "6") (pinfunction "6_6") (pintype "bidirectional"))
      (node (ref "J7") (pin "5") (pinfunction "5_5") (pintype "passive"))
    )
    (net (code "7") (name "+240VDC") (class "Default")
      (node (ref "C18O") (pin "1") (pinfunction "1_1") (pintype "passive"))
      (node (ref "C3P") (pin "1") (pinfunction "+_1") (pintype "bidirectional"))
      (node (ref "C4O") (pin "1") (pinfunction "1_1") (pintype "passive"))
      (node (ref "C5P") (pin "1") (pinfunction "+_1") (pintype "bidirectional"))
      (node (ref "C6P") (pin "1") (pinfunction "+_1") (pintype "bidirectional"))
      (node (ref "C7P") (pin "1") (pinfunction "+_1") (pintype "bidirectional"))
      (node (ref "R6P") (pin "1") (pinfunction "1_1") (pintype "passive"))
      (node (ref "SX1") (pin "6") (pinfunction "6_6") (pintype "passive"))
      (node (ref "SX2") (pin "6") (pinfunction "6_6") (pintype "passive"))
    )
    (net (code "8") (name "6.3_VAC_BLU") (class "Default")
      (node (ref "C1") (pin "2") (pinfunction "2_2") (pintype "passive"))
      (node (ref "C2") (pin "2") (pinfunction "2_2") (pintype "passive"))
      (node (ref "C3") (pin "1") (pinfunction "1_1") (pintype "passive"))
      (node (ref "D6") (pin "1") (pinfunction "K_1") (pintype "bidirectional"))
      (node (ref "D7") (pin "2") (pinfunction "A_2") (pintype "bidirectional"))
      (node (ref "IN") (pin "5") (pinfunction "5_5") (pintype "bidirectional"))
    )
    (net (code "9") (name "6.3_VAC_GRN") (class "Default")
      (node (ref "C1") (pin "1") (pinfunction "1_1") (pintype "passive"))
      (node (ref "C4") (pin "2") (pinfunction "2_2") (pintype "passive"))
      (node (ref "C5") (pin "1") (pinfunction "1_1") (pintype "passive"))
      (node (ref "D5") (pin "1") (pinfunction "K_1") (pintype "bidirectional"))
      (node (ref "D8") (pin "2") (pinfunction "A_2") (pintype "bidirectional"))
      (node (ref "IN") (pin "6") (pinfunction "6_6") (pintype "bidirectional"))
    )
    (net (code "10") (name "66.3VAC{slash}1") (class "Default")
      (node (ref "IN") (pin "1") (pinfunction "1_1") (pintype "bidirectional"))
      (node (ref "R2P") (pin "2") (pinfunction "2_2") (pintype "passive"))
      (node (ref "SX1") (pin "4") (pinfunction "4_4") (pintype "passive"))
      (node (ref "SX2") (pin "4") (pinfunction "4_4") (pintype "passive"))
    )
    (net (code "11") (name "66.3VAC{slash}2") (class "Default")
      (node (ref "IN") (pin "2") (pinfunction "2_2") (pintype "bidirectional"))
      (node (ref "R3P") (pin "1") (pinfunction "1_1") (pintype "passive"))
      (node (ref "SX1") (pin "5") (pinfunction "5_5") (pintype "passive"))
      (node (ref "SX2") (pin "5") (pinfunction "5_5") (pintype "passive"))
    )
    (net (code "12") (name "115_VAC_BLK") (class "Default")
      (node (ref "D1") (pin "1") (pinfunction "K_1") (pintype "bidirectional"))
      (node (ref "D4") (pin "2") (pinfunction "A_2") (pintype "bidirectional"))
      (node (ref "IN") (pin "4") (pinfunction "4_4") (pintype "bidirectional"))
    )
    (net (code "13") (name "115_VAC_RED") (class "Default")
      (node (ref "D2") (pin "1") (pinfunction "K_1") (pintype "bidirectional"))
      (node (ref "D3") (pin "2") (pinfunction "A_2") (pintype "bidirectional"))
      (node (ref "IN") (pin "3") (pinfunction "3_3") (pintype "bidirectional"))
    )
    (net (code "14") (name "AGND") (class "Default")
      (node (ref "C10A1") (pin "2") (pinfunction "2_2") (pintype "passive"))
      (node (ref "C10A2") (pin "2") (pinfunction "2_2") (pintype "passive"))
      (node (ref "C10O") (pin "2") (pinfunction "2_2") (pintype "passive"))
      (node (ref "C11A") (pin "2") (pinfunction "-_2") (pintype "passive"))
      (node (ref "C11B") (pin "2") (pinfunction "-_2") (pintype "passive"))
      (node (ref "C12A1") (pin "2") (pinfunction "2_2") (pintype "passive"))
      (node (ref "C12A2") (pin "2") (pinfunction "2_2") (pintype "passive"))
      (node (ref "C13A") (pin "2") (pinfunction "-_2") (pintype "passive"))
      (node (ref "C13B") (pin "2") (pinfunction "-_2") (pintype "passive"))
      (node (ref "C14A1") (pin "2") (pinfunction "2_2") (pintype "passive"))
      (node (ref "C14A2") (pin "2") (pinfunction "2_2") (pintype "passive"))
      (node (ref "C15A") (pin "2") (pinfunction "-_2") (pintype "passive"))
      (node (ref "C15B") (pin "2") (pinfunction "-_2") (pintype "passive"))
      (node (ref "C16A1") (pin "2") (pinfunction "2_2") (pintype "passive"))
      (node (ref "C16A2") (pin "2") (pinfunction "2_2") (pintype "passive"))
      (node (ref "C16O") (pin "2") (pinfunction "2_2") (pintype "passive"))
      (node (ref "C17A") (pin "2") (pinfunction "-_2") (pintype "passive"))
      (node (ref "C17B") (pin "2") (pinfunction "-_2") (pintype "passive"))
      (node (ref "C18O") (pin "2") (pinfunction "2_2") (pintype "passive"))
      (node (ref "C1O") (pin "2") (pinfunction "2_2") (pintype "passive"))
      (node (ref "C2O") (pin "2") (pinfunction "2_2") (pintype "passive"))
      (node (ref "C4A1") (pin "2") (pinfunction "2_2") (pintype "passive"))
      (node (ref "C4A2") (pin "2") (pinfunction "2_2") (pintype "passive"))
      (node (ref "C4O") (pin "2") (pinfunction "2_2") (pintype "passive"))
      (node (ref "C5A") (pin "2") (pinfunction "-_2") (pintype "passive"))
      (node (ref "C5B") (pin "2") (pinfunction "-_2") (pintype "passive"))
      (node (ref "C6A1") (pin "2") (pinfunction "2_2") (pintype "passive"))
      (node (ref "C6A2") (pin "2") (pinfunction "2_2") (pintype "passive"))
      (node (ref "C7A") (pin "2") (pinfunction "-_2") (pintype "passive"))
      (node (ref "C7B") (pin "2") (pinfunction "-_2") (pintype "passive"))
      (node (ref "C8A1") (pin "2") (pinfunction "2_2") (pintype "passive"))
      (node (ref "C8A2") (pin "2") (pinfunction "2_2") (pintype "passive"))
      (node (ref "C9A") (pin "2") (pinfunction "-_2") (pintype "passive"))
      (node (ref "C9B") (pin "2") (pinfunction "-_2") (pintype "passive"))
      (node (ref "IC2") (pin "21") (pinfunction "VREFLR_21") (pintype "input"))
      (node (ref "IC2") (pin "22") (pinfunction "VREFLR2_22") (pintype "input"))
      (node (ref "IC2") (pin "29") (pinfunction "VSSR_29") (pintype "power_in"))
      (node (ref "IC2") (pin "30") (pinfunction "VSSR2_30") (pintype "power_in"))
      (node (ref "IC2") (pin "31") (pinfunction "VSSL_31") (pintype "power_in"))
      (node (ref "IC2") (pin "32") (pinfunction "VSSL2_32") (pintype "power_in"))
      (node (ref "IC2") (pin "39") (pinfunction "VREFLL_39") (pintype "input"))
      (node (ref "IC2") (pin "40") (pinfunction "VREFLL2_40") (pintype "input"))
      (node (ref "IC2") (pin "45") (pinfunction "AVSS_45") (pintype "power_in"))
      (node (ref "IC2") (pin "P$1") (pinfunction "AVSS_P$1") (pintype "power_in"))
      (node (ref "IC2") (pin "P$10") (pinfunction "AVSS_P$10") (pintype "power_in"))
      (node (ref "IC2") (pin "P$17") (pinfunction "AVSS_P$17") (pintype "power_in"))
      (node (ref "IC2") (pin "P$18") (pinfunction "AVSS_P$18") (pintype "power_in"))
      (node (ref "IC2") (pin "P$2") (pinfunction "AVSS_P$2") (pintype "power_in"))
      (node (ref "IC2") (pin "P$25") (pinfunction "AVSS_P$25") (pintype "power_in"))
      (node (ref "IC2") (pin "P$4") (pinfunction "AVSS_P$4") (pintype "power_in"))
      (node (ref "IC2") (pin "P$6") (pinfunction "AVSS_P$6") (pintype "power_in"))
      (node (ref "IC2") (pin "P$8") (pinfunction "AVSS_P$8") (pintype "power_in"))
      (node (ref "IC3") (pin "21") (pinfunction "VREFLR_21") (pintype "input"))
      (node (ref "IC3") (pin "22") (pinfunction "VREFLR2_22") (pintype "input"))
      (node (ref "IC3") (pin "29") (pinfunction "VSSR_29") (pintype "power_in"))
      (node (ref "IC3") (pin "30") (pinfunction "VSSR2_30") (pintype "power_in"))
      (node (ref "IC3") (pin "31") (pinfunction "VSSL_31") (pintype "power_in"))
      (node (ref "IC3") (pin "32") (pinfunction "VSSL2_32") (pintype "power_in"))
      (node (ref "IC3") (pin "39") (pinfunction "VREFLL_39") (pintype "input"))
      (node (ref "IC3") (pin "40") (pinfunction "VREFLL2_40") (pintype "input"))
      (node (ref "IC3") (pin "45") (pinfunction "AVSS_45") (pintype "power_in"))
      (node (ref "IC3") (pin "P$1") (pinfunction "AVSS_P$1") (pintype "power_in"))
      (node (ref "IC3") (pin "P$10") (pinfunction "AVSS_P$10") (pintype "power_in"))
      (node (ref "IC3") (pin "P$17") (pinfunction "AVSS_P$17") (pintype "power_in"))
      (node (ref "IC3") (pin "P$18") (pinfunction "AVSS_P$18") (pintype "power_in"))
      (node (ref "IC3") (pin "P$2") (pinfunction "AVSS_P$2") (pintype "power_in"))
      (node (ref "IC3") (pin "P$25") (pinfunction "AVSS_P$25") (pintype "power_in"))
      (node (ref "IC3") (pin "P$4") (pinfunction "AVSS_P$4") (pintype "power_in"))
      (node (ref "IC3") (pin "P$6") (pinfunction "AVSS_P$6") (pintype "power_in"))
      (node (ref "IC3") (pin "P$8") (pinfunction "AVSS_P$8") (pintype "power_in"))
      (node (ref "J10") (pin "2") (pinfunction "2_2") (pintype "passive"))
      (node (ref "J10") (pin "7") (pinfunction "7_7") (pintype "passive"))
      (node (ref "J26") (pin "1") (pinfunction "SLEEVE_1") (pintype "bidirectional"))
      (node (ref "J5") (pin "3") (pinfunction "3_3") (pintype "passive"))
      (node (ref "J6") (pin "2") (pinfunction "2_2") (pintype "passive"))
      (node (ref "J6") (pin "7") (pinfunction "7_7") (pintype "passive"))
      (node (ref "J9") (pin "3") (pinfunction "3_3") (pintype "passive"))
      (node (ref "R11O") (pin "2") (pinfunction "2_2") (pintype "passive"))
      (node (ref "R19O") (pin "1") (pinfunction "1_1") (pintype "passive"))
      (node (ref "R20O") (pin "2") (pinfunction "2_2") (pintype "passive"))
      (node (ref "R21O") (pin "1") (pinfunction "1_1") (pintype "passive"))
      (node (ref "R22O") (pin "2") (pinfunction "2_2") (pintype "passive"))
      (node (ref "R28O") (pin "1") (pinfunction "1_1") (pintype "passive"))
      (node (ref "R29O") (pin "2") (pinfunction "2_2") (pintype "passive"))
      (node (ref "R30O") (pin "1") (pinfunction "1_1") (pintype "passive"))
      (node (ref "R3O") (pin "2") (pinfunction "2_2") (pintype "passive"))
      (node (ref "R5O") (pin "1") (pinfunction "1_1") (pintype "passive"))
      (node (ref "R7O") (pin "2") (pinfunction "2_2") (pintype "passive"))
      (node (ref "R8O") (pin "1") (pinfunction "1_1") (pintype "passive"))
      (node (ref "SH3") (pin "2") (pinfunction "P$2_2") (pintype "bidirectional"))
    )
    (net (code "15") (name "BCLK") (class "Default")
      (node (ref "BD1") (pin "H3.11") (pinfunction "H3.11_H3.11") (pintype "passive"))
      (node (ref "IC4A") (pin "18") (pinfunction "8D_18") (pintype "bidirectional"))
      (node (ref "IC4A") (pin "8") (pinfunction "4D_8") (pintype "bidirectional"))
      (node (ref "J21") (pin "3") (pinfunction "3_3") (pintype "passive"))
      (node (ref "J22") (pin "3") (pinfunction "3_3") (pintype "passive"))
    )
    (net (code "16") (name "DATA") (class "Default")
      (node (ref "BD1") (pin "H3.13") (pinfunction "H3.13_H3.13") (pintype "passive"))
      (node (ref "IC4A") (pin "14") (pinfunction "6D_14") (pintype "bidirectional"))
      (node (ref "IC4A") (pin "4") (pinfunction "2D_4") (pintype "bidirectional"))
      (node (ref "J21") (pin "7") (pinfunction "7_7") (pintype "passive"))
      (node (ref "J22") (pin "7") (pinfunction "7_7") (pintype "passive"))
    )
    (net (code "17") (name "DGND") (class "Default")
      (node (ref "BD1") (pin "H3.10") (pinfunction "H3.10_H3.10") (pintype "passive"))
      (node (ref "BD1") (pin "H3.12") (pinfunction "H3.12_H3.12") (pintype "passive"))
      (node (ref "BD1") (pin "H3.14") (pinfunction "H3.14_H3.14") (pintype "passive"))
      (node (ref "BD1") (pin "H3.16") (pinfunction "H3.16_H3.16") (pintype "passive"))
      (node (ref "BD1") (pin "H3.19") (pinfunction "H3.19_H3.19") (pintype "passive"))
      (node (ref "BD1") (pin "H3.8") (pinfunction "H3.8_H3.8") (pintype "passive"))
      (node (ref "C18A") (pin "2") (pinfunction "2_2") (pintype "passive"))
      (node (ref "C18B") (pin "2") (pinfunction "2_2") (pintype "passive"))
      (node (ref "C18C") (pin "2") (pinfunction "2_2") (pintype "passive"))
      (node (ref "C18D") (pin "2") (pinfunction "2_2") (pintype "passive"))
      (node (ref "C18E") (pin "2") (pinfunction "2_2") (pintype "passive"))
      (node (ref "C18F") (pin "2") (pinfunction "2_2") (pintype "passive"))
      (node (ref "C19A") (pin "2") (pinfunction "2_2") (pintype "passive"))
      (node (ref "C19A") (pin "DGND") (pinfunction "2_DGND") (pintype "passive"))
      (node (ref "C19B") (pin "2") (pinfunction "2_2") (pintype "passive"))
      (node (ref "C19B") (pin "DGND") (pinfunction "2_DGND") (pintype "passive"))
      (node (ref "C19C") (pin "2") (pinfunction "2_2") (pintype "passive"))
      (node (ref "C19C") (pin "DGND") (pinfunction "2_DGND") (pintype "passive"))
      (node (ref "C19D") (pin "2") (pinfunction "2_2") (pintype "passive"))
      (node (ref "C19D") (pin "DGND") (pinfunction "2_DGND") (pintype "passive"))
      (node (ref "C19E") (pin "2") (pinfunction "2_2") (pintype "passive"))
      (node (ref "C19E") (pin "DGND") (pinfunction "2_DGND") (pintype "passive"))
      (node (ref "C19F") (pin "2") (pinfunction "2_2") (pintype "passive"))
      (node (ref "C19F") (pin "DGND") (pinfunction "2_DGND") (pintype "passive"))
      (node (ref "C1A") (pin "2") (pinfunction "2_2") (pintype "passive"))
      (node (ref "C1P") (pin "2") (pinfunction "-_2") (pintype "bidirectional"))
      (node (ref "C1P1") (pin "2") (pinfunction "-_2") (pintype "bidirectional"))
      (node (ref "C20A") (pin "2") (pinfunction "2_2") (pintype "passive"))
      (node (ref "C20B") (pin "2") (pinfunction "2_2") (pintype "passive"))
      (node (ref "C20C") (pin "2") (pinfunction "2_2") (pintype "passive"))
      (node (ref "C20D") (pin "2") (pinfunction "2_2") (pintype "passive"))
      (node (ref "C20E") (pin "2") (pinfunction "2_2") (pintype "passive"))
      (node (ref "C20F") (pin "2") (pinfunction "2_2") (pintype "passive"))
      (node (ref "C21A") (pin "2") (pinfunction "2_2") (pintype "passive"))
      (node (ref "C21B") (pin "2") (pinfunction "2_2") (pintype "passive"))
      (node (ref "C21C") (pin "2") (pinfunction "2_2") (pintype "passive"))
      (node (ref "C21D") (pin "2") (pinfunction "2_2") (pintype "passive"))
      (node (ref "C21E") (pin "2") (pinfunction "2_2") (pintype "passive"))
      (node (ref "C21F") (pin "2") (pinfunction "2_2") (pintype "passive"))
      (node (ref "C22A") (pin "2") (pinfunction "2_2") (pintype "passive"))
      (node (ref "C23A") (pin "2") (pinfunction "2_2") (pintype "passive"))
      (node (ref "C24A") (pin "2") (pinfunction "2_2") (pintype "passive"))
      (node (ref "C26A") (pin "2") (pinfunction "2_2") (pintype "passive"))
      (node (ref "C26B") (pin "2") (pinfunction "2_2") (pintype "passive"))
      (node (ref "C27A") (pin "2") (pinfunction "2_2") (pintype "passive"))
      (node (ref "C27B") (pin "2") (pinfunction "2_2") (pintype "passive"))
      (node (ref "C28A") (pin "2") (pinfunction "2_2") (pintype "passive"))
      (node (ref "C28B") (pin "2") (pinfunction "2_2") (pintype "passive"))
      (node (ref "C2A1") (pin "2") (pinfunction "2_2") (pintype "passive"))
      (node (ref "C2A2") (pin "2") (pinfunction "2_2") (pintype "passive"))
      (node (ref "C2P") (pin "2") (pinfunction "-_2") (pintype "bidirectional"))
      (node (ref "C2P1") (pin "2") (pinfunction "-_2") (pintype "bidirectional"))
      (node (ref "C3") (pin "2") (pinfunction "2_2") (pintype "passive"))
      (node (ref "C3A") (pin "2") (pinfunction "-_2") (pintype "passive"))
      (node (ref "C3B") (pin "2") (pinfunction "-_2") (pintype "passive"))
      (node (ref "C3P") (pin "2") (pinfunction "-_2") (pintype "bidirectional"))
      (node (ref "C3P1") (pin "2") (pinfunction "-_2") (pintype "bidirectional"))
      (node (ref "C4P") (pin "2") (pinfunction "-_2") (pintype "bidirectional"))
      (node (ref "C5") (pin "2") (pinfunction "2_2") (pintype "passive"))
      (node (ref "C5P") (pin "2") (pinfunction "-_2") (pintype "bidirectional"))
      (node (ref "C5P1") (pin "2") (pinfunction "-_2") (pintype "bidirectional"))
      (node (ref "C6") (pin "2") (pinfunction "2_2") (pintype "passive"))
      (node (ref "C6P") (pin "2") (pinfunction "-_2") (pintype "bidirectional"))
      (node (ref "C6P1") (pin "2") (pinfunction "-_2") (pintype "bidirectional"))
      (node (ref "C7") (pin "1") (pinfunction "1_1") (pintype "passive"))
      (node (ref "C7P") (pin "2") (pinfunction "-_2") (pintype "bidirectional"))
      (node (ref "C7P1") (pin "2") (pinfunction "-_2") (pintype "bidirectional"))
      (node (ref "D1") (pin "2") (pinfunction "A_2") (pintype "bidirectional"))
      (node (ref "D2") (pin "2") (pinfunction "A_2") (pintype "bidirectional"))
      (node (ref "D5") (pin "2") (pinfunction "A_2") (pintype "bidirectional"))
      (node (ref "D6") (pin "2") (pinfunction "A_2") (pintype "bidirectional"))
      (node (ref "DIF1") (pin "1") (pinfunction "1_1") (pintype "passive"))
      (node (ref "DIF3") (pin "1") (pinfunction "1_1") (pintype "passive"))
      (node (ref "IC1") (pin "11") (pinfunction "GND_11") (pintype "bidirectional"))
      (node (ref "IC1") (pin "8") (pinfunction "GND_8") (pintype "bidirectional"))
      (node (ref "IC1") (pin "P$1") (pinfunction "GND_P$1") (pintype "bidirectional"))
      (node (ref "IC1") (pin "P$2") (pinfunction "GND_P$2") (pintype "bidirectional"))
      (node (ref "IC1") (pin "P$3") (pinfunction "GND_P$3") (pintype "bidirectional"))
      (node (ref "IC1") (pin "P$4") (pinfunction "GND_P$4") (pintype "bidirectional"))
      (node (ref "IC1") (pin "P$5") (pinfunction "GND_P$5") (pintype "bidirectional"))
      (node (ref "IC1") (pin "P$6") (pinfunction "GND_P$6") (pintype "bidirectional"))
      (node (ref "IC2") (pin "13") (pinfunction "PSN_13") (pintype "input"))
      (node (ref "IC2") (pin "16") (pinfunction "LDOE_16") (pintype "input"))
      (node (ref "IC2") (pin "47") (pinfunction "DVSS_47") (pintype "power_in"))
      (node (ref "IC2") (pin "6") (pinfunction "SSLOW_6") (pintype "input"))
      (node (ref "IC3") (pin "13") (pinfunction "PSN_13") (pintype "input"))
      (node (ref "IC3") (pin "16") (pinfunction "LDOE_16") (pintype "input"))
      (node (ref "IC3") (pin "47") (pinfunction "DVSS_47") (pintype "power_in"))
      (node (ref "IC3") (pin "6") (pinfunction "SSLOW_6") (pintype "input"))
      (node (ref "IC4") (pin "11") (pinfunction "GND_11") (pintype "bidirectional"))
      (node (ref "IC4") (pin "8") (pinfunction "GND_8") (pintype "bidirectional"))
      (node (ref "IC4") (pin "P$1") (pinfunction "GND_P$1") (pintype "bidirectional"))
      (node (ref "IC4") (pin "P$2") (pinfunction "GND_P$2") (pintype "bidirectional"))
      (node (ref "IC4") (pin "P$3") (pinfunction "GND_P$3") (pintype "bidirectional"))
      (node (ref "IC4") (pin "P$4") (pinfunction "GND_P$4") (pintype "bidirectional"))
      (node (ref "IC4") (pin "P$5") (pinfunction "GND_P$5") (pintype "bidirectional"))
      (node (ref "IC4") (pin "P$6") (pinfunction "GND_P$6") (pintype "bidirectional"))
      (node (ref "IC4A") (pin "10") (pinfunction "GND_10") (pintype "bidirectional"))
      (node (ref "IC4A") (pin "17") (pinfunction "7D_17") (pintype "bidirectional"))
      (node (ref "IC4A") (pin "7") (pinfunction "3D_7") (pintype "bidirectional"))
      (node (ref "IC5") (pin "11") (pinfunction "GND_11") (pintype "bidirectional"))
      (node (ref "IC5") (pin "8") (pinfunction "GND_8") (pintype "bidirectional"))
      (node (ref "IC5") (pin "P$1") (pinfunction "GND_P$1") (pintype "bidirectional"))
      (node (ref "IC5") (pin "P$2") (pinfunction "GND_P$2") (pintype "bidirectional"))
      (node (ref "IC5") (pin "P$3") (pinfunction "GND_P$3") (pintype "bidirectional"))
      (node (ref "IC5") (pin "P$4") (pinfunction "GND_P$4") (pintype "bidirectional"))
      (node (ref "IC5") (pin "P$5") (pinfunction "GND_P$5") (pintype "bidirectional"))
      (node (ref "IC5") (pin "P$6") (pinfunction "GND_P$6") (pintype "bidirectional"))
      (node (ref "IC6") (pin "11") (pinfunction "GND_11") (pintype "bidirectional"))
      (node (ref "IC6") (pin "8") (pinfunction "GND_8") (pintype "bidirectional"))
      (node (ref "IC6") (pin "P$1") (pinfunction "GND_P$1") (pintype "bidirectional"))
      (node (ref "IC6") (pin "P$2") (pinfunction "GND_P$2") (pintype "bidirectional"))
      (node (ref "IC6") (pin "P$3") (pinfunction "GND_P$3") (pintype "bidirectional"))
      (node (ref "IC6") (pin "P$4") (pinfunction "GND_P$4") (pintype "bidirectional"))
      (node (ref "IC6") (pin "P$5") (pinfunction "GND_P$5") (pintype "bidirectional"))
      (node (ref "IC6") (pin "P$6") (pinfunction "GND_P$6") (pintype "bidirectional"))
      (node (ref "IC7") (pin "11") (pinfunction "GND_11") (pintype "bidirectional"))
      (node (ref "IC7") (pin "8") (pinfunction "GND_8") (pintype "bidirectional"))
      (node (ref "IC7") (pin "P$1") (pinfunction "GND_P$1") (pintype "bidirectional"))
      (node (ref "IC7") (pin "P$2") (pinfunction "GND_P$2") (pintype "bidirectional"))
      (node (ref "IC7") (pin "P$3") (pinfunction "GND_P$3") (pintype "bidirectional"))
      (node (ref "IC7") (pin "P$4") (pinfunction "GND_P$4") (pintype "bidirectional"))
      (node (ref "IC7") (pin "P$5") (pinfunction "GND_P$5") (pintype "bidirectional"))
      (node (ref "IC7") (pin "P$6") (pinfunction "GND_P$6") (pintype "bidirectional"))
      (node (ref "IC8") (pin "11") (pinfunction "GND_11") (pintype "bidirectional"))
      (node (ref "IC8") (pin "8") (pinfunction "GND_8") (pintype "bidirectional"))
      (node (ref "IC8") (pin "P$1") (pinfunction "GND_P$1") (pintype "bidirectional"))
      (node (ref "IC8") (pin "P$2") (pinfunction "GND_P$2") (pintype "bidirectional"))
      (node (ref "IC8") (pin "P$3") (pinfunction "GND_P$3") (pintype "bidirectional"))
      (node (ref "IC8") (pin "P$4") (pinfunction "GND_P$4") (pintype "bidirectional"))
      (node (ref "IC8") (pin "P$5") (pinfunction "GND_P$5") (pintype "bidirectional"))
      (node (ref "IC8") (pin "P$6") (pinfunction "GND_P$6") (pintype "bidirectional"))
      (node (ref "J11") (pin "3") (pinfunction "3_3") (pintype "passive"))
      (node (ref "J15") (pin "5") (pinfunction "5_5") (pintype "bidirectional"))
      (node (ref "J16") (pin "5") (pinfunction "5_5") (pintype "bidirectional"))
      (node (ref "J17") (pin "5") (pinfunction "5_5") (pintype "bidirectional"))
      (node (ref "J18") (pin "5") (pinfunction "5_5") (pintype "bidirectional"))
      (node (ref "J19") (pin "5") (pinfunction "5_5") (pintype "bidirectional"))
      (node (ref "J20") (pin "5") (pinfunction "5_5") (pintype "bidirectional"))
      (node (ref "J21") (pin "1") (pinfunction "1_1") (pintype "passive"))
      (node (ref "J21") (pin "4") (pinfunction "4_4") (pintype "passive"))
      (node (ref "J22") (pin "4") (pinfunction "4_4") (pintype "passive"))
      (node (ref "J7") (pin "3") (pinfunction "3_3") (pintype "passive"))
      (node (ref "LDO7") (pin "2") (pinfunction "GND_2") (pintype "bidirectional"))
      (node (ref "LDO7") (pin "DGND") (pinfunction "GND_DGND") (pintype "bidirectional"))
      (node (ref "LDO7") (pin "DGND2") (pinfunction "GND_DGND2") (pintype "bidirectional"))
      (node (ref "LDO7") (pin "DGND3") (pinfunction "GND_DGND3") (pintype "bidirectional"))
      (node (ref "LDO8") (pin "2") (pinfunction "GND_2") (pintype "bidirectional"))
      (node (ref "LDO8") (pin "DGND") (pinfunction "GND_DGND") (pintype "bidirectional"))
      (node (ref "LDO8") (pin "DGND2") (pinfunction "GND_DGND2") (pintype "bidirectional"))
      (node (ref "LDO8") (pin "DGND3") (pinfunction "GND_DGND3") (pintype "bidirectional"))
      (node (ref "R1") (pin "1") (pinfunction "1_1") (pintype "passive"))
      (node (ref "R21A") (pin "2") (pinfunction "2_2") (pintype "passive"))
      (node (ref "R21A") (pin "DGND") (pinfunction "2_DGND") (pintype "passive"))
      (node (ref "R5P") (pin "1") (pinfunction "1_1") (pintype "passive"))
      (node (ref "R6A") (pin "2") (pinfunction "2_2") (pintype "passive"))
      (node (ref "R6B") (pin "2") (pinfunction "2_2") (pintype "passive"))
      (node (ref "R6C") (pin "2") (pinfunction "2_2") (pintype "passive"))
      (node (ref "R6D") (pin "2") (pinfunction "2_2") (pintype "passive"))
      (node (ref "R6E") (pin "2") (pinfunction "2_2") (pintype "passive"))
      (node (ref "R6F") (pin "2") (pinfunction "2_2") (pintype "passive"))
      (node (ref "R7A") (pin "2") (pinfunction "2_2") (pintype "passive"))
      (node (ref "R7B") (pin "2") (pinfunction "2_2") (pintype "passive"))
      (node (ref "R7C") (pin "2") (pinfunction "2_2") (pintype "passive"))
      (node (ref "R7D") (pin "2") (pinfunction "2_2") (pintype "passive"))
      (node (ref "R7E") (pin "2") (pinfunction "2_2") (pintype "passive"))
      (node (ref "R7F") (pin "2") (pinfunction "2_2") (pintype "passive"))
      (node (ref "SH3") (pin "1") (pinfunction "P$1_1") (pintype "bidirectional"))
      (node (ref "SMUTE1") (pin "2") (pinfunction "2_2") (pintype "passive"))
      (node (ref "SMUTE2") (pin "2") (pinfunction "2_2") (pintype "passive"))
      (node (ref "U$1") (pin "GND1") (pinfunction "GND1_GND1") (pintype "bidirectional"))
      (node (ref "U$1") (pin "GND2") (pinfunction "GND2_GND2") (pintype "bidirectional"))
      (node (ref "U$1") (pin "GND3") (pinfunction "GND3_GND3") (pintype "bidirectional"))
      (node (ref "U1") (pin "1") (pinfunction "ADJ/GND_1") (pintype "bidirectional"))
      (node (ref "X1") (pin "7") (pinfunction "S_7") (pintype "passive"))
      (node (ref "X4") (pin "4") (pinfunction "S_4") (pintype "passive"))
    )
    (net (code "18") (name "DIF0") (class "Default")
      (node (ref "IC2") (pin "10") (pinfunction "DIF0_10") (pintype "input"))
      (node (ref "J5") (pin "7") (pinfunction "7_7") (pintype "passive"))
      (node (ref "U$1") (pin "1-TX1") (pinfunction "1-TX1/CTX2_1-TX1") (pintype "bidirectional"))
    )
    (net (code "19") (name "DIF1") (class "Default")
      (node (ref "IC2") (pin "11") (pinfunction "DIF1_11") (pintype "input"))
      (node (ref "J5") (pin "6") (pinfunction "6_6") (pintype "passive"))
      (node (ref "U$1") (pin "2-OUT2") (pinfunction "2-OUT2_2-OUT2") (pintype "bidirectional"))
    )
    (net (code "20") (name "L+") (class "Default")
      (node (ref "R1O") (pin "1") (pinfunction "1_1") (pintype "passive"))
      (node (ref "R23O") (pin "1") (pinfunction "1_1") (pintype "passive"))
      (node (ref "R24O") (pin "1") (pinfunction "1_1") (pintype "passive"))
    )
    (net (code "21") (name "L-") (class "Default")
      (node (ref "R25O") (pin "1") (pinfunction "1_1") (pintype "passive"))
      (node (ref "R26O") (pin "1") (pinfunction "1_1") (pintype "passive"))
      (node (ref "R6O") (pin "1") (pinfunction "1_1") (pintype "passive"))
    )
    (net (code "22") (name "LRCK") (class "Default")
      (node (ref "BD1") (pin "H3.15") (pinfunction "H3.15_H3.15") (pintype "passive"))
      (node (ref "IC4A") (pin "13") (pinfunction "5D_13") (pintype "bidirectional"))
      (node (ref "IC4A") (pin "3") (pinfunction "1D_3") (pintype "bidirectional"))
      (node (ref "J21") (pin "8") (pinfunction "8_8") (pintype "passive"))
      (node (ref "J22") (pin "8") (pinfunction "8_8") (pintype "passive"))
    )
    (net (code "23") (name "L_OUT") (class "Default")
      (node (ref "C7O") (pin "1") (pinfunction "1_1") (pintype "passive"))
      (node (ref "C9O") (pin "1") (pinfunction "1_1") (pintype "passive"))
      (node (ref "J26") (pin "2") (pinfunction "TIP_2") (pintype "bidirectional"))
      (node (ref "R4O") (pin "1") (pinfunction "1_1") (pintype "passive"))
      (node (ref "R7O") (pin "1") (pinfunction "1_1") (pintype "passive"))
    )
    (net (code "24") (name "MCLK") (class "Default")
      (node (ref "BD1") (pin "H3.7") (pinfunction "H3.7_H3.7") (pintype "passive"))
      (node (ref "IC4A") (pin "11") (pinfunction "CLK_11") (pintype "bidirectional"))
      (node (ref "J22") (pin "10") (pinfunction "10_10") (pintype "passive"))
      (node (ref "R4A") (pin "1") (pinfunction "1_1") (pintype "passive"))
      (node (ref "R4B") (pin "1") (pinfunction "1_1") (pintype "passive"))
    )
    (net (code "25") (name "Net-(C1O-Pad1)") (class "Default")
      (node (ref "C1O") (pin "1") (pinfunction "1_1") (pintype "passive"))
      (node (ref "R8O") (pin "2") (pinfunction "2_2") (pintype "passive"))
      (node (ref "SX2") (pin "3") (pinfunction "3_3") (pintype "passive"))
    )
    (net (code "26") (name "Net-(C1P-+)") (class "Default")
      (node (ref "C1P") (pin "1") (pinfunction "+_1") (pintype "bidirectional"))
      (node (ref "D3") (pin "1") (pinfunction "K_1") (pintype "bidirectional"))
      (node (ref "D4") (pin "1") (pinfunction "K_1") (pintype "bidirectional"))
      (node (ref "J27") (pin "1") (pinfunction "1_1") (pintype "bidirectional"))
    )
    (net (code "27") (name "Net-(C2O-Pad1)") (class "Default")
      (node (ref "C2O") (pin "1") (pinfunction "1_1") (pintype "passive"))
      (node (ref "SX1") (pin "9") (pinfunction "9_9") (pintype "passive"))
    )
    (net (code "28") (name "Net-(C2P-+)") (class "Default")
      (node (ref "C2P") (pin "1") (pinfunction "+_1") (pintype "bidirectional"))
      (node (ref "J27") (pin "2") (pinfunction "2_2") (pintype "bidirectional"))
      (node (ref "R6P") (pin "2") (pinfunction "2_2") (pintype "passive"))
    )
    (net (code "29") (name "Net-(C4P-+)") (class "Default")
      (node (ref "C4P") (pin "1") (pinfunction "+_1") (pintype "bidirectional"))
      (node (ref "R2P") (pin "1") (pinfunction "1_1") (pintype "passive"))
      (node (ref "R3P") (pin "2") (pinfunction "2_2") (pintype "passive"))
      (node (ref "R4P") (pin "1") (pinfunction "1_1") (pintype "passive"))
      (node (ref "R5P") (pin "2") (pinfunction "2_2") (pintype "passive"))
      (node (ref "TP1") (pin "TP") (pinfunction "TP_TP") (pintype "input"))
    )
    (net (code "30") (name "Net-(C5O-Pad2)") (class "Default")
      (node (ref "C5O") (pin "2") (pinfunction "2_2") (pintype "passive"))
      (node (ref "R9O") (pin "2") (pinfunction "2_2") (pintype "passive"))
      (node (ref "SX1") (pin "8") (pinfunction "8_8") (pintype "passive"))
    )
    (net (code "31") (name "Net-(C6O-Pad1)") (class "Default")
      (node (ref "C6O") (pin "1") (pinfunction "1_1") (pintype "passive"))
      (node (ref "C7O") (pin "2") (pinfunction "2_2") (pintype "passive"))
      (node (ref "R10O") (pin "1") (pinfunction "1_1") (pintype "passive"))
      (node (ref "R2O") (pin "1") (pinfunction "1_1") (pintype "passive"))
      (node (ref "SX2") (pin "1") (pinfunction "1_1") (pintype "passive"))
    )
    (net (code "32") (name "Net-(C6O-Pad2)") (class "Default")
      (node (ref "C6O") (pin "2") (pinfunction "2_2") (pintype "passive"))
      (node (ref "R10O") (pin "2") (pinfunction "2_2") (pintype "passive"))
      (node (ref "SX2") (pin "8") (pinfunction "8_8") (pintype "passive"))
    )
    (net (code "33") (name "Net-(C9A-+)") (class "Default")
      (node (ref "C8A1") (pin "1") (pinfunction "1_1") (pintype "passive"))
      (node (ref "C9A") (pin "1") (pinfunction "+_1") (pintype "passive"))
      (node (ref "IC2") (pin "38") (pinfunction "VCML_38") (pintype "power_in"))
      (node (ref "J7") (pin "7") (pinfunction "7_7") (pintype "passive"))
    )
    (net (code "34") (name "Net-(C9B-+)") (class "Default")
      (node (ref "C8A2") (pin "1") (pinfunction "1_1") (pintype "passive"))
      (node (ref "C9B") (pin "1") (pinfunction "+_1") (pintype "passive"))
      (node (ref "IC3") (pin "38") (pinfunction "VCML_38") (pintype "power_in"))
      (node (ref "J11") (pin "7") (pinfunction "7_7") (pintype "passive"))
    )
    (net (code "35") (name "Net-(C9O-Pad2)") (class "Default")
      (node (ref "C9O") (pin "2") (pinfunction "2_2") (pintype "passive"))
      (node (ref "R4O") (pin "2") (pinfunction "2_2") (pintype "passive"))
      (node (ref "R6O") (pin "2") (pinfunction "2_2") (pintype "passive"))
      (node (ref "SX2") (pin "2") (pinfunction "2_2") (pintype "passive"))
    )
    (net (code "36") (name "Net-(C10O-Pad1)") (class "Default")
      (node (ref "C10O") (pin "1") (pinfunction "1_1") (pintype "passive"))
      (node (ref "SX2") (pin "9") (pinfunction "9_9") (pintype "passive"))
    )
    (net (code "37") (name "Net-(C11O-+)") (class "Default")
      (node (ref "C11O") (pin "1") (pinfunction "+_1") (pintype "passive"))
      (node (ref "IC3") (pin "36") (pinfunction "AOUTLP_36") (pintype "output"))
      (node (ref "J10") (pin "1") (pinfunction "1_1") (pintype "passive"))
    )
    (net (code "38") (name "Net-(C11O--)") (class "Default")
      (node (ref "C11O") (pin "2") (pinfunction "-_2") (pintype "passive"))
      (node (ref "R12O") (pin "2") (pinfunction "2_2") (pintype "passive"))
      (node (ref "R19O") (pin "2") (pinfunction "2_2") (pintype "passive"))
    )
    (net (code "39") (name "Net-(C12O-+)") (class "Default")
      (node (ref "C12O") (pin "1") (pinfunction "+_1") (pintype "passive"))
      (node (ref "IC3") (pin "25") (pinfunction "AOUTRP_25") (pintype "output"))
      (node (ref "J9") (pin "1") (pinfunction "1_1") (pintype "passive"))
    )
    (net (code "40") (name "Net-(C12O--)") (class "Default")
      (node (ref "C12O") (pin "2") (pinfunction "-_2") (pintype "passive"))
      (node (ref "R18O") (pin "2") (pinfunction "2_2") (pintype "passive"))
      (node (ref "R20O") (pin "1") (pinfunction "1_1") (pintype "passive"))
    )
    (net (code "41") (name "Net-(C13A-+)") (class "Default")
      (node (ref "C12A1") (pin "1") (pinfunction "1_1") (pintype "passive"))
      (node (ref "C13A") (pin "1") (pinfunction "+_1") (pintype "passive"))
      (node (ref "IC2") (pin "23") (pinfunction "VCMR_23") (pintype "power_in"))
      (node (ref "J5") (pin "2") (pinfunction "2_2") (pintype "passive"))
    )
    (net (code "42") (name "Net-(C13B-+)") (class "Default")
      (node (ref "C12A2") (pin "1") (pinfunction "1_1") (pintype "passive"))
      (node (ref "C13B") (pin "1") (pinfunction "+_1") (pintype "passive"))
      (node (ref "IC3") (pin "23") (pinfunction "VCMR_23") (pintype "power_in"))
      (node (ref "J9") (pin "2") (pinfunction "2_2") (pintype "passive"))
    )
    (net (code "43") (name "Net-(C13O-+)") (class "Default")
      (node (ref "C13O") (pin "1") (pinfunction "+_1") (pintype "passive"))
      (node (ref "IC3") (pin "35") (pinfunction "AOUTLN_35") (pintype "output"))
      (node (ref "J10") (pin "3") (pinfunction "3_3") (pintype "passive"))
    )
    (net (code "44") (name "Net-(C13O--)") (class "Default")
      (node (ref "C13O") (pin "2") (pinfunction "-_2") (pintype "passive"))
      (node (ref "R14O") (pin "2") (pinfunction "2_2") (pintype "passive"))
      (node (ref "R21O") (pin "2") (pinfunction "2_2") (pintype "passive"))
    )
    (net (code "45") (name "Net-(C14O-+)") (class "Default")
      (node (ref "C14O") (pin "1") (pinfunction "+_1") (pintype "passive"))
      (node (ref "IC3") (pin "26") (pinfunction "AOUTRN_26") (pintype "output"))
      (node (ref "J10") (pin "6") (pinfunction "6_6") (pintype "passive"))
    )
    (net (code "46") (name "Net-(C14O--)") (class "Default")
      (node (ref "C14O") (pin "2") (pinfunction "-_2") (pintype "passive"))
      (node (ref "R11O") (pin "1") (pinfunction "1_1") (pintype "passive"))
      (node (ref "R16O") (pin "2") (pinfunction "2_2") (pintype "passive"))
    )
    (net (code "47") (name "Net-(C15O-+)") (class "Default")
      (node (ref "C15O") (pin "1") (pinfunction "+_1") (pintype "passive"))
      (node (ref "IC2") (pin "25") (pinfunction "AOUTRP_25") (pintype "output"))
      (node (ref "J5") (pin "1") (pinfunction "1_1") (pintype "passive"))
    )
    (net (code "48") (name "Net-(C15O--)") (class "Default")
      (node (ref "C15O") (pin "2") (pinfunction "-_2") (pintype "passive"))
      (node (ref "R24O") (pin "2") (pinfunction "2_2") (pintype "passive"))
      (node (ref "R28O") (pin "2") (pinfunction "2_2") (pintype "passive"))
    )
    (net (code "49") (name "Net-(C16O-Pad1)") (class "Default")
      (node (ref "C16O") (pin "1") (pinfunction "1_1") (pintype "passive"))
      (node (ref "R5O") (pin "2") (pinfunction "2_2") (pintype "passive"))
      (node (ref "SX1") (pin "3") (pinfunction "3_3") (pintype "passive"))
    )
    (net (code "50") (name "Net-(C21O-Pad2)") (class "Default")
      (node (ref "C21O") (pin "2") (pinfunction "2_2") (pintype "passive"))
      (node (ref "C5O") (pin "1") (pinfunction "1_1") (pintype "passive"))
      (node (ref "R15O") (pin "1") (pinfunction "1_1") (pintype "passive"))
      (node (ref "R9O") (pin "1") (pinfunction "1_1") (pintype "passive"))
      (node (ref "SX1") (pin "1") (pinfunction "1_1") (pintype "passive"))
    )
    (net (code "51") (name "Net-(C23O-Pad2)") (class "Default")
      (node (ref "C23O") (pin "2") (pinfunction "2_2") (pintype "passive"))
      (node (ref "R17O") (pin "2") (pinfunction "2_2") (pintype "passive"))
      (node (ref "R27O") (pin "2") (pinfunction "2_2") (pintype "passive"))
      (node (ref "SX1") (pin "2") (pinfunction "2_2") (pintype "passive"))
    )
    (net (code "52") (name "Net-(C24O-+)") (class "Default")
      (node (ref "C24O") (pin "1") (pinfunction "+_1") (pintype "passive"))
      (node (ref "IC2") (pin "36") (pinfunction "AOUTLP_36") (pintype "output"))
      (node (ref "J6") (pin "1") (pinfunction "1_1") (pintype "passive"))
    )
    (net (code "53") (name "Net-(C24O--)") (class "Default")
      (node (ref "C24O") (pin "2") (pinfunction "-_2") (pintype "passive"))
      (node (ref "R23O") (pin "2") (pinfunction "2_2") (pintype "passive"))
      (node (ref "R29O") (pin "1") (pinfunction "1_1") (pintype "passive"))
    )
    (net (code "54") (name "Net-(C25O-+)") (class "Default")
      (node (ref "C25O") (pin "1") (pinfunction "+_1") (pintype "passive"))
      (node (ref "IC2") (pin "26") (pinfunction "AOUTRN_26") (pintype "output"))
      (node (ref "J6") (pin "6") (pinfunction "6_6") (pintype "passive"))
    )
    (net (code "55") (name "Net-(C25O--)") (class "Default")
      (node (ref "C25O") (pin "2") (pinfunction "-_2") (pintype "passive"))
      (node (ref "R25O") (pin "2") (pinfunction "2_2") (pintype "passive"))
      (node (ref "R30O") (pin "2") (pinfunction "2_2") (pintype "passive"))
    )
    (net (code "56") (name "Net-(C26O-+)") (class "Default")
      (node (ref "C26O") (pin "1") (pinfunction "+_1") (pintype "passive"))
      (node (ref "IC2") (pin "35") (pinfunction "AOUTLN_35") (pintype "output"))
      (node (ref "J6") (pin "3") (pinfunction "3_3") (pintype "passive"))
    )
    (net (code "57") (name "Net-(C26O--)") (class "Default")
      (node (ref "C26O") (pin "2") (pinfunction "-_2") (pintype "passive"))
      (node (ref "R22O") (pin "1") (pinfunction "1_1") (pintype "passive"))
      (node (ref "R26O") (pin "2") (pinfunction "2_2") (pintype "passive"))
    )
    (net (code "58") (name "Net-(D9-PadA)") (class "Default")
      (node (ref "D9") (pin "A") (pinfunction "A_A") (pintype "passive"))
      (node (ref "U$1") (pin "VUSB") (pinfunction "VUSB_VUSB") (pintype "bidirectional"))
    )
    (net (code "59") (name "Net-(IC1-ILIM)") (class "Default")
      (node (ref "IC1") (pin "5") (pinfunction "ILIM_5") (pintype "bidirectional"))
      (node (ref "J15") (pin "2") (pinfunction "2_2") (pintype "bidirectional"))
      (node (ref "R6A") (pin "1") (pinfunction "1_1") (pintype "passive"))
    )
    (net (code "60") (name "Net-(IC1-PG)") (class "Default")
      (node (ref "IC1") (pin "4") (pinfunction "PG_4") (pintype "bidirectional"))
      (node (ref "J15") (pin "1") (pinfunction "1_1") (pintype "bidirectional"))
      (node (ref "R8A") (pin "2") (pinfunction "2_2") (pintype "passive"))
    )
    (net (code "61") (name "Net-(IC1-PGFB)") (class "Default")
      (node (ref "IC1") (pin "6") (pinfunction "PGFB_6") (pintype "bidirectional"))
      (node (ref "J15") (pin "3") (pinfunction "3_3") (pintype "bidirectional"))
    )
    (net (code "62") (name "Net-(IC1-SET)") (class "Default")
      (node (ref "C19A") (pin "1") (pinfunction "1_1") (pintype "passive"))
      (node (ref "IC1") (pin "7") (pinfunction "SET_7") (pintype "bidirectional"))
      (node (ref "J15") (pin "4") (pinfunction "4_4") (pintype "bidirectional"))
      (node (ref "R7A") (pin "1") (pinfunction "1_1") (pintype "passive"))
    )
    (net (code "63") (name "Net-(IC2-BICK)") (class "Default")
      (node (ref "IC2") (pin "3") (pinfunction "BICK_3") (pintype "input"))
      (node (ref "J8") (pin "5") (pinfunction "5_5") (pintype "passive"))
      (node (ref "R1A") (pin "2") (pinfunction "2_2") (pintype "passive"))
    )
    (net (code "64") (name "Net-(IC2-DIF2)") (class "Default")
      (node (ref "DIF1") (pin "2") (pinfunction "2_2") (pintype "passive"))
      (node (ref "IC2") (pin "12") (pinfunction "DIF2_12") (pintype "input"))
    )
    (net (code "65") (name "Net-(IC2-DVDD)") (class "Default")
      (node (ref "C27A") (pin "1") (pinfunction "1_1") (pintype "passive"))
      (node (ref "C28A") (pin "1") (pinfunction "1_1") (pintype "passive"))
      (node (ref "IC2") (pin "1") (pinfunction "DVDD_1") (pintype "power_in"))
      (node (ref "J8") (pin "7") (pinfunction "7_7") (pintype "passive"))
      (node (ref "LDO7") (pin "5") (pinfunction "VOUT_5") (pintype "bidirectional"))
    )
    (net (code "66") (name "Net-(IC2-LRCK)") (class "Default")
      (node (ref "IC2") (pin "5") (pinfunction "LRCK_5") (pintype "input"))
      (node (ref "J8") (pin "3") (pinfunction "3_3") (pintype "passive"))
      (node (ref "R3A") (pin "2") (pinfunction "2_2") (pintype "passive"))
    )
    (net (code "67") (name "Net-(IC2-MCLK)") (class "Default")
      (node (ref "IC2") (pin "46") (pinfunction "MCLK_46") (pintype "input"))
      (node (ref "J7") (pin "4") (pinfunction "4_4") (pintype "passive"))
      (node (ref "R4A") (pin "2") (pinfunction "2_2") (pintype "passive"))
    )
    (net (code "68") (name "Net-(IC2-SDATA)") (class "Default")
      (node (ref "IC2") (pin "4") (pinfunction "SDATA_4") (pintype "input"))
      (node (ref "J8") (pin "4") (pinfunction "4_4") (pintype "passive"))
      (node (ref "R2A") (pin "2") (pinfunction "2_2") (pintype "passive"))
    )
    (net (code "69") (name "Net-(IC2-SMUTE)") (class "Default")
      (node (ref "IC2") (pin "7") (pinfunction "SMUTE_7") (pintype "input"))
      (node (ref "SMUTE1") (pin "1") (pinfunction "1_1") (pintype "passive"))
    )
    (net (code "70") (name "Net-(IC3-BICK)") (class "Default")
      (node (ref "IC3") (pin "3") (pinfunction "BICK_3") (pintype "input"))
      (node (ref "J12") (pin "5") (pinfunction "5_5") (pintype "passive"))
      (node (ref "R1B") (pin "2") (pinfunction "2_2") (pintype "passive"))
    )
    (net (code "71") (name "Net-(IC3-DIF0)") (class "Default")
      (node (ref "IC3") (pin "10") (pinfunction "DIF0_10") (pintype "input"))
      (node (ref "J9") (pin "7") (pinfunction "7_7") (pintype "passive"))
    )
    (net (code "72") (name "Net-(IC3-DIF1)") (class "Default")
      (node (ref "IC3") (pin "11") (pinfunction "DIF1_11") (pintype "input"))
      (node (ref "J9") (pin "6") (pinfunction "6_6") (pintype "passive"))
    )
    (net (code "73") (name "Net-(IC3-DIF2)") (class "Default")
      (node (ref "DIF3") (pin "2") (pinfunction "2_2") (pintype "passive"))
      (node (ref "IC3") (pin "12") (pinfunction "DIF2_12") (pintype "input"))
    )
    (net (code "74") (name "Net-(IC3-DVDD)") (class "Default")
      (node (ref "C27B") (pin "1") (pinfunction "1_1") (pintype "passive"))
      (node (ref "C28B") (pin "1") (pinfunction "1_1") (pintype "passive"))
      (node (ref "IC3") (pin "1") (pinfunction "DVDD_1") (pintype "power_in"))
      (node (ref "J12") (pin "7") (pinfunction "7_7") (pintype "passive"))
      (node (ref "LDO8") (pin "5") (pinfunction "VOUT_5") (pintype "bidirectional"))
    )
    (net (code "75") (name "Net-(IC3-LRCK)") (class "Default")
      (node (ref "IC3") (pin "5") (pinfunction "LRCK_5") (pintype "input"))
      (node (ref "J12") (pin "3") (pinfunction "3_3") (pintype "passive"))
      (node (ref "R3B") (pin "2") (pinfunction "2_2") (pintype "passive"))
    )
    (net (code "76") (name "Net-(IC3-MCLK)") (class "Default")
      (node (ref "IC3") (pin "46") (pinfunction "MCLK_46") (pintype "input"))
      (node (ref "J11") (pin "4") (pinfunction "4_4") (pintype "passive"))
      (node (ref "R4B") (pin "2") (pinfunction "2_2") (pintype "passive"))
    )
    (net (code "77") (name "Net-(IC3-SDATA)") (class "Default")
      (node (ref "IC3") (pin "4") (pinfunction "SDATA_4") (pintype "input"))
      (node (ref "J12") (pin "4") (pinfunction "4_4") (pintype "passive"))
      (node (ref "R2B") (pin "2") (pinfunction "2_2") (pintype "passive"))
    )
    (net (code "78") (name "Net-(IC3-SMUTE)") (class "Default")
      (node (ref "IC3") (pin "7") (pinfunction "SMUTE_7") (pintype "input"))
      (node (ref "SMUTE2") (pin "1") (pinfunction "1_1") (pintype "passive"))
    )
    (net (code "79") (name "Net-(IC4-ILIM)") (class "Default")
      (node (ref "IC4") (pin "5") (pinfunction "ILIM_5") (pintype "bidirectional"))
      (node (ref "J16") (pin "2") (pinfunction "2_2") (pintype "bidirectional"))
      (node (ref "R6C") (pin "1") (pinfunction "1_1") (pintype "passive"))
    )
    (net (code "80") (name "Net-(IC4-PG)") (class "Default")
      (node (ref "IC4") (pin "4") (pinfunction "PG_4") (pintype "bidirectional"))
      (node (ref "J16") (pin "1") (pinfunction "1_1") (pintype "bidirectional"))
      (node (ref "R8C") (pin "2") (pinfunction "2_2") (pintype "passive"))
    )
    (net (code "81") (name "Net-(IC4-PGFB)") (class "Default")
      (node (ref "IC4") (pin "6") (pinfunction "PGFB_6") (pintype "bidirectional"))
      (node (ref "J16") (pin "3") (pinfunction "3_3") (pintype "bidirectional"))
    )
    (net (code "82") (name "Net-(IC4-SET)") (class "Default")
      (node (ref "C19C") (pin "1") (pinfunction "1_1") (pintype "passive"))
      (node (ref "IC4") (pin "7") (pinfunction "SET_7") (pintype "bidirectional"))
      (node (ref "J16") (pin "4") (pinfunction "4_4") (pintype "bidirectional"))
      (node (ref "R7C") (pin "1") (pinfunction "1_1") (pintype "passive"))
    )
    (net (code "83") (name "Net-(IC4A-1Q)") (class "Default")
      (node (ref "IC4A") (pin "2") (pinfunction "1Q_2") (pintype "bidirectional"))
      (node (ref "J21") (pin "9") (pinfunction "9_9") (pintype "passive"))
      (node (ref "R3B") (pin "1") (pinfunction "1_1") (pintype "passive"))
    )
    (net (code "84") (name "Net-(IC4A-2Q)") (class "Default")
      (node (ref "IC4A") (pin "5") (pinfunction "2Q_5") (pintype "bidirectional"))
      (node (ref "J21") (pin "6") (pinfunction "6_6") (pintype "passive"))
      (node (ref "R2B") (pin "1") (pinfunction "1_1") (pintype "passive"))
    )
    (net (code "85") (name "Net-(IC4A-3Q)") (class "Default")
      (node (ref "IC4A") (pin "6") (pinfunction "3Q_6") (pintype "bidirectional"))
      (node (ref "J21") (pin "5") (pinfunction "5_5") (pintype "passive"))
    )
    (net (code "86") (name "Net-(IC4A-4Q)") (class "Default")
      (node (ref "IC4A") (pin "9") (pinfunction "4Q_9") (pintype "bidirectional"))
      (node (ref "J21") (pin "2") (pinfunction "2_2") (pintype "passive"))
      (node (ref "R1B") (pin "1") (pinfunction "1_1") (pintype "passive"))
    )
    (net (code "87") (name "Net-(IC4A-5Q)") (class "Default")
      (node (ref "IC4A") (pin "12") (pinfunction "5Q_12") (pintype "bidirectional"))
      (node (ref "J22") (pin "9") (pinfunction "9_9") (pintype "passive"))
      (node (ref "R3A") (pin "1") (pinfunction "1_1") (pintype "passive"))
    )
    (net (code "88") (name "Net-(IC4A-6Q)") (class "Default")
      (node (ref "IC4A") (pin "15") (pinfunction "6Q_15") (pintype "bidirectional"))
      (node (ref "J22") (pin "6") (pinfunction "6_6") (pintype "passive"))
      (node (ref "R2A") (pin "1") (pinfunction "1_1") (pintype "passive"))
    )
    (net (code "89") (name "Net-(IC4A-7Q)") (class "Default")
      (node (ref "IC4A") (pin "16") (pinfunction "7Q_16") (pintype "bidirectional"))
      (node (ref "J22") (pin "5") (pinfunction "5_5") (pintype "passive"))
    )
    (net (code "90") (name "Net-(IC4A-8Q)") (class "Default")
      (node (ref "IC4A") (pin "19") (pinfunction "8Q_19") (pintype "bidirectional"))
      (node (ref "J22") (pin "2") (pinfunction "2_2") (pintype "passive"))
      (node (ref "R1A") (pin "1") (pinfunction "1_1") (pintype "passive"))
    )
    (net (code "91") (name "Net-(IC4A-~{CLR})") (class "Default")
      (node (ref "IC4A") (pin "1") (pinfunction "~{CLR}_1") (pintype "bidirectional"))
      (node (ref "J21") (pin "10") (pinfunction "10_10") (pintype "passive"))
      (node (ref "R21A") (pin "1") (pinfunction "1_1") (pintype "passive"))
    )
    (net (code "92") (name "Net-(IC5-ILIM)") (class "Default")
      (node (ref "IC5") (pin "5") (pinfunction "ILIM_5") (pintype "bidirectional"))
      (node (ref "J17") (pin "2") (pinfunction "2_2") (pintype "bidirectional"))
      (node (ref "R6B") (pin "1") (pinfunction "1_1") (pintype "passive"))
    )
    (net (code "93") (name "Net-(IC5-PG)") (class "Default")
      (node (ref "IC5") (pin "4") (pinfunction "PG_4") (pintype "bidirectional"))
      (node (ref "J17") (pin "1") (pinfunction "1_1") (pintype "bidirectional"))
      (node (ref "R8B") (pin "2") (pinfunction "2_2") (pintype "passive"))
    )
    (net (code "94") (name "Net-(IC5-PGFB)") (class "Default")
      (node (ref "IC5") (pin "6") (pinfunction "PGFB_6") (pintype "bidirectional"))
      (node (ref "J17") (pin "3") (pinfunction "3_3") (pintype "bidirectional"))
    )
    (net (code "95") (name "Net-(IC5-SET)") (class "Default")
      (node (ref "C19B") (pin "1") (pinfunction "1_1") (pintype "passive"))
      (node (ref "IC5") (pin "7") (pinfunction "SET_7") (pintype "bidirectional"))
      (node (ref "J17") (pin "4") (pinfunction "4_4") (pintype "bidirectional"))
      (node (ref "R7B") (pin "1") (pinfunction "1_1") (pintype "passive"))
    )
    (net (code "96") (name "Net-(IC6-ILIM)") (class "Default")
      (node (ref "IC6") (pin "5") (pinfunction "ILIM_5") (pintype "bidirectional"))
      (node (ref "J18") (pin "2") (pinfunction "2_2") (pintype "bidirectional"))
      (node (ref "R6D") (pin "1") (pinfunction "1_1") (pintype "passive"))
    )
    (net (code "97") (name "Net-(IC6-PG)") (class "Default")
      (node (ref "IC6") (pin "4") (pinfunction "PG_4") (pintype "bidirectional"))
      (node (ref "J18") (pin "1") (pinfunction "1_1") (pintype "bidirectional"))
      (node (ref "R8D") (pin "2") (pinfunction "2_2") (pintype "passive"))
    )
    (net (code "98") (name "Net-(IC6-PGFB)") (class "Default")
      (node (ref "IC6") (pin "6") (pinfunction "PGFB_6") (pintype "bidirectional"))
      (node (ref "J18") (pin "3") (pinfunction "3_3") (pintype "bidirectional"))
    )
    (net (code "99") (name "Net-(IC6-SET)") (class "Default")
      (node (ref "C19D") (pin "1") (pinfunction "1_1") (pintype "passive"))
      (node (ref "IC6") (pin "7") (pinfunction "SET_7") (pintype "bidirectional"))
      (node (ref "J18") (pin "4") (pinfunction "4_4") (pintype "bidirectional"))
      (node (ref "R7D") (pin "1") (pinfunction "1_1") (pintype "passive"))
    )
    (net (code "100") (name "Net-(IC7-ILIM)") (class "Default")
      (node (ref "IC7") (pin "5") (pinfunction "ILIM_5") (pintype "bidirectional"))
      (node (ref "J19") (pin "2") (pinfunction "2_2") (pintype "bidirectional"))
      (node (ref "R6F") (pin "1") (pinfunction "1_1") (pintype "passive"))
    )
    (net (code "101") (name "Net-(IC7-PG)") (class "Default")
      (node (ref "IC7") (pin "4") (pinfunction "PG_4") (pintype "bidirectional"))
      (node (ref "J19") (pin "1") (pinfunction "1_1") (pintype "bidirectional"))
      (node (ref "R8F") (pin "2") (pinfunction "2_2") (pintype "passive"))
    )
    (net (code "102") (name "Net-(IC7-PGFB)") (class "Default")
      (node (ref "IC7") (pin "6") (pinfunction "PGFB_6") (pintype "bidirectional"))
      (node (ref "J19") (pin "3") (pinfunction "3_3") (pintype "bidirectional"))
    )
    (net (code "103") (name "Net-(IC7-SET)") (class "Default")
      (node (ref "C19F") (pin "1") (pinfunction "1_1") (pintype "passive"))
      (node (ref "IC7") (pin "7") (pinfunction "SET_7") (pintype "bidirectional"))
      (node (ref "J19") (pin "4") (pinfunction "4_4") (pintype "bidirectional"))
      (node (ref "R7F") (pin "1") (pinfunction "1_1") (pintype "passive"))
    )
    (net (code "104") (name "Net-(IC8-ILIM)") (class "Default")
      (node (ref "IC8") (pin "5") (pinfunction "ILIM_5") (pintype "bidirectional"))
      (node (ref "J20") (pin "2") (pinfunction "2_2") (pintype "bidirectional"))
      (node (ref "R6E") (pin "1") (pinfunction "1_1") (pintype "passive"))
    )
    (net (code "105") (name "Net-(IC8-PG)") (class "Default")
      (node (ref "IC8") (pin "4") (pinfunction "PG_4") (pintype "bidirectional"))
      (node (ref "J20") (pin "1") (pinfunction "1_1") (pintype "bidirectional"))
      (node (ref "R8E") (pin "2") (pinfunction "2_2") (pintype "passive"))
    )
    (net (code "106") (name "Net-(IC8-PGFB)") (class "Default")
      (node (ref "IC8") (pin "6") (pinfunction "PGFB_6") (pintype "bidirectional"))
      (node (ref "J20") (pin "3") (pinfunction "3_3") (pintype "bidirectional"))
    )
    (net (code "107") (name "Net-(IC8-SET)") (class "Default")
      (node (ref "C19E") (pin "1") (pinfunction "1_1") (pintype "passive"))
      (node (ref "IC8") (pin "7") (pinfunction "SET_7") (pintype "bidirectional"))
      (node (ref "J20") (pin "4") (pinfunction "4_4") (pintype "bidirectional"))
      (node (ref "R7E") (pin "1") (pinfunction "1_1") (pintype "passive"))
    )
    (net (code "108") (name "Net-(R1O-Pad2)") (class "Default")
      (node (ref "R1O") (pin "2") (pinfunction "2_2") (pintype "passive"))
      (node (ref "R2O") (pin "2") (pinfunction "2_2") (pintype "passive"))
      (node (ref "SX2") (pin "7") (pinfunction "7_7") (pintype "passive"))
    )
    (net (code "109") (name "Net-(R13O-Pad2)") (class "Default")
      (node (ref "R13O") (pin "2") (pinfunction "2_2") (pintype "passive"))
      (node (ref "R15O") (pin "2") (pinfunction "2_2") (pintype "passive"))
      (node (ref "SX1") (pin "7") (pinfunction "7_7") (pintype "passive"))
    )
    (net (code "110") (name "Net-(U1-OUTPUT)") (class "Default")
      (node (ref "D9") (pin "C") (pinfunction "C_C") (pintype "passive"))
      (node (ref "U$1") (pin "VIN") (pinfunction "VIN_VIN") (pintype "bidirectional"))
      (node (ref "U1") (pin "2") (pinfunction "OUTPUT_2") (pintype "bidirectional"))
      (node (ref "U1") (pin "4") (pinfunction "VOUT_4") (pintype "bidirectional"))
      (node (ref "X4") (pin "3") (pinfunction "S_3") (pintype "passive"))
    )
    (net (code "111") (name "PDN") (class "Default")
      (node (ref "C1A") (pin "1") (pinfunction "1_1") (pintype "passive"))
      (node (ref "IC2") (pin "2") (pinfunction "PDN_2") (pintype "input"))
      (node (ref "IC3") (pin "2") (pinfunction "PDN_2") (pintype "input"))
      (node (ref "J12") (pin "6") (pinfunction "6_6") (pintype "passive"))
      (node (ref "J8") (pin "6") (pinfunction "6_6") (pintype "passive"))
      (node (ref "R5A") (pin "1") (pinfunction "1_1") (pintype "passive"))
      (node (ref "U$1") (pin "0-RX1") (pinfunction "0-RX1/CRX2_0-RX1") (pintype "bidirectional"))
    )
    (net (code "112") (name "PE") (class "Default")
      (node (ref "IN") (pin "7") (pinfunction "7_7") (pintype "bidirectional"))
    )
    (net (code "113") (name "R+") (class "Default")
      (node (ref "R12O") (pin "1") (pinfunction "1_1") (pintype "passive"))
      (node (ref "R13O") (pin "1") (pinfunction "1_1") (pintype "passive"))
      (node (ref "R18O") (pin "1") (pinfunction "1_1") (pintype "passive"))
    )
    (net (code "114") (name "R-") (class "Default")
      (node (ref "R14O") (pin "1") (pinfunction "1_1") (pintype "passive"))
      (node (ref "R16O") (pin "1") (pinfunction "1_1") (pintype "passive"))
      (node (ref "R27O") (pin "1") (pinfunction "1_1") (pintype "passive"))
    )
    (net (code "115") (name "ROT_A") (class "Default")
      (node (ref "C6") (pin "1") (pinfunction "1_1") (pintype "passive"))
      (node (ref "U$1") (pin "3-LRCLK2") (pinfunction "3-LRCLK2_3-LRCLK2") (pintype "bidirectional"))
      (node (ref "X1") (pin "1") (pinfunction "S_1") (pintype "passive"))
    )
    (net (code "116") (name "ROT_B") (class "Default")
      (node (ref "C7") (pin "2") (pinfunction "2_2") (pintype "passive"))
      (node (ref "U$1") (pin "5-IN2") (pinfunction "5-IN2_5-IN2") (pintype "bidirectional"))
      (node (ref "X1") (pin "3") (pinfunction "S_3") (pintype "passive"))
    )
    (net (code "117") (name "ROT_LEDB") (class "Default")
      (node (ref "U$1") (pin "23-A9/CRX1/CCLK1") (pinfunction "23-A9/CRX1/MCLK1_23-A9/CRX1/CCLK1") (pintype "bidirectional"))
      (node (ref "X1") (pin "4") (pinfunction "S_4") (pintype "passive"))
    )
    (net (code "118") (name "ROT_LEDG") (class "Default")
      (node (ref "U$1") (pin "22-A8/CTX1") (pinfunction "22-A8/CTX1_22-A8/CTX1") (pintype "bidirectional"))
      (node (ref "X1") (pin "5") (pinfunction "S_5") (pintype "passive"))
    )
    (net (code "119") (name "ROT_LEDR") (class "Default")
      (node (ref "U$1") (pin "19-A5/SCL0") (pinfunction "19-A5/SCL0_19-A5/SCL0") (pintype "bidirectional"))
      (node (ref "X1") (pin "6") (pinfunction "S_6") (pintype "passive"))
    )
    (net (code "120") (name "ROT_SW") (class "Default")
      (node (ref "R1") (pin "2") (pinfunction "2_2") (pintype "passive"))
      (node (ref "U$1") (pin "4-BCLK2") (pinfunction "4-BCLK1_4-BCLK2") (pintype "bidirectional"))
      (node (ref "X1") (pin "2") (pinfunction "S_2") (pintype "passive"))
    )
    (net (code "121") (name "R_OUT") (class "Default")
      (node (ref "C21O") (pin "1") (pinfunction "1_1") (pintype "passive"))
      (node (ref "C23O") (pin "1") (pinfunction "1_1") (pintype "passive"))
      (node (ref "J26") (pin "3") (pinfunction "RING_3") (pintype "bidirectional"))
      (node (ref "R17O") (pin "1") (pinfunction "1_1") (pintype "passive"))
      (node (ref "R3O") (pin "1") (pinfunction "1_1") (pintype "passive"))
    )
    (net (code "122") (name "SCL0") (class "Default")
      (node (ref "IC2") (pin "8") (pinfunction "SD_8") (pintype "input"))
      (node (ref "IC3") (pin "8") (pinfunction "SD_8") (pintype "input"))
      (node (ref "J12") (pin "2") (pinfunction "2_2") (pintype "passive"))
      (node (ref "J8") (pin "2") (pinfunction "2_2") (pintype "passive"))
      (node (ref "R10") (pin "2") (pinfunction "2_2") (pintype "passive"))
      (node (ref "U$1") (pin "16-A2/RX4/SCL1") (pinfunction "16-A2/RX4/SCL1_16-A2/RX4/SCL1") (pintype "bidirectional"))
      (node (ref "X4") (pin "1") (pinfunction "S_1") (pintype "passive"))
    )
    (net (code "123") (name "SDA0") (class "Default")
      (node (ref "IC2") (pin "9") (pinfunction "SLOW_9") (pintype "input"))
      (node (ref "IC3") (pin "9") (pinfunction "SLOW_9") (pintype "input"))
      (node (ref "J12") (pin "1") (pinfunction "1_1") (pintype "passive"))
      (node (ref "J8") (pin "1") (pinfunction "1_1") (pintype "passive"))
      (node (ref "R20") (pin "2") (pinfunction "2_2") (pintype "passive"))
      (node (ref "U$1") (pin "17-A3/TX4/SDA1") (pinfunction "17-A3/TX4/SDA1_17-A3/TX4/SDA1") (pintype "bidirectional"))
      (node (ref "X4") (pin "2") (pinfunction "S_2") (pintype "passive"))
    )
    (net (code "124") (name "VCC") (class "Default")
      (node (ref "R4P") (pin "2") (pinfunction "2_2") (pintype "passive"))
    )
    (net (code "125") (name "VCC{slash}1") (class "Default")
      (node (ref "C1P1") (pin "1") (pinfunction "+_1") (pintype "bidirectional"))
      (node (ref "C2") (pin "1") (pinfunction "1_1") (pintype "passive"))
      (node (ref "C20A") (pin "1") (pinfunction "1_1") (pintype "passive"))
      (node (ref "C20B") (pin "1") (pinfunction "1_1") (pintype "passive"))
      (node (ref "C20C") (pin "1") (pinfunction "1_1") (pintype "passive"))
      (node (ref "C20D") (pin "1") (pinfunction "1_1") (pintype "passive"))
      (node (ref "C20E") (pin "1") (pinfunction "1_1") (pintype "passive"))
      (node (ref "C20F") (pin "1") (pinfunction "1_1") (pintype "passive"))
      (node (ref "C21A") (pin "1") (pinfunction "1_1") (pintype "passive"))
      (node (ref "C21B") (pin "1") (pinfunction "1_1") (pintype "passive"))
      (node (ref "C21C") (pin "1") (pinfunction "1_1") (pintype "passive"))
      (node (ref "C21D") (pin "1") (pinfunction "1_1") (pintype "passive"))
      (node (ref "C21E") (pin "1") (pinfunction "1_1") (pintype "passive"))
      (node (ref "C21F") (pin "1") (pinfunction "1_1") (pintype "passive"))
      (node (ref "C2P1") (pin "1") (pinfunction "+_1") (pintype "bidirectional"))
      (node (ref "C3P1") (pin "1") (pinfunction "+_1") (pintype "bidirectional"))
      (node (ref "C4") (pin "1") (pinfunction "1_1") (pintype "passive"))
      (node (ref "C5P1") (pin "1") (pinfunction "+_1") (pintype "bidirectional"))
      (node (ref "C6P1") (pin "1") (pinfunction "+_1") (pintype "bidirectional"))
      (node (ref "C7P1") (pin "1") (pinfunction "+_1") (pintype "bidirectional"))
      (node (ref "D7") (pin "1") (pinfunction "K_1") (pintype "bidirectional"))
      (node (ref "D8") (pin "1") (pinfunction "K_1") (pintype "bidirectional"))
      (node (ref "IC1") (pin "1") (pinfunction "IN_1") (pintype "bidirectional"))
      (node (ref "IC1") (pin "2") (pinfunction "IN_2") (pintype "bidirectional"))
      (node (ref "IC1") (pin "3") (pinfunction "EN/UV_3") (pintype "bidirectional"))
      (node (ref "IC4") (pin "1") (pinfunction "IN_1") (pintype "bidirectional"))
      (node (ref "IC4") (pin "2") (pinfunction "IN_2") (pintype "bidirectional"))
      (node (ref "IC4") (pin "3") (pinfunction "EN/UV_3") (pintype "bidirectional"))
      (node (ref "IC5") (pin "1") (pinfunction "IN_1") (pintype "bidirectional"))
      (node (ref "IC5") (pin "2") (pinfunction "IN_2") (pintype "bidirectional"))
      (node (ref "IC5") (pin "3") (pinfunction "EN/UV_3") (pintype "bidirectional"))
      (node (ref "IC6") (pin "1") (pinfunction "IN_1") (pintype "bidirectional"))
      (node (ref "IC6") (pin "2") (pinfunction "IN_2") (pintype "bidirectional"))
      (node (ref "IC6") (pin "3") (pinfunction "EN/UV_3") (pintype "bidirectional"))
      (node (ref "IC7") (pin "1") (pinfunction "IN_1") (pintype "bidirectional"))
      (node (ref "IC7") (pin "2") (pinfunction "IN_2") (pintype "bidirectional"))
      (node (ref "IC7") (pin "3") (pinfunction "EN/UV_3") (pintype "bidirectional"))
      (node (ref "IC8") (pin "1") (pinfunction "IN_1") (pintype "bidirectional"))
      (node (ref "IC8") (pin "2") (pinfunction "IN_2") (pintype "bidirectional"))
      (node (ref "IC8") (pin "3") (pinfunction "EN/UV_3") (pintype "bidirectional"))
      (node (ref "J15") (pin "7") (pinfunction "7_7") (pintype "bidirectional"))
      (node (ref "J15") (pin "8") (pinfunction "8_8") (pintype "bidirectional"))
      (node (ref "J16") (pin "7") (pinfunction "7_7") (pintype "bidirectional"))
      (node (ref "J16") (pin "8") (pinfunction "8_8") (pintype "bidirectional"))
      (node (ref "J17") (pin "7") (pinfunction "7_7") (pintype "bidirectional"))
      (node (ref "J17") (pin "8") (pinfunction "8_8") (pintype "bidirectional"))
      (node (ref "J18") (pin "7") (pinfunction "7_7") (pintype "bidirectional"))
      (node (ref "J18") (pin "8") (pinfunction "8_8") (pintype "bidirectional"))
      (node (ref "J19") (pin "7") (pinfunction "7_7") (pintype "bidirectional"))
      (node (ref "J19") (pin "8") (pinfunction "8_8") (pintype "bidirectional"))
      (node (ref "J20") (pin "7") (pinfunction "7_7") (pintype "bidirectional"))
      (node (ref "J20") (pin "8") (pinfunction "8_8") (pintype "bidirectional"))
      (node (ref "R8A") (pin "1") (pinfunction "1_1") (pintype "passive"))
      (node (ref "R8B") (pin "1") (pinfunction "1_1") (pintype "passive"))
      (node (ref "R8C") (pin "1") (pinfunction "1_1") (pintype "passive"))
      (node (ref "R8D") (pin "1") (pinfunction "1_1") (pintype "passive"))
      (node (ref "R8E") (pin "1") (pinfunction "1_1") (pintype "passive"))
      (node (ref "R8F") (pin "1") (pinfunction "1_1") (pintype "passive"))
      (node (ref "U1") (pin "3") (pinfunction "INPUT_3") (pintype "bidirectional"))
    )
    (net (code "126") (name "unconnected-(BD1-PadH3.9)") (class "Default")
      (node (ref "BD1") (pin "H3.9") (pinfunction "H3.9_H3.9") (pintype "passive"))
    )
    (net (code "127") (name "unconnected-(BD1-PadH3.18)") (class "Default")
      (node (ref "BD1") (pin "H3.18") (pinfunction "H3.18_H3.18") (pintype "passive"))
    )
    (net (code "128") (name "unconnected-(BD1-PadH3.20)") (class "Default")
      (node (ref "BD1") (pin "H3.20") (pinfunction "H3.20_H3.20") (pintype "passive"))
    )
    (net (code "129") (name "unconnected-(IC2-NC-Pad24)") (class "Default")
      (node (ref "IC2") (pin "24") (pinfunction "NC_24") (pintype "no_connect"))
    )
    (net (code "130") (name "unconnected-(IC2-NC1-Pad37)") (class "Default")
      (node (ref "IC2") (pin "37") (pinfunction "NC1_37") (pintype "no_connect"))
    )
    (net (code "131") (name "unconnected-(IC2-NC2-Pad43)") (class "Default")
      (node (ref "IC2") (pin "43") (pinfunction "NC2_43") (pintype "no_connect"))
    )
    (net (code "132") (name "unconnected-(IC2-TESTE-Pad18)") (class "Default")
      (node (ref "IC2") (pin "18") (pinfunction "TESTE_18") (pintype "input"))
    )
    (net (code "133") (name "unconnected-(IC3-NC-Pad24)") (class "Default")
      (node (ref "IC3") (pin "24") (pinfunction "NC_24") (pintype "no_connect"))
    )
    (net (code "134") (name "unconnected-(IC3-NC1-Pad37)") (class "Default")
      (node (ref "IC3") (pin "37") (pinfunction "NC1_37") (pintype "no_connect"))
    )
    (net (code "135") (name "unconnected-(IC3-NC2-Pad43)") (class "Default")
      (node (ref "IC3") (pin "43") (pinfunction "NC2_43") (pintype "no_connect"))
    )
    (net (code "136") (name "unconnected-(IC3-TESTE-Pad18)") (class "Default")
      (node (ref "IC3") (pin "18") (pinfunction "TESTE_18") (pintype "input"))
    )
    (net (code "137") (name "unconnected-(J7-Pad1)") (class "Default")
      (node (ref "J7") (pin "1") (pinfunction "1_1") (pintype "passive"))
    )
    (net (code "138") (name "unconnected-(J11-Pad1)") (class "Default")
      (node (ref "J11") (pin "1") (pinfunction "1_1") (pintype "passive"))
    )
    (net (code "139") (name "unconnected-(LDO7-NC-Pad4)") (class "Default")
      (node (ref "LDO7") (pin "4") (pinfunction "NC_4") (pintype "no_connect"))
    )
    (net (code "140") (name "unconnected-(LDO8-NC-Pad4)") (class "Default")
      (node (ref "LDO8") (pin "4") (pinfunction "NC_4") (pintype "no_connect"))
    )
    (net (code "141") (name "unconnected-(U$1-7-OUT1A{slash}RX2-Pad7-RX2{slash}OUT1A)") (class "Default")
      (node (ref "U$1") (pin "7-RX2/OUT1A") (pinfunction "7-OUT1A/RX2_7-RX2/OUT1A") (pintype "bidirectional"))
    )
    (net (code "142") (name "unconnected-(U$1-8-IN1{slash}TX2-Pad8-TX2{slash}IN1)") (class "Default")
      (node (ref "U$1") (pin "8-TX2/IN1") (pinfunction "8-IN1/TX2_8-TX2/IN1") (pintype "bidirectional"))
    )
    (net (code "143") (name "unconnected-(U$1-10-CS-Pad10-CS{slash}MQSR)") (class "Default")
      (node (ref "U$1") (pin "10-CS/MQSR") (pinfunction "10-CS_10-CS/MQSR") (pintype "bidirectional"))
    )
    (net (code "144") (name "unconnected-(U$1-12-MISO{slash}MQSL-Pad12-MIO{slash}MQSL)") (class "Default")
      (node (ref "U$1") (pin "12-MIO/MQSL") (pinfunction "12-MISO/MQSL_12-MIO/MQSL") (pintype "bidirectional"))
    )
    (net (code "145") (name "unconnected-(U$1-14-A0{slash}TX3{slash}S-PDIF_IN-Pad14-A0{slash}TX3{slash}S-PFI_OUT)") (class "Default")
      (node (ref "U$1") (pin "14-A0/TX3/S-PFI_OUT") (pinfunction "14-A0/TX3/S-PDIF_IN_14-A0/TX3/S-PFI_OUT") (pintype "bidirectional"))
    )
    (net (code "146") (name "unconnected-(U$1-15-A1{slash}RX3{slash}SPDIF_IN-Pad15-A1{slash}RX3{slash}S-PDIF_IN)") (class "Default")
      (node (ref "U$1") (pin "15-A1/RX3/S-PDIF_IN") (pinfunction "15-A1/RX3/SPDIF_IN_15-A1/RX3/S-PDIF_IN") (pintype "bidirectional"))
    )
    (net (code "147") (name "unconnected-(U$1-25-A11{slash}RX6{slash}SDA2-Pad25-A11{slash}SDA2)") (class "Default")
      (node (ref "U$1") (pin "25-A11/SDA2") (pinfunction "25-A11/RX6/SDA2_25-A11/SDA2") (pintype "bidirectional"))
    )
    (net (code "148") (name "unconnected-(U$1-32-OUT1B-Pad32-OUTB1)") (class "Default")
      (node (ref "U$1") (pin "32-OUTB1") (pinfunction "32-OUT1B_32-OUTB1") (pintype "bidirectional"))
    )
    (net (code "149") (name "unconnected-(U$1-Pad3V3-1)") (class "Default")
      (node (ref "U$1") (pin "3V3-1") (pinfunction "3V3-1_3V3-1") (pintype "bidirectional"))
    )
    (net (code "150") (name "unconnected-(U$1-Pad3V3-2)") (class "Default")
      (node (ref "U$1") (pin "3V3-2") (pinfunction "3V3-2_3V3-2") (pintype "bidirectional"))
    )
    (net (code "151") (name "unconnected-(U$1-Pad6-OUT1D)") (class "Default")
      (node (ref "U$1") (pin "6-OUT1D") (pinfunction "6-OUT1D_6-OUT1D") (pintype "bidirectional"))
    )
    (net (code "152") (name "unconnected-(U$1-Pad9-OUT1C)") (class "Default")
      (node (ref "U$1") (pin "9-OUT1C") (pinfunction "9-OUT1C_9-OUT1C") (pintype "bidirectional"))
    )
    (net (code "153") (name "unconnected-(U$1-Pad11-MOSI{slash}CTX1)") (class "Default")
      (node (ref "U$1") (pin "11-MOSI/CTX1") (pinfunction "11-MOSI/CTX1_11-MOSI/CTX1") (pintype "bidirectional"))
    )
    (net (code "154") (name "unconnected-(U$1-Pad13-SCK{slash}CRX1{slash}LED)") (class "Default")
      (node (ref "U$1") (pin "13-SCK/CRX1/LED") (pinfunction "13-SCK/CRX1/LED_13-SCK/CRX1/LED") (pintype "bidirectional"))
    )
    (net (code "155") (name "unconnected-(U$1-Pad18-A4{slash}SDA0)") (class "Default")
      (node (ref "U$1") (pin "18-A4/SDA0") (pinfunction "18-A4/SDA0_18-A4/SDA0") (pintype "bidirectional"))
    )
    (net (code "156") (name "unconnected-(U$1-Pad20-A6{slash}TX5{slash}LRCLK1)") (class "Default")
      (node (ref "U$1") (pin "20-A6/TX5/LRCLK1") (pinfunction "20-A6/TX5/LRCLK1_20-A6/TX5/LRCLK1") (pintype "bidirectional"))
    )
    (net (code "157") (name "unconnected-(U$1-Pad21-A7{slash}RX5{slash}BCLK1)") (class "Default")
      (node (ref "U$1") (pin "21-A7/RX5/BCLK1") (pinfunction "21-A7/RX5/BCLK1_21-A7/RX5/BCLK1") (pintype "bidirectional"))
    )
    (net (code "158") (name "unconnected-(U$1-Pad24-A10{slash}TX6{slash}SCL2)") (class "Default")
      (node (ref "U$1") (pin "24-A10/TX6/SCL2") (pinfunction "24-A10/TX6/SCL2_24-A10/TX6/SCL2") (pintype "bidirectional"))
    )
    (net (code "159") (name "unconnected-(U$1-Pad26-A12{slash}MOSI1)") (class "Default")
      (node (ref "U$1") (pin "26-A12/MOSI1") (pinfunction "26-A12/MOSI1_26-A12/MOSI1") (pintype "bidirectional"))
    )
    (net (code "160") (name "unconnected-(U$1-Pad27-A13{slash}SCK1)") (class "Default")
      (node (ref "U$1") (pin "27-A13/SCK1") (pinfunction "27-A13/SCK1_27-A13/SCK1") (pintype "bidirectional"))
    )
    (net (code "161") (name "unconnected-(U$1-Pad28-RX7)") (class "Default")
      (node (ref "U$1") (pin "28-RX7") (pinfunction "28-RX7_28-RX7") (pintype "bidirectional"))
    )
    (net (code "162") (name "unconnected-(U$1-Pad29-TX7)") (class "Default")
      (node (ref "U$1") (pin "29-TX7") (pinfunction "29-TX7_29-TX7") (pintype "bidirectional"))
    )
    (net (code "163") (name "unconnected-(U$1-Pad30-CRX3)") (class "Default")
      (node (ref "U$1") (pin "30-CRX3") (pinfunction "30-CRX3_30-CRX3") (pintype "bidirectional"))
    )
    (net (code "164") (name "unconnected-(U$1-Pad31-CTX3)") (class "Default")
      (node (ref "U$1") (pin "31-CTX3") (pinfunction "31-CTX3_31-CTX3") (pintype "bidirectional"))
    )
    (net (code "165") (name "unconnected-(U$1-Pad33-MCLK2)") (class "Default")
      (node (ref "U$1") (pin "33-MCLK2") (pinfunction "33-MCLK2_33-MCLK2") (pintype "bidirectional"))
    )
    (net (code "166") (name "unconnected-(U$1-PadON{slash}OFF)") (class "Default")
      (node (ref "U$1") (pin "ON/OFF") (pinfunction "ON/OFF_ON/OFF") (pintype "bidirectional"))
    )
    (net (code "167") (name "unconnected-(U$1-PadPROGRAM)") (class "Default")
      (node (ref "U$1") (pin "PROGRAM") (pinfunction "PROGRAM_PROGRAM") (pintype "bidirectional"))
    )
    (net (code "168") (name "unconnected-(U$1-PadVBAT)") (class "Default")
      (node (ref "U$1") (pin "VBAT") (pinfunction "VBAT_VBAT") (pintype "bidirectional"))
    )
  )
)
